# alf_board_v8.net
KiCad netlist of a schematic drawn in EAGLE
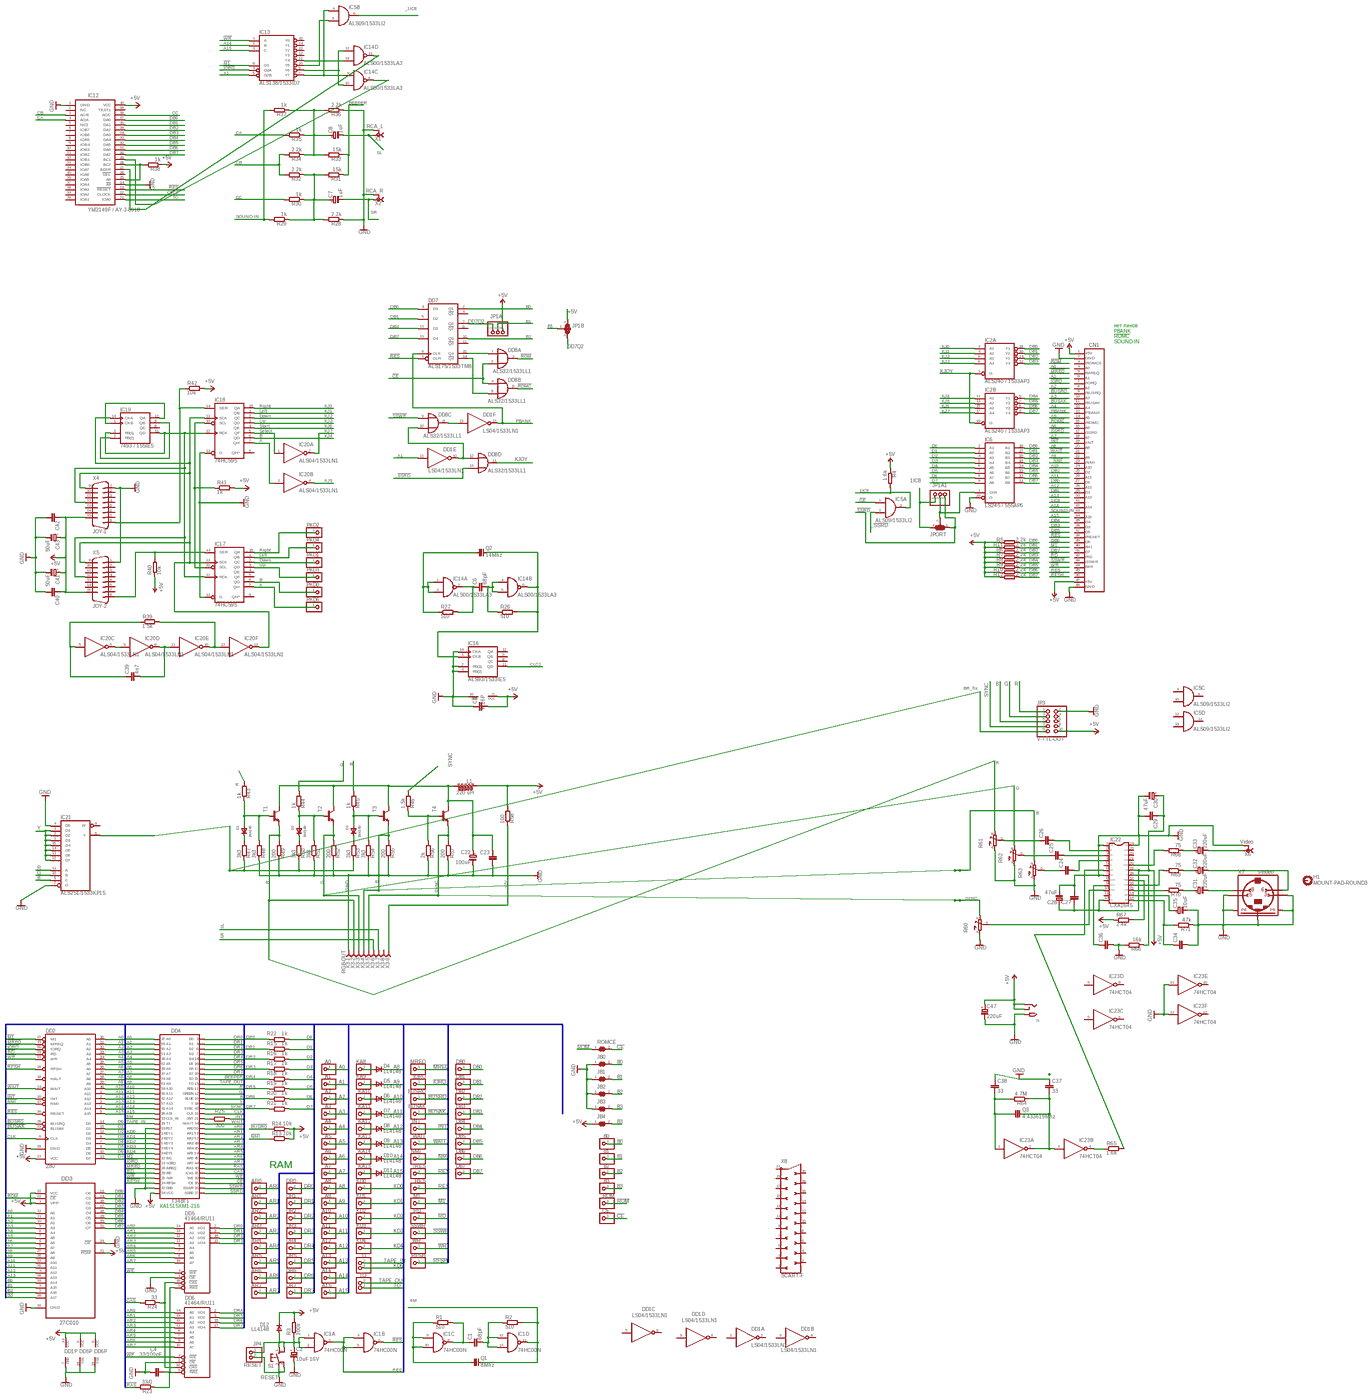
[diagram p0: schematic, sheet 1, overview]
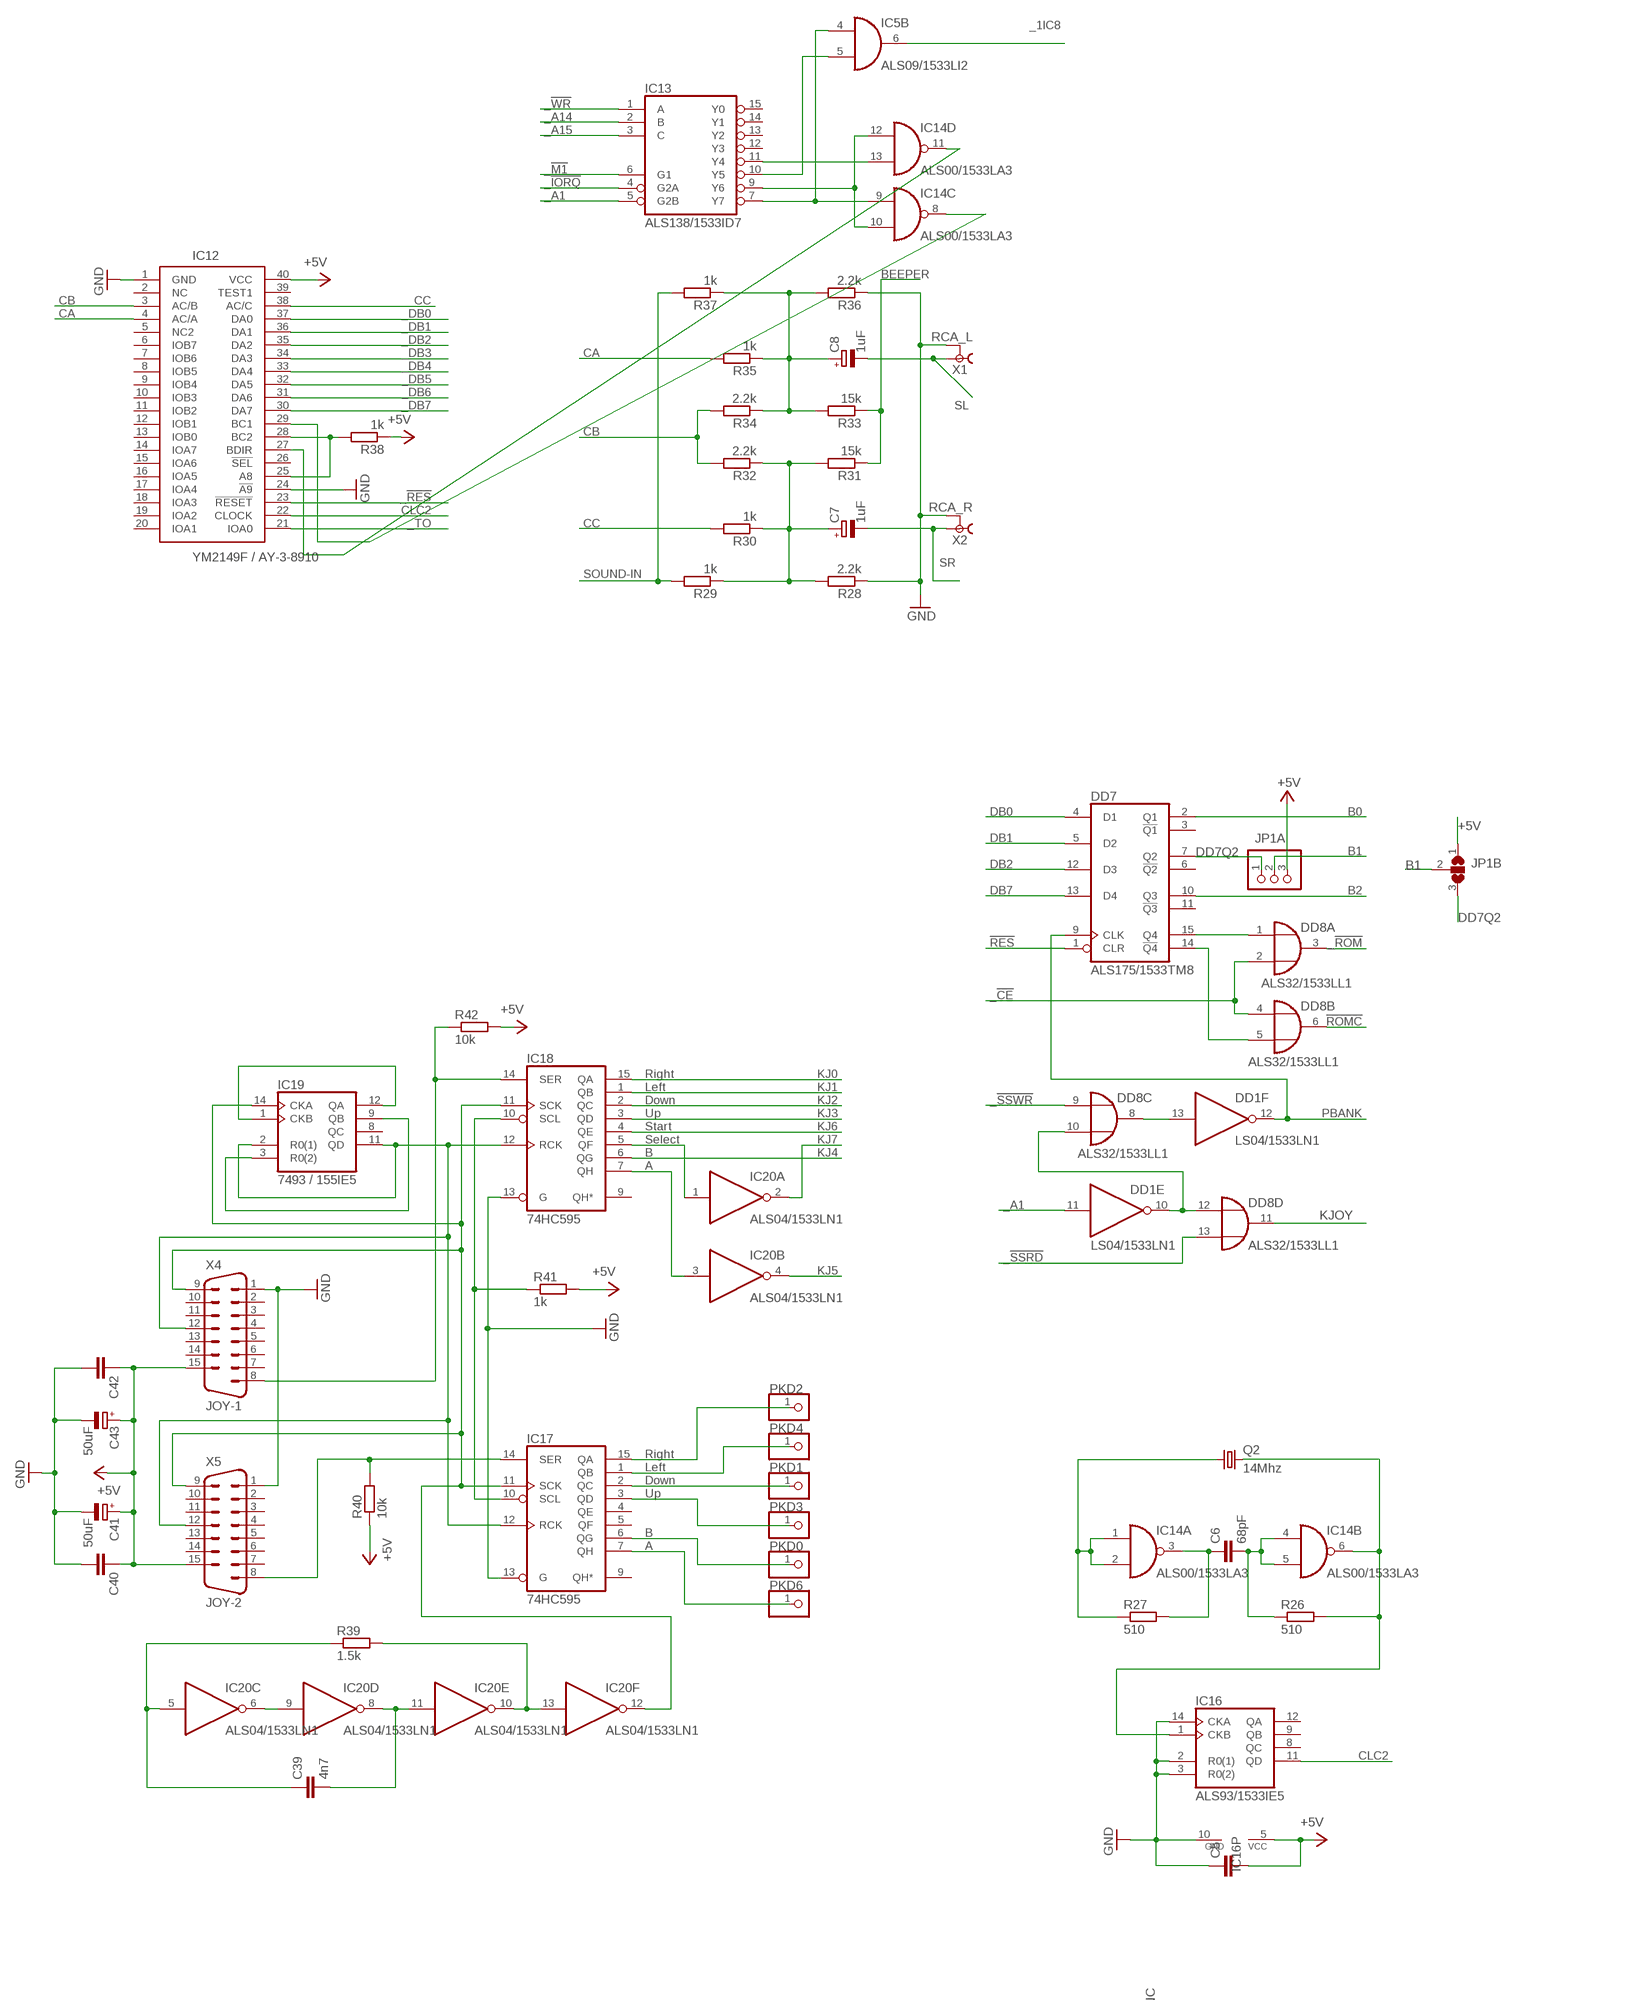
[diagram p1: schematic, sheet 1, part 1 of 4]
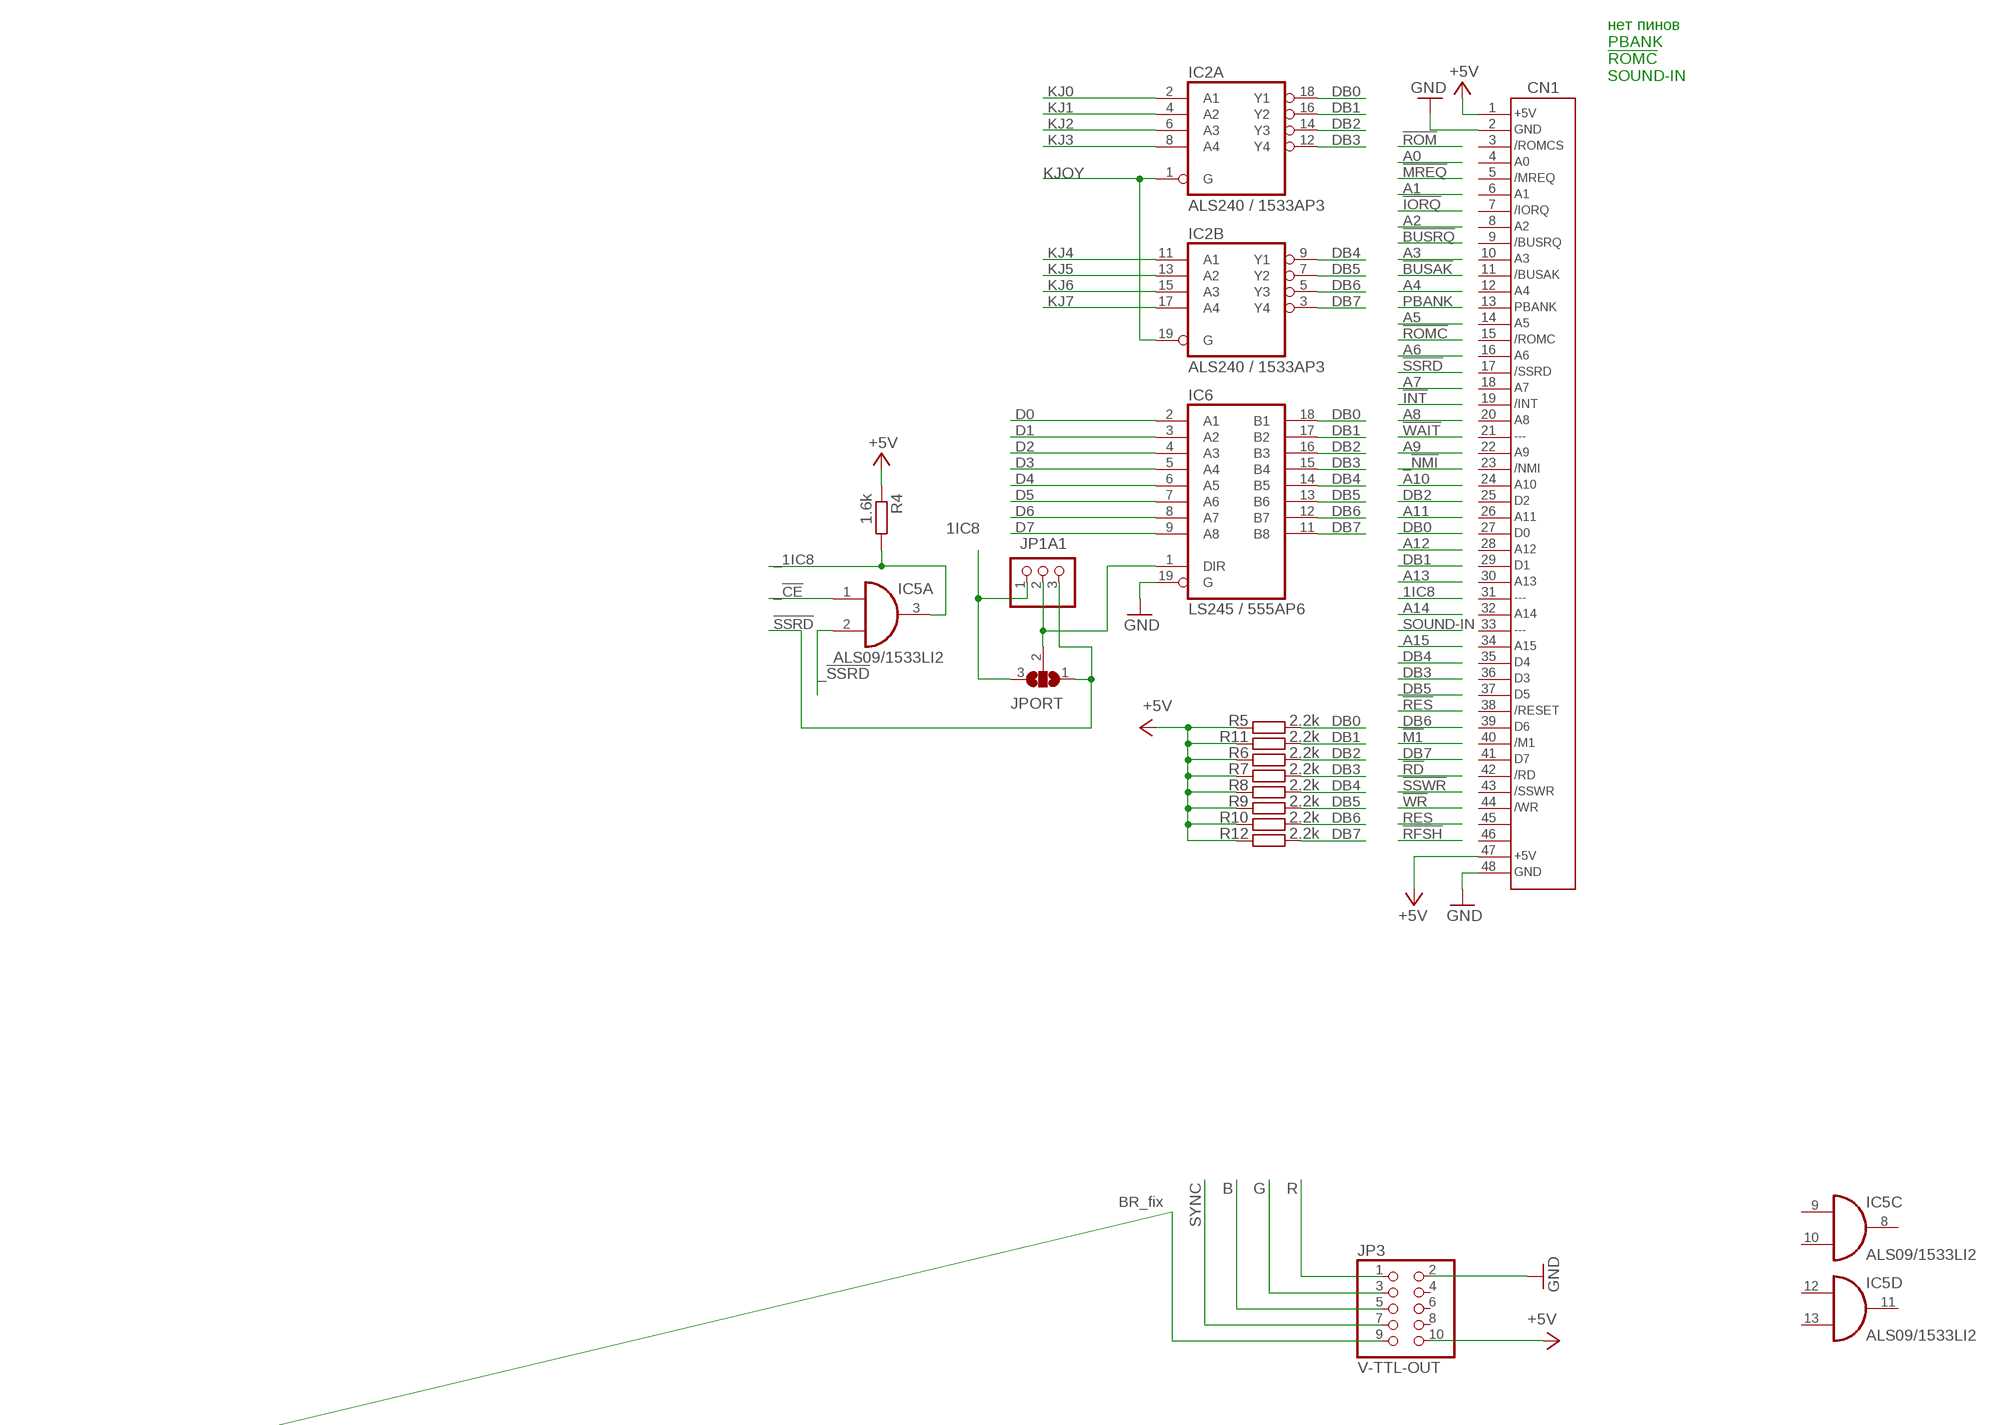
[diagram p2: schematic, sheet 1, part 2 of 4]
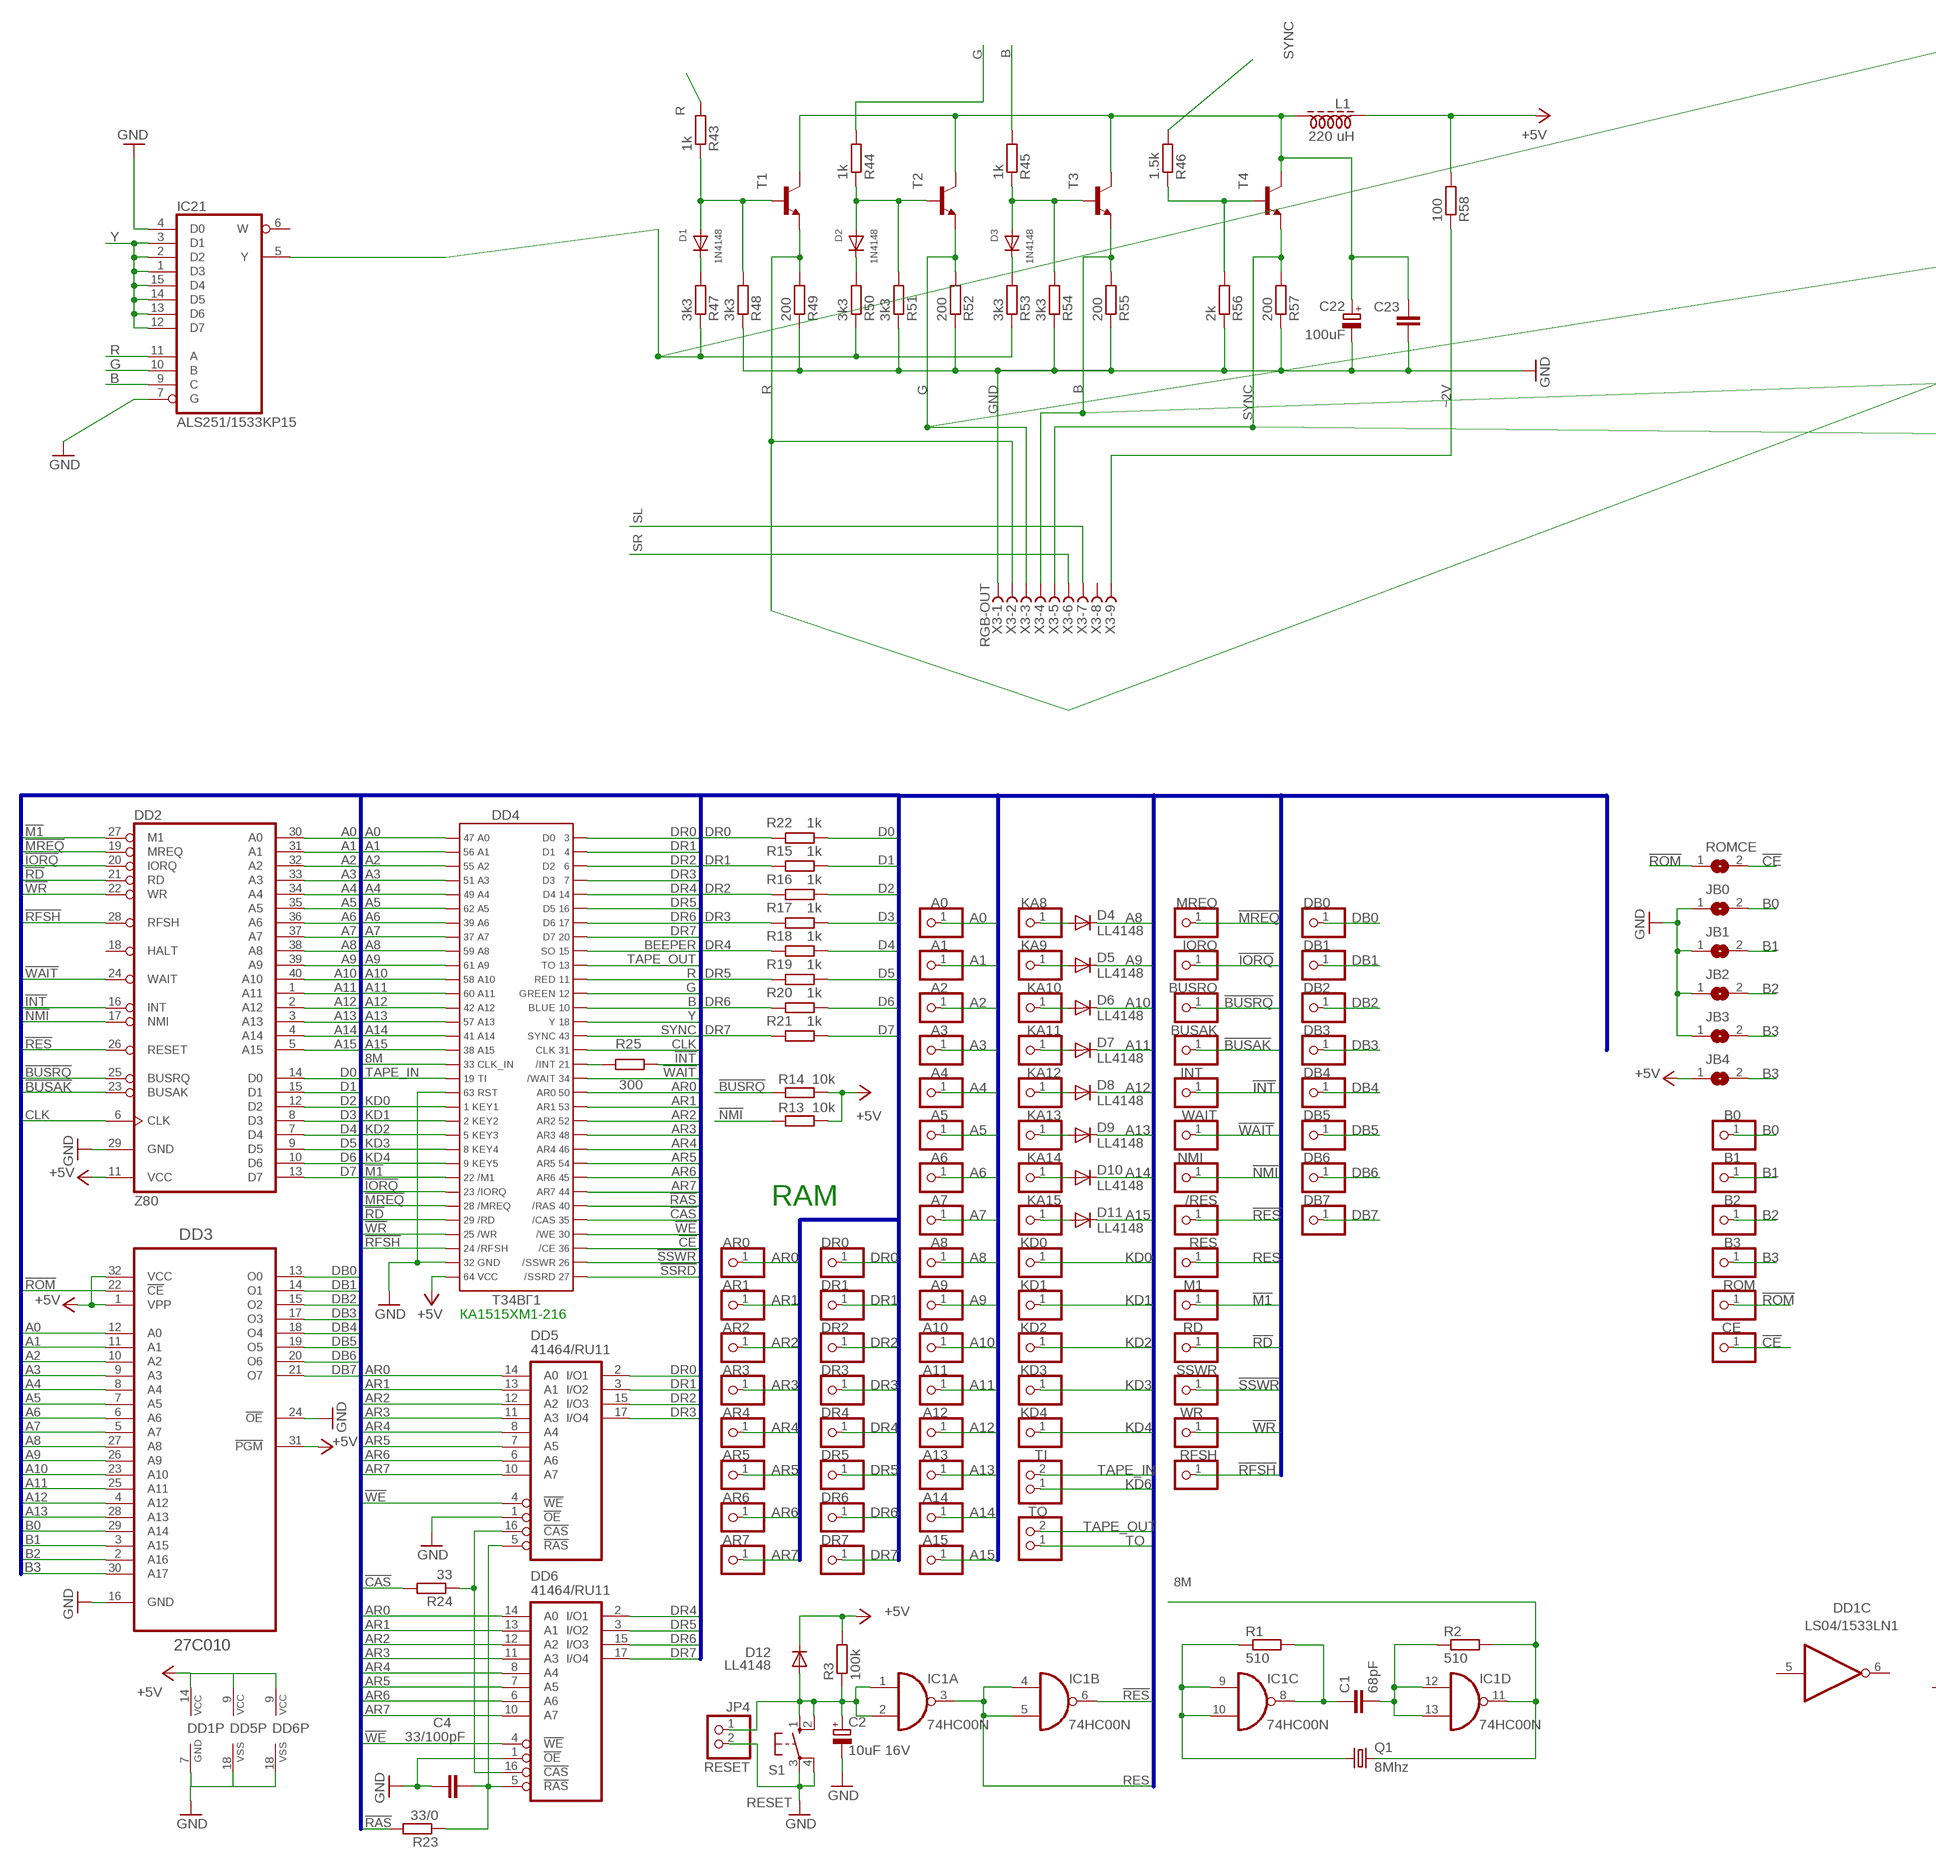
[diagram p3: schematic, sheet 1, part 3 of 4]
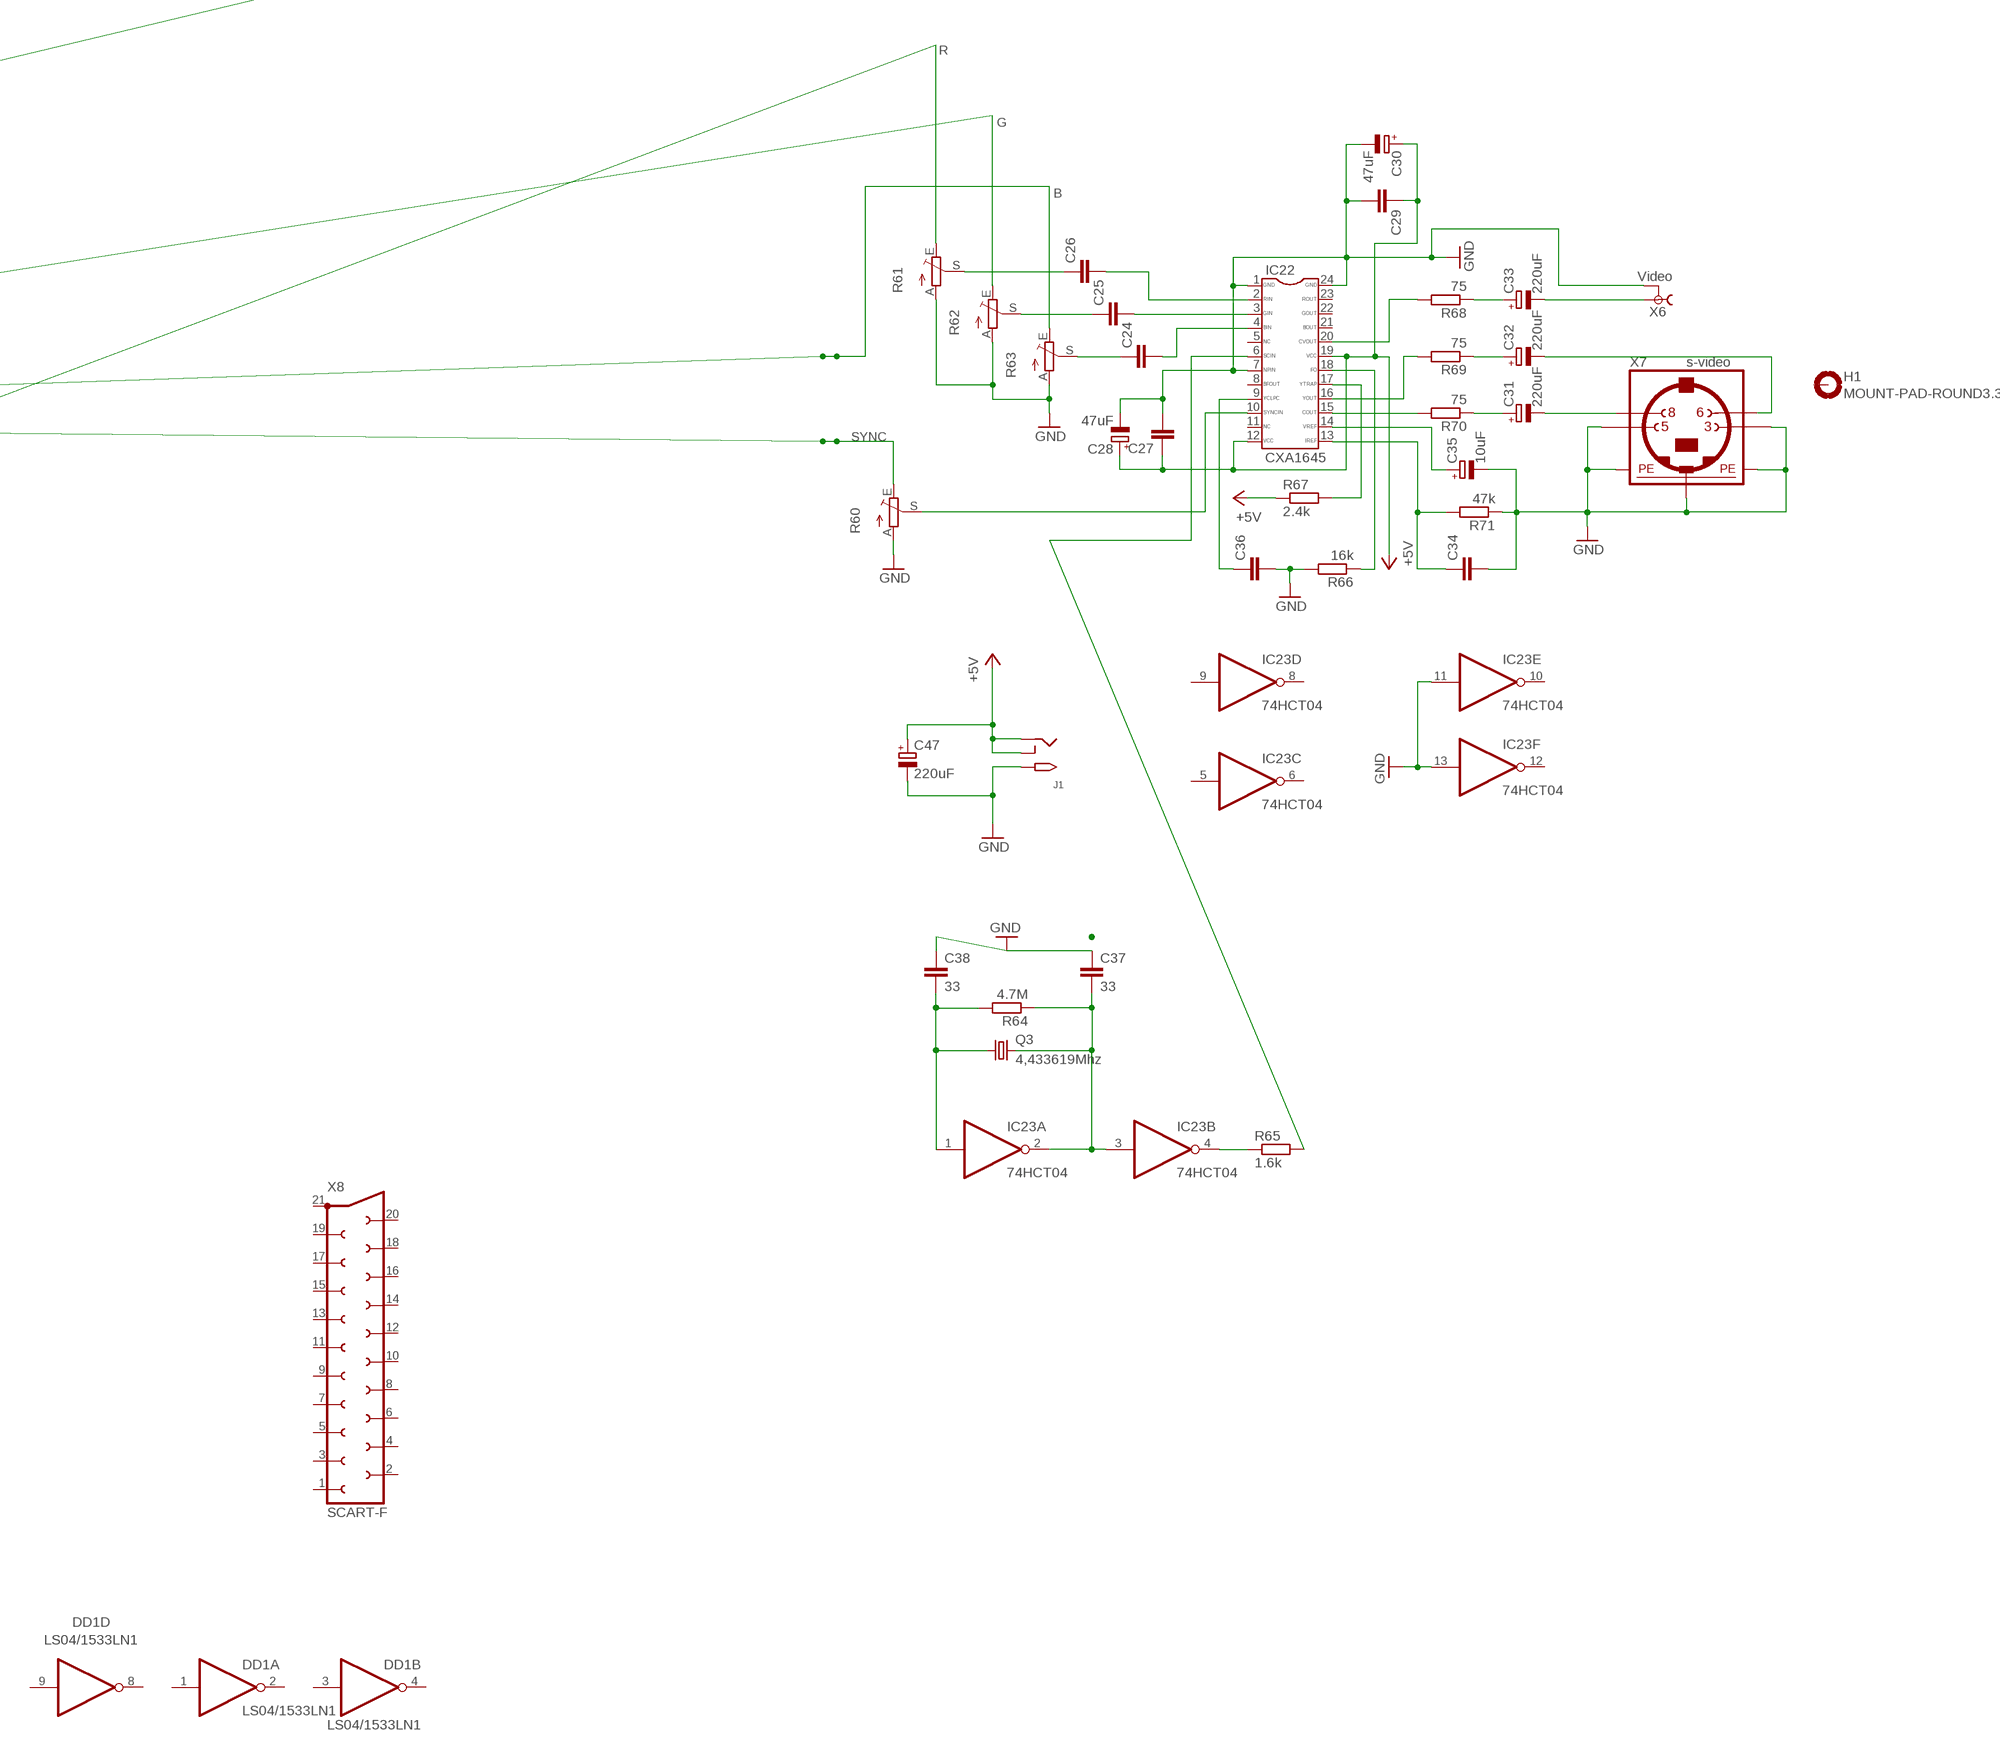
[diagram p4: schematic, sheet 1, part 4 of 4]

(export (version "E")
  (design (tool "Eeschema 10.0.6"))
  (components
    (comp (ref "/RES")
      (value "PINHD-1X1")
      (footprint "eagle-import:1X01")
      (libsource (lib "eagle-import") (part "PINHD-1X1"))
    )
    (comp (ref "A0")
      (value "PINHD-1X1")
      (footprint "eagle-import:1X01")
      (libsource (lib "eagle-import") (part "PINHD-1X1"))
    )
    (comp (ref "A1")
      (value "PINHD-1X1")
      (footprint "eagle-import:1X01")
      (libsource (lib "eagle-import") (part "PINHD-1X1"))
    )
    (comp (ref "A2")
      (value "PINHD-1X1")
      (footprint "eagle-import:1X01")
      (libsource (lib "eagle-import") (part "PINHD-1X1"))
    )
    (comp (ref "A3")
      (value "PINHD-1X1")
      (footprint "eagle-import:1X01")
      (libsource (lib "eagle-import") (part "PINHD-1X1"))
    )
    (comp (ref "A4")
      (value "PINHD-1X1")
      (footprint "eagle-import:1X01")
      (libsource (lib "eagle-import") (part "PINHD-1X1"))
    )
    (comp (ref "A5")
      (value "PINHD-1X1")
      (footprint "eagle-import:1X01")
      (libsource (lib "eagle-import") (part "PINHD-1X1"))
    )
    (comp (ref "A6")
      (value "PINHD-1X1")
      (footprint "eagle-import:1X01")
      (libsource (lib "eagle-import") (part "PINHD-1X1"))
    )
    (comp (ref "A7")
      (value "PINHD-1X1")
      (footprint "eagle-import:1X01")
      (libsource (lib "eagle-import") (part "PINHD-1X1"))
    )
    (comp (ref "A8")
      (value "PINHD-1X1")
      (footprint "eagle-import:1X01")
      (libsource (lib "eagle-import") (part "PINHD-1X1"))
    )
    (comp (ref "A9")
      (value "PINHD-1X1")
      (footprint "eagle-import:1X01")
      (libsource (lib "eagle-import") (part "PINHD-1X1"))
    )
    (comp (ref "A10")
      (value "PINHD-1X1")
      (footprint "eagle-import:1X01")
      (libsource (lib "eagle-import") (part "PINHD-1X1"))
    )
    (comp (ref "A11")
      (value "PINHD-1X1")
      (footprint "eagle-import:1X01")
      (libsource (lib "eagle-import") (part "PINHD-1X1"))
    )
    (comp (ref "A12")
      (value "PINHD-1X1")
      (footprint "eagle-import:1X01")
      (libsource (lib "eagle-import") (part "PINHD-1X1"))
    )
    (comp (ref "A13")
      (value "PINHD-1X1")
      (footprint "eagle-import:1X01")
      (libsource (lib "eagle-import") (part "PINHD-1X1"))
    )
    (comp (ref "A14")
      (value "PINHD-1X1")
      (footprint "eagle-import:1X01")
      (libsource (lib "eagle-import") (part "PINHD-1X1"))
    )
    (comp (ref "A15")
      (value "PINHD-1X1")
      (footprint "eagle-import:1X01")
      (libsource (lib "eagle-import") (part "PINHD-1X1"))
    )
    (comp (ref "AR0")
      (value "PINHD-1X1")
      (footprint "eagle-import:1X01")
      (libsource (lib "eagle-import") (part "PINHD-1X1"))
    )
    (comp (ref "AR1")
      (value "PINHD-1X1")
      (footprint "eagle-import:1X01")
      (libsource (lib "eagle-import") (part "PINHD-1X1"))
    )
    (comp (ref "AR2")
      (value "PINHD-1X1")
      (footprint "eagle-import:1X01")
      (libsource (lib "eagle-import") (part "PINHD-1X1"))
    )
    (comp (ref "AR3")
      (value "PINHD-1X1")
      (footprint "eagle-import:1X01")
      (libsource (lib "eagle-import") (part "PINHD-1X1"))
    )
    (comp (ref "AR4")
      (value "PINHD-1X1")
      (footprint "eagle-import:1X01")
      (libsource (lib "eagle-import") (part "PINHD-1X1"))
    )
    (comp (ref "AR5")
      (value "PINHD-1X1")
      (footprint "eagle-import:1X01")
      (libsource (lib "eagle-import") (part "PINHD-1X1"))
    )
    (comp (ref "AR6")
      (value "PINHD-1X1")
      (footprint "eagle-import:1X01")
      (libsource (lib "eagle-import") (part "PINHD-1X1"))
    )
    (comp (ref "AR7")
      (value "PINHD-1X1")
      (footprint "eagle-import:1X01")
      (libsource (lib "eagle-import") (part "PINHD-1X1"))
    )
    (comp (ref "B0")
      (value "PINHD-1X1")
      (footprint "eagle-import:1X01")
      (libsource (lib "eagle-import") (part "PINHD-1X1"))
    )
    (comp (ref "B1")
      (value "PINHD-1X1")
      (footprint "eagle-import:1X01")
      (libsource (lib "eagle-import") (part "PINHD-1X1"))
    )
    (comp (ref "B2")
      (value "PINHD-1X1")
      (footprint "eagle-import:1X01")
      (libsource (lib "eagle-import") (part "PINHD-1X1"))
    )
    (comp (ref "B3")
      (value "PINHD-1X1")
      (footprint "eagle-import:1X01")
      (libsource (lib "eagle-import") (part "PINHD-1X1"))
    )
    (comp (ref "BUSAK")
      (value "PINHD-1X1")
      (footprint "eagle-import:1X01")
      (libsource (lib "eagle-import") (part "PINHD-1X1"))
    )
    (comp (ref "BUSRQ")
      (value "PINHD-1X1")
      (footprint "eagle-import:1X01")
      (libsource (lib "eagle-import") (part "PINHD-1X1"))
    )
    (comp (ref "C1")
      (value "68pF")
      (footprint "eagle-import:C0805")
      (libsource (lib "eagle-import") (part "C-EUC0805"))
    )
    (comp (ref "C2")
      (value "10uF 16V")
      (footprint "eagle-import:SMC_A")
      (fields (field (name "MF") "MULTICOMP") (field (name "MPN") "MCNP35V106M5X11"))
      (libsource (lib "eagle-import") (part "CPOL-EUSMCA"))
    )
    (comp (ref "C4")
      (value "33/100pF")
      (footprint "eagle-import:C102-043X133")
      (libsource (lib "eagle-import") (part "C-EU102-043X133"))
    )
    (comp (ref "C5")
      (value "C-EUC0805")
      (footprint "eagle-import:C0805")
      (libsource (lib "eagle-import") (part "C-EUC0805"))
    )
    (comp (ref "C6")
      (value "68pF")
      (footprint "eagle-import:C0805")
      (libsource (lib "eagle-import") (part "C-EUC0805"))
    )
    (comp (ref "C7")
      (value "1uF")
      (footprint "eagle-import:SMC_A")
      (libsource (lib "eagle-import") (part "CPOL-EUSMCA"))
    )
    (comp (ref "C8")
      (value "1uF")
      (footprint "eagle-import:SMC_A")
      (libsource (lib "eagle-import") (part "CPOL-EUSMCA"))
    )
    (comp (ref "C22")
      (value "100uF")
      (footprint "eagle-import:SMC_B")
      (libsource (lib "eagle-import") (part "CPOL-EUSMCB"))
    )
    (comp (ref "C23")
      (value "C-EUC0805")
      (footprint "eagle-import:C0805")
      (libsource (lib "eagle-import") (part "C-EUC0805"))
    )
    (comp (ref "C24")
      (value "C-EUC0805")
      (footprint "eagle-import:C0805")
      (libsource (lib "eagle-import") (part "C-EUC0805"))
    )
    (comp (ref "C25")
      (value "C-EUC0805")
      (footprint "eagle-import:C0805")
      (libsource (lib "eagle-import") (part "C-EUC0805"))
    )
    (comp (ref "C26")
      (value "C-EUC0805")
      (footprint "eagle-import:C0805")
      (libsource (lib "eagle-import") (part "C-EUC0805"))
    )
    (comp (ref "C27")
      (value "C-EUC0805")
      (footprint "eagle-import:C0805")
      (libsource (lib "eagle-import") (part "C-EUC0805"))
    )
    (comp (ref "C28")
      (value "47uF")
      (footprint "eagle-import:SMC_B")
      (libsource (lib "eagle-import") (part "CPOL-EUSMCB"))
    )
    (comp (ref "C29")
      (value "C-EUC0805")
      (footprint "eagle-import:C0805")
      (libsource (lib "eagle-import") (part "C-EUC0805"))
    )
    (comp (ref "C30")
      (value "47uF")
      (footprint "eagle-import:SMC_B")
      (libsource (lib "eagle-import") (part "CPOL-EUSMCB"))
    )
    (comp (ref "C31")
      (value "220uF")
      (footprint "eagle-import:SMC_D")
      (libsource (lib "eagle-import") (part "CPOL-EUSMCD"))
    )
    (comp (ref "C32")
      (value "220uF")
      (footprint "eagle-import:SMC_D")
      (libsource (lib "eagle-import") (part "CPOL-EUSMCD"))
    )
    (comp (ref "C33")
      (value "220uF")
      (footprint "eagle-import:SMC_D")
      (libsource (lib "eagle-import") (part "CPOL-EUSMCD"))
    )
    (comp (ref "C34")
      (value "C-EUC0805")
      (footprint "eagle-import:C0805")
      (libsource (lib "eagle-import") (part "C-EUC0805"))
    )
    (comp (ref "C35")
      (value "10uF")
      (footprint "eagle-import:SMC_A")
      (libsource (lib "eagle-import") (part "CPOL-EUSMCA"))
    )
    (comp (ref "C36")
      (value "C-EUC0805")
      (footprint "eagle-import:C0805")
      (libsource (lib "eagle-import") (part "C-EUC0805"))
    )
    (comp (ref "C37")
      (value "33")
      (footprint "eagle-import:C0805")
      (libsource (lib "eagle-import") (part "C-EUC0805"))
    )
    (comp (ref "C38")
      (value "33")
      (footprint "eagle-import:C0805")
      (libsource (lib "eagle-import") (part "C-EUC0805"))
    )
    (comp (ref "C39")
      (value "4n7")
      (footprint "eagle-import:C0805")
      (libsource (lib "eagle-import") (part "C-EUC0805"))
    )
    (comp (ref "C40")
      (value "C-EUC0805")
      (footprint "eagle-import:C0805")
      (libsource (lib "eagle-import") (part "C-EUC0805"))
    )
    (comp (ref "C41")
      (value "50uF")
      (footprint "eagle-import:SMC_B")
      (libsource (lib "eagle-import") (part "CPOL-EUSMCB"))
    )
    (comp (ref "C42")
      (value "C-EUC0805")
      (footprint "eagle-import:C0805")
      (libsource (lib "eagle-import") (part "C-EUC0805"))
    )
    (comp (ref "C43")
      (value "50uF")
      (footprint "eagle-import:SMC_B")
      (libsource (lib "eagle-import") (part "CPOL-EUSMCB"))
    )
    (comp (ref "C47")
      (value "220uF")
      (footprint "eagle-import:SMC_D")
      (libsource (lib "eagle-import") (part "CPOL-EUSMCD"))
    )
    (comp (ref "CE")
      (value "PINHD-1X1")
      (footprint "eagle-import:1X01")
      (libsource (lib "eagle-import") (part "PINHD-1X1"))
    )
    (comp (ref "CN1")
      (value "СНП15-48")
      (footprint "eagle-import:СНП15-48")
      (libsource (lib "eagle-import") (part "СНП15-48"))
    )
    (comp (ref "D1")
      (value "1N4148")
      (footprint "eagle-import:DO-1N4148")
      (libsource (lib "eagle-import") (part "DIODEDO-1N4148"))
    )
    (comp (ref "D2")
      (value "1N4148")
      (footprint "eagle-import:DO-1N4148")
      (libsource (lib "eagle-import") (part "DIODEDO-1N4148"))
    )
    (comp (ref "D3")
      (value "1N4148")
      (footprint "eagle-import:DO-1N4148")
      (libsource (lib "eagle-import") (part "DIODEDO-1N4148"))
    )
    (comp (ref "D4")
      (value "LL4148")
      (footprint "eagle-import:SOD80C")
      (libsource (lib "eagle-import") (part "DIODE-SOD80C"))
    )
    (comp (ref "D5")
      (value "LL4148")
      (footprint "eagle-import:SOD80C")
      (libsource (lib "eagle-import") (part "DIODE-SOD80C"))
    )
    (comp (ref "D6")
      (value "LL4148")
      (footprint "eagle-import:SOD80C")
      (libsource (lib "eagle-import") (part "DIODE-SOD80C"))
    )
    (comp (ref "D7")
      (value "LL4148")
      (footprint "eagle-import:SOD80C")
      (libsource (lib "eagle-import") (part "DIODE-SOD80C"))
    )
    (comp (ref "D8")
      (value "LL4148")
      (footprint "eagle-import:SOD80C")
      (libsource (lib "eagle-import") (part "DIODE-SOD80C"))
    )
    (comp (ref "D9")
      (value "LL4148")
      (footprint "eagle-import:SOD80C")
      (libsource (lib "eagle-import") (part "DIODE-SOD80C"))
    )
    (comp (ref "D10")
      (value "LL4148")
      (footprint "eagle-import:SOD80C")
      (libsource (lib "eagle-import") (part "DIODE-SOD80C"))
    )
    (comp (ref "D11")
      (value "LL4148")
      (footprint "eagle-import:SOD80C")
      (libsource (lib "eagle-import") (part "DIODE-SOD80C"))
    )
    (comp (ref "D12")
      (value "LL4148")
      (footprint "eagle-import:SOD80C")
      (libsource (lib "eagle-import") (part "DIODE-SOD80C"))
    )
    (comp (ref "DB0")
      (value "PINHD-1X1")
      (footprint "eagle-import:1X01")
      (libsource (lib "eagle-import") (part "PINHD-1X1"))
    )
    (comp (ref "DB1")
      (value "PINHD-1X1")
      (footprint "eagle-import:1X01")
      (libsource (lib "eagle-import") (part "PINHD-1X1"))
    )
    (comp (ref "DB2")
      (value "PINHD-1X1")
      (footprint "eagle-import:1X01")
      (libsource (lib "eagle-import") (part "PINHD-1X1"))
    )
    (comp (ref "DB3")
      (value "PINHD-1X1")
      (footprint "eagle-import:1X01")
      (libsource (lib "eagle-import") (part "PINHD-1X1"))
    )
    (comp (ref "DB4")
      (value "PINHD-1X1")
      (footprint "eagle-import:1X01")
      (libsource (lib "eagle-import") (part "PINHD-1X1"))
    )
    (comp (ref "DB5")
      (value "PINHD-1X1")
      (footprint "eagle-import:1X01")
      (libsource (lib "eagle-import") (part "PINHD-1X1"))
    )
    (comp (ref "DB6")
      (value "PINHD-1X1")
      (footprint "eagle-import:1X01")
      (libsource (lib "eagle-import") (part "PINHD-1X1"))
    )
    (comp (ref "DB7")
      (value "PINHD-1X1")
      (footprint "eagle-import:1X01")
      (libsource (lib "eagle-import") (part "PINHD-1X1"))
    )
    (comp (ref "DD1")
      (value "LS04/1533LN1")
      (footprint "eagle-import:DIL14")
      (fields (field (name "OC_FARNELL") "unknown"))
      (libsource (lib "eagle-import") (part "7404NLS"))
    )
    (comp (ref "DD2")
      (value "Z80")
      (footprint "eagle-import:DIL40")
      (libsource (lib "eagle-import") (part "Z80CPU"))
    )
    (comp (ref "DD3")
      (value "27C010")
      (footprint "eagle-import:DIP254P1524X482-32P")
      (fields
        (field (name "MPN") "AT27C020-90PU")
        (field (name "MF") "ATMEL")
        (field (name "MPN_1") "AT27C020-90PU")
        (field (name "OC_FARNELL") "1095777")
        (field (name "OC_NEWARK") "68T4266")
        (field (name "PACKAGE") "PDIP-32")
        (field (name "SUPPLIER") "ATMEL")
      )
      (libsource (lib "eagle-import") (part "AT27C020-90PU"))
    )
    (comp (ref "DD4")
      (value "Т34ВГ1")
      (footprint "eagle-import:TQFP64-MF")
      (libsource (lib "eagle-import") (part "Т34ВГ1MF"))
    )
    (comp (ref "DD5")
      (value "41464/RU11")
      (footprint "eagle-import:DIL18")
      (libsource (lib "eagle-import") (part "41464"))
    )
    (comp (ref "DD6")
      (value "41464/RU11")
      (footprint "eagle-import:DIL18")
      (libsource (lib "eagle-import") (part "41464"))
    )
    (comp (ref "DD7")
      (value "ALS175/1533TM8")
      (footprint "eagle-import:DIL16")
      (libsource (lib "eagle-import") (part "74175NLS"))
    )
    (comp (ref "DD8")
      (value "ALS32/1533LL1")
      (footprint "eagle-import:DIL14")
      (fields (field (name "OC_FARNELL") "unknown"))
      (libsource (lib "eagle-import") (part "7432NLS"))
    )
    (comp (ref "DR0")
      (value "PINHD-1X1")
      (footprint "eagle-import:1X01")
      (libsource (lib "eagle-import") (part "PINHD-1X1"))
    )
    (comp (ref "DR1")
      (value "PINHD-1X1")
      (footprint "eagle-import:1X01")
      (libsource (lib "eagle-import") (part "PINHD-1X1"))
    )
    (comp (ref "DR2")
      (value "PINHD-1X1")
      (footprint "eagle-import:1X01")
      (libsource (lib "eagle-import") (part "PINHD-1X1"))
    )
    (comp (ref "DR3")
      (value "PINHD-1X1")
      (footprint "eagle-import:1X01")
      (libsource (lib "eagle-import") (part "PINHD-1X1"))
    )
    (comp (ref "DR4")
      (value "PINHD-1X1")
      (footprint "eagle-import:1X01")
      (libsource (lib "eagle-import") (part "PINHD-1X1"))
    )
    (comp (ref "DR5")
      (value "PINHD-1X1")
      (footprint "eagle-import:1X01")
      (libsource (lib "eagle-import") (part "PINHD-1X1"))
    )
    (comp (ref "DR6")
      (value "PINHD-1X1")
      (footprint "eagle-import:1X01")
      (libsource (lib "eagle-import") (part "PINHD-1X1"))
    )
    (comp (ref "DR7")
      (value "PINHD-1X1")
      (footprint "eagle-import:1X01")
      (libsource (lib "eagle-import") (part "PINHD-1X1"))
    )
    (comp (ref "H1")
      (value "MOUNT-PAD-ROUND3.3")
      (footprint "eagle-import:3,3-PAD")
      (libsource (lib "eagle-import") (part "MOUNT-PAD-ROUND3.3"))
    )
    (comp (ref "IC1")
      (value "74HC00N")
      (footprint "eagle-import:DIL14")
      (libsource (lib "eagle-import") (part "7400NHC"))
    )
    (comp (ref "IC2")
      (value "ALS240 / 1533AP3")
      (footprint "eagle-import:DIL20")
      (fields (field (name "OC_FARNELL") "unknown"))
      (libsource (lib "eagle-import") (part "74240NLS"))
    )
    (comp (ref "IC5")
      (value "ALS09/1533LI2")
      (footprint "eagle-import:DIL14")
      (fields (field (name "OC_FARNELL") "unknown"))
      (libsource (lib "eagle-import") (part "7409NLS"))
    )
    (comp (ref "IC6")
      (value "LS245 / 555AP6")
      (footprint "eagle-import:SO20W")
      (libsource (lib "eagle-import") (part "74245DWLS"))
    )
    (comp (ref "IC12")
      (value "YM2149F / AY-3-8910")
      (footprint "eagle-import:DIL40")
      (libsource (lib "eagle-import") (part "YM2149F"))
    )
    (comp (ref "IC13")
      (value "ALS138/1533ID7")
      (footprint "eagle-import:DIL16")
      (libsource (lib "eagle-import") (part "74138NLS"))
    )
    (comp (ref "IC14")
      (value "ALS00/1533LA3")
      (footprint "eagle-import:DIL14")
      (fields (field (name "OC_FARNELL") "unknown"))
      (libsource (lib "eagle-import") (part "7400NLS"))
    )
    (comp (ref "IC16")
      (value "ALS93/1533IE5")
      (footprint "eagle-import:DIL14")
      (fields (field (name "OC_FARNELL") "unknown"))
      (libsource (lib "eagle-import") (part "7493NLS"))
    )
    (comp (ref "IC17")
      (value "74HC595")
      (footprint "eagle-import:DIL16")
      (libsource (lib "eagle-import") (part "74595NHC"))
    )
    (comp (ref "IC18")
      (value "74HC595")
      (footprint "eagle-import:DIL16")
      (libsource (lib "eagle-import") (part "74595NHC"))
    )
    (comp (ref "IC19")
      (value "7493 / 155IE5")
      (footprint "eagle-import:DIL14")
      (libsource (lib "eagle-import") (part "7493NLS"))
    )
    (comp (ref "IC20")
      (value "ALS04/1533LN1")
      (footprint "eagle-import:DIL14")
      (fields (field (name "OC_FARNELL") "unknown"))
      (libsource (lib "eagle-import") (part "7404NLS"))
    )
    (comp (ref "IC21")
      (value "ALS251/1533KP15")
      (footprint "eagle-import:DIL16")
      (libsource (lib "eagle-import") (part "74251NLS"))
    )
    (comp (ref "IC22")
      (value "CXA1645")
      (footprint "eagle-import:SOP24")
      (libsource (lib "eagle-import") (part "CXA1645"))
    )
    (comp (ref "IC23")
      (value "74HCT04")
      (footprint "eagle-import:DIL14")
      (libsource (lib "eagle-import") (part "7404NHCT"))
    )
    (comp (ref "INT")
      (value "PINHD-1X1")
      (footprint "eagle-import:1X01")
      (libsource (lib "eagle-import") (part "PINHD-1X1"))
    )
    (comp (ref "IORQ")
      (value "PINHD-1X1")
      (footprint "eagle-import:1X01")
      (libsource (lib "eagle-import") (part "PINHD-1X1"))
    )
    (comp (ref "J1")
      (value "2.1MMJACKTHM")
      (footprint "eagle-import:PJ-102A")
      (libsource (lib "eagle-import") (part "2.1MMJACKTHM"))
    )
    (comp (ref "JB0") (value "SJ") (footprint "eagle-import:SJ") (libsource (lib "eagle-import") (part "SJ")))
    (comp (ref "JB1") (value "SJ") (footprint "eagle-import:SJ") (libsource (lib "eagle-import") (part "SJ")))
    (comp (ref "JB2") (value "SJ") (footprint "eagle-import:SJ") (libsource (lib "eagle-import") (part "SJ")))
    (comp (ref "JB3") (value "SJ") (footprint "eagle-import:SJ") (libsource (lib "eagle-import") (part "SJ")))
    (comp (ref "JB4") (value "SJ") (footprint "eagle-import:SJ") (libsource (lib "eagle-import") (part "SJ")))
    (comp (ref "JP1A")
      (value "PINHD-1X3")
      (footprint "eagle-import:1X03")
      (libsource (lib "eagle-import") (part "PINHD-1X3"))
    )
    (comp (ref "JP1A1")
      (value "PINHD-1X3")
      (footprint "eagle-import:1X03")
      (libsource (lib "eagle-import") (part "PINHD-1X3"))
    )
    (comp (ref "JP1B")
      (value "SJ2W")
      (footprint "eagle-import:SJ_2")
      (libsource (lib "eagle-import") (part "SJ2W"))
    )
    (comp (ref "JP3")
      (value "V-TTL-OUT")
      (footprint "eagle-import:2X05")
      (libsource (lib "eagle-import") (part "PINHD-2X5"))
    )
    (comp (ref "JP4")
      (value "RESET")
      (footprint "eagle-import:1X02")
      (libsource (lib "eagle-import") (part "PINHD-1X2"))
    )
    (comp (ref "JPORT")
      (value "SJ2W")
      (footprint "eagle-import:SJ_2")
      (libsource (lib "eagle-import") (part "SJ2W"))
    )
    (comp (ref "KA8")
      (value "PINHD-1X1")
      (footprint "eagle-import:1X01")
      (libsource (lib "eagle-import") (part "PINHD-1X1"))
    )
    (comp (ref "KA9")
      (value "PINHD-1X1")
      (footprint "eagle-import:1X01")
      (libsource (lib "eagle-import") (part "PINHD-1X1"))
    )
    (comp (ref "KA10")
      (value "PINHD-1X1")
      (footprint "eagle-import:1X01")
      (libsource (lib "eagle-import") (part "PINHD-1X1"))
    )
    (comp (ref "KA11")
      (value "PINHD-1X1")
      (footprint "eagle-import:1X01")
      (libsource (lib "eagle-import") (part "PINHD-1X1"))
    )
    (comp (ref "KA12")
      (value "PINHD-1X1")
      (footprint "eagle-import:1X01")
      (libsource (lib "eagle-import") (part "PINHD-1X1"))
    )
    (comp (ref "KA13")
      (value "PINHD-1X1")
      (footprint "eagle-import:1X01")
      (libsource (lib "eagle-import") (part "PINHD-1X1"))
    )
    (comp (ref "KA14")
      (value "PINHD-1X1")
      (footprint "eagle-import:1X01")
      (libsource (lib "eagle-import") (part "PINHD-1X1"))
    )
    (comp (ref "KA15")
      (value "PINHD-1X1")
      (footprint "eagle-import:1X01")
      (libsource (lib "eagle-import") (part "PINHD-1X1"))
    )
    (comp (ref "KD0")
      (value "PINHD-1X1")
      (footprint "eagle-import:1X01")
      (libsource (lib "eagle-import") (part "PINHD-1X1"))
    )
    (comp (ref "KD1")
      (value "PINHD-1X1")
      (footprint "eagle-import:1X01")
      (libsource (lib "eagle-import") (part "PINHD-1X1"))
    )
    (comp (ref "KD2")
      (value "PINHD-1X1")
      (footprint "eagle-import:1X01")
      (libsource (lib "eagle-import") (part "PINHD-1X1"))
    )
    (comp (ref "KD3")
      (value "PINHD-1X1")
      (footprint "eagle-import:1X01")
      (libsource (lib "eagle-import") (part "PINHD-1X1"))
    )
    (comp (ref "KD4")
      (value "PINHD-1X1")
      (footprint "eagle-import:1X01")
      (libsource (lib "eagle-import") (part "PINHD-1X1"))
    )
    (comp (ref "L1")
      (value "220 uH")
      (footprint "eagle-import:Z27_24")
      (libsource (lib "eagle-import") (part "Z?CW27/24"))
    )
    (comp (ref "M1")
      (value "PINHD-1X1")
      (footprint "eagle-import:1X01")
      (libsource (lib "eagle-import") (part "PINHD-1X1"))
    )
    (comp (ref "MREQ")
      (value "PINHD-1X1")
      (footprint "eagle-import:1X01")
      (libsource (lib "eagle-import") (part "PINHD-1X1"))
    )
    (comp (ref "NMI")
      (value "PINHD-1X1")
      (footprint "eagle-import:1X01")
      (libsource (lib "eagle-import") (part "PINHD-1X1"))
    )
    (comp (ref "PKD0")
      (value "PINHD-1X1")
      (footprint "eagle-import:1X01")
      (libsource (lib "eagle-import") (part "PINHD-1X1"))
    )
    (comp (ref "PKD1")
      (value "PINHD-1X1")
      (footprint "eagle-import:1X01")
      (libsource (lib "eagle-import") (part "PINHD-1X1"))
    )
    (comp (ref "PKD2")
      (value "PINHD-1X1")
      (footprint "eagle-import:1X01")
      (libsource (lib "eagle-import") (part "PINHD-1X1"))
    )
    (comp (ref "PKD3")
      (value "PINHD-1X1")
      (footprint "eagle-import:1X01")
      (libsource (lib "eagle-import") (part "PINHD-1X1"))
    )
    (comp (ref "PKD4")
      (value "PINHD-1X1")
      (footprint "eagle-import:1X01")
      (libsource (lib "eagle-import") (part "PINHD-1X1"))
    )
    (comp (ref "PKD6")
      (value "PINHD-1X1")
      (footprint "eagle-import:1X01")
      (libsource (lib "eagle-import") (part "PINHD-1X1"))
    )
    (comp (ref "Q1")
      (value "8Mhz")
      (footprint "eagle-import:HC49_S")
      (fields (field (name "MF") "MULTICOMP") (field (name "MPN") "HC49SM-3.6864-30-50-60-16-ATF"))
      (libsource (lib "eagle-import") (part "CRYSTALHC49S"))
    )
    (comp (ref "Q2")
      (value "14Mhz")
      (footprint "eagle-import:HC49_S")
      (fields (field (name "MF") "MULTICOMP") (field (name "MPN") "HC49SM-3.6864-30-50-60-16-ATF"))
      (libsource (lib "eagle-import") (part "CRYSTALHC49S"))
    )
    (comp (ref "Q3")
      (value "4,433619Mhz")
      (footprint "eagle-import:HC49_S")
      (fields (field (name "MF") "MULTICOMP") (field (name "MPN") "HC49SM-3.6864-30-50-60-16-ATF"))
      (libsource (lib "eagle-import") (part "CRYSTALHC49S"))
    )
    (comp (ref "R1")
      (value "510")
      (footprint "eagle-import:R0805")
      (libsource (lib "eagle-import") (part "R-EU_R0805"))
    )
    (comp (ref "R2")
      (value "510")
      (footprint "eagle-import:R0805")
      (libsource (lib "eagle-import") (part "R-EU_R0805"))
    )
    (comp (ref "R3")
      (value "100k")
      (footprint "eagle-import:R0805")
      (libsource (lib "eagle-import") (part "R-EU_R0805"))
    )
    (comp (ref "R4")
      (value "1.6k")
      (footprint "eagle-import:R0805")
      (libsource (lib "eagle-import") (part "R-EU_R0805"))
    )
    (comp (ref "R5")
      (value "2.2k")
      (footprint "eagle-import:R0805")
      (libsource (lib "eagle-import") (part "R-EU_R0805"))
    )
    (comp (ref "R6")
      (value "2.2k")
      (footprint "eagle-import:R0805")
      (libsource (lib "eagle-import") (part "R-EU_R0805"))
    )
    (comp (ref "R7")
      (value "2.2k")
      (footprint "eagle-import:R0805")
      (libsource (lib "eagle-import") (part "R-EU_R0805"))
    )
    (comp (ref "R8")
      (value "2.2k")
      (footprint "eagle-import:R0805")
      (libsource (lib "eagle-import") (part "R-EU_R0805"))
    )
    (comp (ref "R9")
      (value "2.2k")
      (footprint "eagle-import:R0805")
      (libsource (lib "eagle-import") (part "R-EU_R0805"))
    )
    (comp (ref "R10")
      (value "2.2k")
      (footprint "eagle-import:R0805")
      (libsource (lib "eagle-import") (part "R-EU_R0805"))
    )
    (comp (ref "R11")
      (value "2.2k")
      (footprint "eagle-import:R0805")
      (libsource (lib "eagle-import") (part "R-EU_R0805"))
    )
    (comp (ref "R12")
      (value "2.2k")
      (footprint "eagle-import:R0805")
      (libsource (lib "eagle-import") (part "R-EU_R0805"))
    )
    (comp (ref "R13")
      (value "10k")
      (footprint "eagle-import:R0805")
      (libsource (lib "eagle-import") (part "R-EU_R0805"))
    )
    (comp (ref "R14")
      (value "10k")
      (footprint "eagle-import:R0805")
      (libsource (lib "eagle-import") (part "R-EU_R0805"))
    )
    (comp (ref "R15")
      (value "1k")
      (footprint "eagle-import:R0805")
      (libsource (lib "eagle-import") (part "R-EU_R0805"))
    )
    (comp (ref "R16")
      (value "1k")
      (footprint "eagle-import:R0805")
      (libsource (lib "eagle-import") (part "R-EU_R0805"))
    )
    (comp (ref "R17")
      (value "1k")
      (footprint "eagle-import:R0805")
      (libsource (lib "eagle-import") (part "R-EU_R0805"))
    )
    (comp (ref "R18")
      (value "1k")
      (footprint "eagle-import:R0805")
      (libsource (lib "eagle-import") (part "R-EU_R0805"))
    )
    (comp (ref "R19")
      (value "1k")
      (footprint "eagle-import:R0805")
      (libsource (lib "eagle-import") (part "R-EU_R0805"))
    )
    (comp (ref "R20")
      (value "1k")
      (footprint "eagle-import:R0805")
      (libsource (lib "eagle-import") (part "R-EU_R0805"))
    )
    (comp (ref "R21")
      (value "1k")
      (footprint "eagle-import:R0805")
      (libsource (lib "eagle-import") (part "R-EU_R0805"))
    )
    (comp (ref "R22")
      (value "1k")
      (footprint "eagle-import:R0805")
      (libsource (lib "eagle-import") (part "R-EU_R0805"))
    )
    (comp (ref "R23")
      (value "33/0")
      (footprint "eagle-import:0207_12")
      (libsource (lib "eagle-import") (part "R-EU_0207/12"))
    )
    (comp (ref "R24")
      (value "33")
      (footprint "eagle-import:0207_10")
      (libsource (lib "eagle-import") (part "R-EU_0207/10"))
    )
    (comp (ref "R25")
      (value "300")
      (footprint "eagle-import:R0805")
      (libsource (lib "eagle-import") (part "R-EU_R0805"))
    )
    (comp (ref "R26")
      (value "510")
      (footprint "eagle-import:R0805")
      (libsource (lib "eagle-import") (part "R-EU_R0805"))
    )
    (comp (ref "R27")
      (value "510")
      (footprint "eagle-import:R0805")
      (libsource (lib "eagle-import") (part "R-EU_R0805"))
    )
    (comp (ref "R28")
      (value "2.2k")
      (footprint "eagle-import:R0805")
      (libsource (lib "eagle-import") (part "R-EU_R0805"))
    )
    (comp (ref "R29")
      (value "1k")
      (footprint "eagle-import:R0805")
      (libsource (lib "eagle-import") (part "R-EU_R0805"))
    )
    (comp (ref "R30")
      (value "1k")
      (footprint "eagle-import:R0805")
      (libsource (lib "eagle-import") (part "R-EU_R0805"))
    )
    (comp (ref "R31")
      (value "15k")
      (footprint "eagle-import:R0805")
      (libsource (lib "eagle-import") (part "R-EU_R0805"))
    )
    (comp (ref "R32")
      (value "2.2k")
      (footprint "eagle-import:R0805")
      (libsource (lib "eagle-import") (part "R-EU_R0805"))
    )
    (comp (ref "R33")
      (value "15k")
      (footprint "eagle-import:R0805")
      (libsource (lib "eagle-import") (part "R-EU_R0805"))
    )
    (comp (ref "R34")
      (value "2.2k")
      (footprint "eagle-import:R0805")
      (libsource (lib "eagle-import") (part "R-EU_R0805"))
    )
    (comp (ref "R35")
      (value "1k")
      (footprint "eagle-import:R0805")
      (libsource (lib "eagle-import") (part "R-EU_R0805"))
    )
    (comp (ref "R36")
      (value "2.2k")
      (footprint "eagle-import:R0805")
      (libsource (lib "eagle-import") (part "R-EU_R0805"))
    )
    (comp (ref "R37")
      (value "1k")
      (footprint "eagle-import:R0805")
      (libsource (lib "eagle-import") (part "R-EU_R0805"))
    )
    (comp (ref "R38")
      (value "1k")
      (footprint "eagle-import:R0805")
      (libsource (lib "eagle-import") (part "R-EU_R0805"))
    )
    (comp (ref "R39")
      (value "1.5k")
      (footprint "eagle-import:R0805")
      (libsource (lib "eagle-import") (part "R-EU_R0805"))
    )
    (comp (ref "R40")
      (value "10k")
      (footprint "eagle-import:R0805")
      (libsource (lib "eagle-import") (part "R-EU_R0805"))
    )
    (comp (ref "R41")
      (value "1k")
      (footprint "eagle-import:R0805")
      (libsource (lib "eagle-import") (part "R-EU_R0805"))
    )
    (comp (ref "R42")
      (value "10k")
      (footprint "eagle-import:R0805")
      (libsource (lib "eagle-import") (part "R-EU_R0805"))
    )
    (comp (ref "R43")
      (value "1k")
      (footprint "eagle-import:R0805")
      (libsource (lib "eagle-import") (part "R-EU_R0805"))
    )
    (comp (ref "R44")
      (value "1k")
      (footprint "eagle-import:R0805")
      (libsource (lib "eagle-import") (part "R-EU_R0805"))
    )
    (comp (ref "R45")
      (value "1k")
      (footprint "eagle-import:R0805")
      (libsource (lib "eagle-import") (part "R-EU_R0805"))
    )
    (comp (ref "R46")
      (value "1.5k")
      (footprint "eagle-import:R0805")
      (libsource (lib "eagle-import") (part "R-EU_R0805"))
    )
    (comp (ref "R47")
      (value "3k3")
      (footprint "eagle-import:R0805")
      (libsource (lib "eagle-import") (part "R-EU_R0805"))
    )
    (comp (ref "R48")
      (value "3k3")
      (footprint "eagle-import:R0805")
      (libsource (lib "eagle-import") (part "R-EU_R0805"))
    )
    (comp (ref "R49")
      (value "200")
      (footprint "eagle-import:R0805")
      (libsource (lib "eagle-import") (part "R-EU_R0805"))
    )
    (comp (ref "R50")
      (value "3k3")
      (footprint "eagle-import:R0805")
      (libsource (lib "eagle-import") (part "R-EU_R0805"))
    )
    (comp (ref "R51")
      (value "3k3")
      (footprint "eagle-import:R0805")
      (libsource (lib "eagle-import") (part "R-EU_R0805"))
    )
    (comp (ref "R52")
      (value "200")
      (footprint "eagle-import:R0805")
      (libsource (lib "eagle-import") (part "R-EU_R0805"))
    )
    (comp (ref "R53")
      (value "3k3")
      (footprint "eagle-import:R0805")
      (libsource (lib "eagle-import") (part "R-EU_R0805"))
    )
    (comp (ref "R54")
      (value "3k3")
      (footprint "eagle-import:R0805")
      (libsource (lib "eagle-import") (part "R-EU_R0805"))
    )
    (comp (ref "R55")
      (value "200")
      (footprint "eagle-import:R0805")
      (libsource (lib "eagle-import") (part "R-EU_R0805"))
    )
    (comp (ref "R56")
      (value "2k")
      (footprint "eagle-import:R0805")
      (libsource (lib "eagle-import") (part "R-EU_R0805"))
    )
    (comp (ref "R57")
      (value "200")
      (footprint "eagle-import:R0805")
      (libsource (lib "eagle-import") (part "R-EU_R0805"))
    )
    (comp (ref "R58")
      (value "100")
      (footprint "eagle-import:R0805")
      (libsource (lib "eagle-import") (part "R-EU_R0805"))
    )
    (comp (ref "R60")
      (value "TRIM_EU-CA6V")
      (footprint "eagle-import:CA6V")
      (libsource (lib "eagle-import") (part "TRIM_EU-CA6V"))
    )
    (comp (ref "R61")
      (value "TRIM_EU-CA6V")
      (footprint "eagle-import:CA6V")
      (libsource (lib "eagle-import") (part "TRIM_EU-CA6V"))
    )
    (comp (ref "R62")
      (value "TRIM_EU-CA6V")
      (footprint "eagle-import:CA6V")
      (libsource (lib "eagle-import") (part "TRIM_EU-CA6V"))
    )
    (comp (ref "R63")
      (value "TRIM_EU-CA6V")
      (footprint "eagle-import:CA6V")
      (libsource (lib "eagle-import") (part "TRIM_EU-CA6V"))
    )
    (comp (ref "R64")
      (value "4.7M")
      (footprint "eagle-import:R0805")
      (libsource (lib "eagle-import") (part "R-EU_R0805"))
    )
    (comp (ref "R65")
      (value "1.6k")
      (footprint "eagle-import:R0805")
      (libsource (lib "eagle-import") (part "R-EU_R0805"))
    )
    (comp (ref "R66")
      (value "16k")
      (footprint "eagle-import:R0805")
      (libsource (lib "eagle-import") (part "R-EU_R0805"))
    )
    (comp (ref "R67")
      (value "2.4k")
      (footprint "eagle-import:R0805")
      (libsource (lib "eagle-import") (part "R-EU_R0805"))
    )
    (comp (ref "R68")
      (value "75")
      (footprint "eagle-import:R0805")
      (libsource (lib "eagle-import") (part "R-EU_R0805"))
    )
    (comp (ref "R69")
      (value "75")
      (footprint "eagle-import:R0805")
      (libsource (lib "eagle-import") (part "R-EU_R0805"))
    )
    (comp (ref "R70")
      (value "75")
      (footprint "eagle-import:R0805")
      (libsource (lib "eagle-import") (part "R-EU_R0805"))
    )
    (comp (ref "R71")
      (value "47k")
      (footprint "eagle-import:R0805")
      (libsource (lib "eagle-import") (part "R-EU_R0805"))
    )
    (comp (ref "RD")
      (value "PINHD-1X1")
      (footprint "eagle-import:1X01")
      (libsource (lib "eagle-import") (part "PINHD-1X1"))
    )
    (comp (ref "RES")
      (value "PINHD-1X1")
      (footprint "eagle-import:1X01")
      (libsource (lib "eagle-import") (part "PINHD-1X1"))
    )
    (comp (ref "RFSH")
      (value "PINHD-1X1")
      (footprint "eagle-import:1X01")
      (libsource (lib "eagle-import") (part "PINHD-1X1"))
    )
    (comp (ref "ROM")
      (value "PINHD-1X1")
      (footprint "eagle-import:1X01")
      (libsource (lib "eagle-import") (part "PINHD-1X1"))
    )
    (comp (ref "ROMCE")
      (value "SJ")
      (footprint "eagle-import:SJ")
      (libsource (lib "eagle-import") (part "SJ"))
    )
    (comp (ref "S1")
      (value "RESET")
      (footprint "eagle-import:B3F-10XX")
      (fields (field (name "MPN") "B3F-1000") (field (name "MF") "OMRON ELECTRONIC COMPONENTS"))
      (libsource (lib "eagle-import") (part "10-XX"))
    )
    (comp (ref "SSWR")
      (value "PINHD-1X1")
      (footprint "eagle-import:1X01")
      (libsource (lib "eagle-import") (part "PINHD-1X1"))
    )
    (comp (ref "T1")
      (value "BC549-NPN-TO92-CBE")
      (footprint "eagle-import:TO92-CBE")
      (libsource (lib "eagle-import") (part "-NPN-TO92-CBEBC549"))
    )
    (comp (ref "T2")
      (value "BC549-NPN-TO92-CBE")
      (footprint "eagle-import:TO92-CBE")
      (libsource (lib "eagle-import") (part "-NPN-TO92-CBEBC549"))
    )
    (comp (ref "T3")
      (value "BC549-NPN-TO92-CBE")
      (footprint "eagle-import:TO92-CBE")
      (libsource (lib "eagle-import") (part "-NPN-TO92-CBEBC549"))
    )
    (comp (ref "T4")
      (value "BC549-NPN-TO92-CBE")
      (footprint "eagle-import:TO92-CBE")
      (libsource (lib "eagle-import") (part "-NPN-TO92-CBEBC549"))
    )
    (comp (ref "TI")
      (value "PINHD-1X2")
      (footprint "eagle-import:1X02")
      (libsource (lib "eagle-import") (part "PINHD-1X2"))
    )
    (comp (ref "TO")
      (value "PINHD-1X2")
      (footprint "eagle-import:1X02")
      (libsource (lib "eagle-import") (part "PINHD-1X2"))
    )
    (comp (ref "WAIT")
      (value "PINHD-1X1")
      (footprint "eagle-import:1X01")
      (libsource (lib "eagle-import") (part "PINHD-1X1"))
    )
    (comp (ref "WR")
      (value "PINHD-1X1")
      (footprint "eagle-import:1X01")
      (libsource (lib "eagle-import") (part "PINHD-1X1"))
    )
    (comp (ref "X1")
      (value "RCA_L")
      (footprint "eagle-import:TOBU3")
      (fields (field (name "MF") "FARNELL") (field (name "MPN") "TOBU 3") (field (name "MF_1") "HIRSCHMANN"))
      (libsource (lib "eagle-import") (part "TOBU3"))
    )
    (comp (ref "X2")
      (value "RCA_R")
      (footprint "eagle-import:TOBU3")
      (fields (field (name "MF") "FARNELL") (field (name "MPN") "TOBU 3") (field (name "MF_1") "HIRSCHMANN"))
      (libsource (lib "eagle-import") (part "TOBU3"))
    )
    (comp (ref "X3")
      (value "RGB-OUT")
      (footprint "eagle-import:H5M09RA")
      (libsource (lib "eagle-import") (part "D-SUB9-H5M09RA"))
    )
    (comp (ref "X4")
      (value "JOY-1")
      (footprint "eagle-import:M15HP")
      (libsource (lib "eagle-import") (part "M15HP"))
    )
    (comp (ref "X5")
      (value "JOY-2")
      (footprint "eagle-import:M15HP")
      (libsource (lib "eagle-import") (part "M15HP"))
    )
    (comp (ref "X6")
      (value "Video")
      (footprint "eagle-import:TOBU3")
      (fields (field (name "MF") "FARNELL") (field (name "MPN") "TOBU 3") (field (name "MF_1") "HIRSCHMANN"))
      (libsource (lib "eagle-import") (part "TOBU3"))
    )
    (comp (ref "X7")
      (value "s-video")
      (footprint "eagle-import:M_DIN4")
      (libsource (lib "eagle-import") (part "MINI_DIN_4"))
    )
    (comp (ref "X8")
      (value "SCART-F")
      (footprint "eagle-import:SCART-F")
      (libsource (lib "eagle-import") (part "SCART-F"))
    )
  )
  (nets
    (net (code "1") (name "+5V") (class "Default")
      (node (ref "C27") (pin "1") (pinfunction "1_1") (pintype "passive"))
      (node (ref "C28") (pin "+") (pinfunction "+_+") (pintype "passive"))
      (node (ref "C29") (pin "1") (pinfunction "1_1") (pintype "passive"))
      (node (ref "C30") (pin "+") (pinfunction "+_+") (pintype "passive"))
      (node (ref "C40") (pin "1") (pinfunction "1_1") (pintype "passive"))
      (node (ref "C41") (pin "+") (pinfunction "+_+") (pintype "passive"))
      (node (ref "C42") (pin "1") (pinfunction "1_1") (pintype "passive"))
      (node (ref "C43") (pin "+") (pinfunction "+_+") (pintype "passive"))
      (node (ref "C47") (pin "+") (pinfunction "+_+") (pintype "passive"))
      (node (ref "C5") (pin "2") (pinfunction "2_2") (pintype "passive"))
      (node (ref "CN1") (pin "1") (pinfunction "1_1") (pintype "bidirectional"))
      (node (ref "CN1") (pin "47") (pinfunction "47_47") (pintype "bidirectional"))
      (node (ref "D12") (pin "C") (pinfunction "C_C") (pintype "passive"))
      (node (ref "DD1") (pin "14") (pinfunction "VCC_14") (pintype "power_in"))
      (node (ref "DD2") (pin "11") (pinfunction "VCC_11") (pintype "power_in"))
      (node (ref "DD3") (pin "1") (pinfunction "VPP_1") (pintype "passive"))
      (node (ref "DD3") (pin "31") (pinfunction "~{PGM}_31") (pintype "passive"))
      (node (ref "DD3") (pin "32") (pinfunction "VCC_32") (pintype "power_in"))
      (node (ref "DD4") (pin "64") (pinfunction "64_64") (pintype "passive"))
      (node (ref "DD5") (pin "9") (pinfunction "VCC_9") (pintype "power_in"))
      (node (ref "DD6") (pin "9") (pinfunction "VCC_9") (pintype "power_in"))
      (node (ref "IC12") (pin "40") (pinfunction "VCC_40") (pintype "bidirectional"))
      (node (ref "IC16") (pin "5") (pinfunction "VCC_5") (pintype "power_in"))
      (node (ref "IC22") (pin "12") (pinfunction "12_12") (pintype "passive"))
      (node (ref "IC22") (pin "19") (pinfunction "19_19") (pintype "passive"))
      (node (ref "J1") (pin "RING") (pinfunction "RING_RING") (pintype "bidirectional"))
      (node (ref "J1") (pin "RING_SW") (pinfunction "RING_SW_RING_SW") (pintype "bidirectional"))
      (node (ref "JB4") (pin "1") (pinfunction "1_1") (pintype "passive"))
      (node (ref "JP1A") (pin "3") (pinfunction "3_3") (pintype "passive"))
      (node (ref "JP1B") (pin "1") (pinfunction "1_1") (pintype "passive"))
      (node (ref "JP3") (pin "10") (pinfunction "10_10") (pintype "passive"))
      (node (ref "L1") (pin "1") (pinfunction "1_1") (pintype "passive"))
      (node (ref "R10") (pin "1") (pinfunction "1_1") (pintype "passive"))
      (node (ref "R11") (pin "1") (pinfunction "1_1") (pintype "passive"))
      (node (ref "R12") (pin "1") (pinfunction "1_1") (pintype "passive"))
      (node (ref "R13") (pin "1") (pinfunction "1_1") (pintype "passive"))
      (node (ref "R14") (pin "1") (pinfunction "1_1") (pintype "passive"))
      (node (ref "R3") (pin "2") (pinfunction "2_2") (pintype "passive"))
      (node (ref "R38") (pin "1") (pinfunction "1_1") (pintype "passive"))
      (node (ref "R4") (pin "1") (pinfunction "1_1") (pintype "passive"))
      (node (ref "R40") (pin "1") (pinfunction "1_1") (pintype "passive"))
      (node (ref "R41") (pin "2") (pinfunction "2_2") (pintype "passive"))
      (node (ref "R42") (pin "2") (pinfunction "2_2") (pintype "passive"))
      (node (ref "R5") (pin "1") (pinfunction "1_1") (pintype "passive"))
      (node (ref "R58") (pin "2") (pinfunction "2_2") (pintype "passive"))
      (node (ref "R6") (pin "1") (pinfunction "1_1") (pintype "passive"))
      (node (ref "R67") (pin "1") (pinfunction "1_1") (pintype "passive"))
      (node (ref "R7") (pin "1") (pinfunction "1_1") (pintype "passive"))
      (node (ref "R8") (pin "1") (pinfunction "1_1") (pintype "passive"))
      (node (ref "R9") (pin "1") (pinfunction "1_1") (pintype "passive"))
      (node (ref "X4") (pin "15") (pinfunction "15_15") (pintype "passive"))
      (node (ref "X5") (pin "15") (pinfunction "15_15") (pintype "passive"))
    )
    (net (code "2") (name "/1IC8") (class "Default")
      (node (ref "JP1A1") (pin "1") (pinfunction "1_1") (pintype "passive"))
      (node (ref "JPORT") (pin "3") (pinfunction "3_3") (pintype "passive"))
    )
    (net (code "3") (name "/8M") (class "Default")
      (node (ref "DD4") (pin "33") (pinfunction "33_33") (pintype "passive"))
      (node (ref "IC1") (pin "11") (pinfunction "O_11") (pintype "output"))
      (node (ref "Q1") (pin "2") (pinfunction "2_2") (pintype "passive"))
      (node (ref "R2") (pin "2") (pinfunction "2_2") (pintype "passive"))
    )
    (net (code "4") (name "/A0") (class "Default")
      (node (ref "A0") (pin "1") (pinfunction "1_1") (pintype "passive"))
      (node (ref "DD2") (pin "30") (pinfunction "A0_30") (pintype "output"))
      (node (ref "DD3") (pin "12") (pinfunction "A0_12") (pintype "input"))
      (node (ref "DD4") (pin "47") (pinfunction "47_47") (pintype "passive"))
    )
    (net (code "5") (name "/A1") (class "Default")
      (node (ref "A1") (pin "1") (pinfunction "1_1") (pintype "passive"))
      (node (ref "DD2") (pin "31") (pinfunction "A1_31") (pintype "output"))
      (node (ref "DD3") (pin "11") (pinfunction "A1_11") (pintype "input"))
      (node (ref "DD4") (pin "56") (pinfunction "56_56") (pintype "passive"))
    )
    (net (code "6") (name "/A2") (class "Default")
      (node (ref "A2") (pin "1") (pinfunction "1_1") (pintype "passive"))
      (node (ref "DD2") (pin "32") (pinfunction "A2_32") (pintype "output"))
      (node (ref "DD3") (pin "10") (pinfunction "A2_10") (pintype "input"))
      (node (ref "DD4") (pin "55") (pinfunction "55_55") (pintype "passive"))
    )
    (net (code "7") (name "/A3") (class "Default")
      (node (ref "A3") (pin "1") (pinfunction "1_1") (pintype "passive"))
      (node (ref "DD2") (pin "33") (pinfunction "A3_33") (pintype "output"))
      (node (ref "DD3") (pin "9") (pinfunction "A3_9") (pintype "input"))
      (node (ref "DD4") (pin "51") (pinfunction "51_51") (pintype "passive"))
    )
    (net (code "8") (name "/A4") (class "Default")
      (node (ref "A4") (pin "1") (pinfunction "1_1") (pintype "passive"))
      (node (ref "DD2") (pin "34") (pinfunction "A4_34") (pintype "output"))
      (node (ref "DD3") (pin "8") (pinfunction "A4_8") (pintype "input"))
      (node (ref "DD4") (pin "49") (pinfunction "49_49") (pintype "passive"))
    )
    (net (code "9") (name "/A5") (class "Default")
      (node (ref "A5") (pin "1") (pinfunction "1_1") (pintype "passive"))
      (node (ref "DD2") (pin "35") (pinfunction "A5_35") (pintype "output"))
      (node (ref "DD3") (pin "7") (pinfunction "A5_7") (pintype "input"))
      (node (ref "DD4") (pin "62") (pinfunction "62_62") (pintype "passive"))
    )
    (net (code "10") (name "/A6") (class "Default")
      (node (ref "A6") (pin "1") (pinfunction "1_1") (pintype "passive"))
      (node (ref "DD2") (pin "36") (pinfunction "A6_36") (pintype "output"))
      (node (ref "DD3") (pin "6") (pinfunction "A6_6") (pintype "input"))
      (node (ref "DD4") (pin "39") (pinfunction "39_39") (pintype "passive"))
    )
    (net (code "11") (name "/A7") (class "Default")
      (node (ref "A7") (pin "1") (pinfunction "1_1") (pintype "passive"))
      (node (ref "DD2") (pin "37") (pinfunction "A7_37") (pintype "output"))
      (node (ref "DD3") (pin "5") (pinfunction "A7_5") (pintype "input"))
      (node (ref "DD4") (pin "37") (pinfunction "37_37") (pintype "passive"))
    )
    (net (code "12") (name "/A8") (class "Default")
      (node (ref "A8") (pin "1") (pinfunction "1_1") (pintype "passive"))
      (node (ref "D4") (pin "C") (pinfunction "C_C") (pintype "passive"))
      (node (ref "DD2") (pin "38") (pinfunction "A8_38") (pintype "output"))
      (node (ref "DD3") (pin "27") (pinfunction "A8_27") (pintype "input"))
      (node (ref "DD4") (pin "59") (pinfunction "59_59") (pintype "passive"))
    )
    (net (code "13") (name "/A9") (class "Default")
      (node (ref "A9") (pin "1") (pinfunction "1_1") (pintype "passive"))
      (node (ref "D5") (pin "C") (pinfunction "C_C") (pintype "passive"))
      (node (ref "DD2") (pin "39") (pinfunction "A9_39") (pintype "output"))
      (node (ref "DD3") (pin "26") (pinfunction "A9_26") (pintype "input"))
      (node (ref "DD4") (pin "61") (pinfunction "61_61") (pintype "passive"))
    )
    (net (code "14") (name "/A10") (class "Default")
      (node (ref "A10") (pin "1") (pinfunction "1_1") (pintype "passive"))
      (node (ref "D6") (pin "C") (pinfunction "C_C") (pintype "passive"))
      (node (ref "DD2") (pin "40") (pinfunction "A10_40") (pintype "output"))
      (node (ref "DD3") (pin "23") (pinfunction "A10_23") (pintype "input"))
      (node (ref "DD4") (pin "58") (pinfunction "58_58") (pintype "passive"))
    )
    (net (code "15") (name "/A11") (class "Default")
      (node (ref "A11") (pin "1") (pinfunction "1_1") (pintype "passive"))
      (node (ref "D7") (pin "C") (pinfunction "C_C") (pintype "passive"))
      (node (ref "DD2") (pin "1") (pinfunction "A11_1") (pintype "output"))
      (node (ref "DD3") (pin "25") (pinfunction "A11_25") (pintype "input"))
      (node (ref "DD4") (pin "60") (pinfunction "60_60") (pintype "passive"))
    )
    (net (code "16") (name "/A12") (class "Default")
      (node (ref "A12") (pin "1") (pinfunction "1_1") (pintype "passive"))
      (node (ref "D8") (pin "C") (pinfunction "C_C") (pintype "passive"))
      (node (ref "DD2") (pin "2") (pinfunction "A12_2") (pintype "output"))
      (node (ref "DD3") (pin "4") (pinfunction "A12_4") (pintype "input"))
      (node (ref "DD4") (pin "42") (pinfunction "42_42") (pintype "passive"))
    )
    (net (code "17") (name "/A13") (class "Default")
      (node (ref "A13") (pin "1") (pinfunction "1_1") (pintype "passive"))
      (node (ref "D9") (pin "C") (pinfunction "C_C") (pintype "passive"))
      (node (ref "DD2") (pin "3") (pinfunction "A13_3") (pintype "output"))
      (node (ref "DD3") (pin "28") (pinfunction "A13_28") (pintype "input"))
      (node (ref "DD4") (pin "57") (pinfunction "57_57") (pintype "passive"))
    )
    (net (code "18") (name "/A14") (class "Default")
      (node (ref "A14") (pin "1") (pinfunction "1_1") (pintype "passive"))
      (node (ref "D10") (pin "C") (pinfunction "C_C") (pintype "passive"))
      (node (ref "DD2") (pin "4") (pinfunction "A14_4") (pintype "output"))
      (node (ref "DD4") (pin "41") (pinfunction "41_41") (pintype "passive"))
    )
    (net (code "19") (name "/A15") (class "Default")
      (node (ref "A15") (pin "1") (pinfunction "1_1") (pintype "passive"))
      (node (ref "D11") (pin "C") (pinfunction "C_C") (pintype "passive"))
      (node (ref "DD2") (pin "5") (pinfunction "A15_5") (pintype "output"))
      (node (ref "DD4") (pin "38") (pinfunction "38_38") (pintype "passive"))
    )
    (net (code "20") (name "/AR0") (class "Default")
      (node (ref "AR0") (pin "1") (pinfunction "1_1") (pintype "passive"))
      (node (ref "DD4") (pin "50") (pinfunction "50_50") (pintype "passive"))
      (node (ref "DD5") (pin "14") (pinfunction "A0_14") (pintype "input"))
      (node (ref "DD6") (pin "14") (pinfunction "A0_14") (pintype "input"))
    )
    (net (code "21") (name "/AR1") (class "Default")
      (node (ref "AR1") (pin "1") (pinfunction "1_1") (pintype "passive"))
      (node (ref "DD4") (pin "53") (pinfunction "53_53") (pintype "passive"))
      (node (ref "DD5") (pin "13") (pinfunction "A1_13") (pintype "input"))
      (node (ref "DD6") (pin "13") (pinfunction "A1_13") (pintype "input"))
    )
    (net (code "22") (name "/AR2") (class "Default")
      (node (ref "AR2") (pin "1") (pinfunction "1_1") (pintype "passive"))
      (node (ref "DD4") (pin "52") (pinfunction "52_52") (pintype "passive"))
      (node (ref "DD5") (pin "12") (pinfunction "A2_12") (pintype "input"))
      (node (ref "DD6") (pin "12") (pinfunction "A2_12") (pintype "input"))
    )
    (net (code "23") (name "/AR3") (class "Default")
      (node (ref "AR3") (pin "1") (pinfunction "1_1") (pintype "passive"))
      (node (ref "DD4") (pin "48") (pinfunction "48_48") (pintype "passive"))
      (node (ref "DD5") (pin "11") (pinfunction "A3_11") (pintype "input"))
      (node (ref "DD6") (pin "11") (pinfunction "A3_11") (pintype "input"))
    )
    (net (code "24") (name "/AR4") (class "Default")
      (node (ref "AR4") (pin "1") (pinfunction "1_1") (pintype "passive"))
      (node (ref "DD4") (pin "46") (pinfunction "46_46") (pintype "passive"))
      (node (ref "DD5") (pin "8") (pinfunction "A4_8") (pintype "input"))
      (node (ref "DD6") (pin "8") (pinfunction "A4_8") (pintype "input"))
    )
    (net (code "25") (name "/AR5") (class "Default")
      (node (ref "AR5") (pin "1") (pinfunction "1_1") (pintype "passive"))
      (node (ref "DD4") (pin "54") (pinfunction "54_54") (pintype "passive"))
      (node (ref "DD5") (pin "7") (pinfunction "A5_7") (pintype "input"))
      (node (ref "DD6") (pin "7") (pinfunction "A5_7") (pintype "input"))
    )
    (net (code "26") (name "/AR6") (class "Default")
      (node (ref "AR6") (pin "1") (pinfunction "1_1") (pintype "passive"))
      (node (ref "DD4") (pin "45") (pinfunction "45_45") (pintype "passive"))
      (node (ref "DD5") (pin "6") (pinfunction "A6_6") (pintype "input"))
      (node (ref "DD6") (pin "6") (pinfunction "A6_6") (pintype "input"))
    )
    (net (code "27") (name "/AR7") (class "Default")
      (node (ref "AR7") (pin "1") (pinfunction "1_1") (pintype "passive"))
      (node (ref "DD4") (pin "44") (pinfunction "44_44") (pintype "passive"))
      (node (ref "DD5") (pin "10") (pinfunction "A7_10") (pintype "input"))
      (node (ref "DD6") (pin "10") (pinfunction "A7_10") (pintype "input"))
    )
    (net (code "28") (name "/B") (class "Default")
      (node (ref "DD4") (pin "10") (pinfunction "10_10") (pintype "passive"))
      (node (ref "IC21") (pin "9") (pinfunction "C_9") (pintype "input"))
      (node (ref "JP3") (pin "5") (pinfunction "5_5") (pintype "passive"))
      (node (ref "R45") (pin "2") (pinfunction "2_2") (pintype "passive"))
    )
    (net (code "29") (name "/B0") (class "Default")
      (node (ref "B0") (pin "1") (pinfunction "1_1") (pintype "passive"))
      (node (ref "DD3") (pin "29") (pinfunction "A14_29") (pintype "input"))
      (node (ref "DD7") (pin "2") (pinfunction "Q1_2") (pintype "output"))
      (node (ref "JB0") (pin "2") (pinfunction "2_2") (pintype "passive"))
    )
    (net (code "30") (name "/B1") (class "Default")
      (node (ref "B1") (pin "1") (pinfunction "1_1") (pintype "passive"))
      (node (ref "DD3") (pin "3") (pinfunction "A15_3") (pintype "input"))
      (node (ref "JB1") (pin "2") (pinfunction "2_2") (pintype "passive"))
      (node (ref "JP1A") (pin "2") (pinfunction "2_2") (pintype "passive"))
      (node (ref "JP1B") (pin "2") (pinfunction "2_2") (pintype "passive"))
    )
    (net (code "31") (name "/B2") (class "Default")
      (node (ref "B2") (pin "1") (pinfunction "1_1") (pintype "passive"))
      (node (ref "DD3") (pin "2") (pinfunction "A16_2") (pintype "input"))
      (node (ref "DD7") (pin "10") (pinfunction "Q3_10") (pintype "output"))
      (node (ref "JB2") (pin "2") (pinfunction "2_2") (pintype "passive"))
    )
    (net (code "32") (name "/B3") (class "Default")
      (node (ref "B3") (pin "1") (pinfunction "1_1") (pintype "passive"))
      (node (ref "DD3") (pin "30") (pinfunction "A17_30") (pintype "input"))
      (node (ref "JB3") (pin "2") (pinfunction "2_2") (pintype "passive"))
      (node (ref "JB4") (pin "2") (pinfunction "2_2") (pintype "passive"))
    )
    (net (code "33") (name "/BEEPER") (class "Default")
      (node (ref "DD4") (pin "15") (pinfunction "15_15") (pintype "passive"))
      (node (ref "R31") (pin "1") (pinfunction "1_1") (pintype "passive"))
      (node (ref "R33") (pin "1") (pinfunction "1_1") (pintype "passive"))
    )
    (net (code "34") (name "/CA") (class "Default")
      (node (ref "IC12") (pin "4") (pinfunction "AC/A_4") (pintype "bidirectional"))
      (node (ref "R35") (pin "2") (pinfunction "2_2") (pintype "passive"))
    )
    (net (code "35") (name "/CB") (class "Default")
      (node (ref "IC12") (pin "3") (pinfunction "AC/B_3") (pintype "bidirectional"))
      (node (ref "R32") (pin "2") (pinfunction "2_2") (pintype "passive"))
      (node (ref "R34") (pin "2") (pinfunction "2_2") (pintype "passive"))
    )
    (net (code "36") (name "/CC") (class "Default")
      (node (ref "IC12") (pin "38") (pinfunction "AC/C_38") (pintype "bidirectional"))
      (node (ref "R30") (pin "2") (pinfunction "2_2") (pintype "passive"))
    )
    (net (code "37") (name "/CLC2") (class "Default")
      (node (ref "IC12") (pin "22") (pinfunction "CLOCK_22") (pintype "bidirectional"))
      (node (ref "IC16") (pin "11") (pinfunction "QD_11") (pintype "output"))
    )
    (net (code "38") (name "/CLK") (class "Default")
      (node (ref "DD2") (pin "6") (pinfunction "CLK_6") (pintype "input"))
      (node (ref "DD4") (pin "31") (pinfunction "31_31") (pintype "passive"))
    )
    (net (code "39") (name "/D0") (class "Default")
      (node (ref "DD2") (pin "14") (pinfunction "D0_14") (pintype "bidirectional"))
      (node (ref "IC6") (pin "2") (pinfunction "A1_2") (pintype "bidirectional"))
      (node (ref "R22") (pin "1") (pinfunction "1_1") (pintype "passive"))
    )
    (net (code "40") (name "/D1") (class "Default")
      (node (ref "DD2") (pin "15") (pinfunction "D1_15") (pintype "bidirectional"))
      (node (ref "IC6") (pin "3") (pinfunction "A2_3") (pintype "bidirectional"))
      (node (ref "R15") (pin "1") (pinfunction "1_1") (pintype "passive"))
    )
    (net (code "41") (name "/D2") (class "Default")
      (node (ref "DD2") (pin "12") (pinfunction "D2_12") (pintype "bidirectional"))
      (node (ref "IC6") (pin "4") (pinfunction "A3_4") (pintype "bidirectional"))
      (node (ref "R16") (pin "1") (pinfunction "1_1") (pintype "passive"))
    )
    (net (code "42") (name "/D3") (class "Default")
      (node (ref "DD2") (pin "8") (pinfunction "D3_8") (pintype "bidirectional"))
      (node (ref "IC6") (pin "5") (pinfunction "A4_5") (pintype "bidirectional"))
      (node (ref "R17") (pin "1") (pinfunction "1_1") (pintype "passive"))
    )
    (net (code "43") (name "/D4") (class "Default")
      (node (ref "DD2") (pin "7") (pinfunction "D4_7") (pintype "bidirectional"))
      (node (ref "IC6") (pin "6") (pinfunction "A5_6") (pintype "bidirectional"))
      (node (ref "R18") (pin "1") (pinfunction "1_1") (pintype "passive"))
    )
    (net (code "44") (name "/D5") (class "Default")
      (node (ref "DD2") (pin "9") (pinfunction "D5_9") (pintype "bidirectional"))
      (node (ref "IC6") (pin "7") (pinfunction "A6_7") (pintype "bidirectional"))
      (node (ref "R19") (pin "1") (pinfunction "1_1") (pintype "passive"))
    )
    (net (code "45") (name "/D6") (class "Default")
      (node (ref "DD2") (pin "10") (pinfunction "D6_10") (pintype "bidirectional"))
      (node (ref "IC6") (pin "8") (pinfunction "A7_8") (pintype "bidirectional"))
      (node (ref "R20") (pin "1") (pinfunction "1_1") (pintype "passive"))
    )
    (net (code "46") (name "/D7") (class "Default")
      (node (ref "DD2") (pin "13") (pinfunction "D7_13") (pintype "bidirectional"))
      (node (ref "IC6") (pin "9") (pinfunction "A8_9") (pintype "bidirectional"))
      (node (ref "R21") (pin "1") (pinfunction "1_1") (pintype "passive"))
    )
    (net (code "47") (name "/DB0") (class "Default")
      (node (ref "DB0") (pin "1") (pinfunction "1_1") (pintype "passive"))
      (node (ref "DD3") (pin "13") (pinfunction "O0_13") (pintype "output"))
      (node (ref "DD7") (pin "4") (pinfunction "D1_4") (pintype "input"))
      (node (ref "IC2") (pin "18") (pinfunction "Y1_18") (pintype "tri_state"))
      (node (ref "IC6") (pin "18") (pinfunction "B1_18") (pintype "bidirectional"))
      (node (ref "R5") (pin "2") (pinfunction "2_2") (pintype "passive"))
    )
    (net (code "48") (name "/DB1") (class "Default")
      (node (ref "DB1") (pin "1") (pinfunction "1_1") (pintype "passive"))
      (node (ref "DD3") (pin "14") (pinfunction "O1_14") (pintype "output"))
      (node (ref "DD7") (pin "5") (pinfunction "D2_5") (pintype "input"))
      (node (ref "IC2") (pin "16") (pinfunction "Y2_16") (pintype "tri_state"))
      (node (ref "IC6") (pin "17") (pinfunction "B2_17") (pintype "bidirectional"))
      (node (ref "R11") (pin "2") (pinfunction "2_2") (pintype "passive"))
    )
    (net (code "49") (name "/DB2") (class "Default")
      (node (ref "DB2") (pin "1") (pinfunction "1_1") (pintype "passive"))
      (node (ref "DD3") (pin "15") (pinfunction "O2_15") (pintype "output"))
      (node (ref "DD7") (pin "12") (pinfunction "D3_12") (pintype "input"))
      (node (ref "IC2") (pin "14") (pinfunction "Y3_14") (pintype "tri_state"))
      (node (ref "IC6") (pin "16") (pinfunction "B3_16") (pintype "bidirectional"))
      (node (ref "R6") (pin "2") (pinfunction "2_2") (pintype "passive"))
    )
    (net (code "50") (name "/DB3") (class "Default")
      (node (ref "DB3") (pin "1") (pinfunction "1_1") (pintype "passive"))
      (node (ref "DD3") (pin "17") (pinfunction "O3_17") (pintype "output"))
      (node (ref "IC2") (pin "12") (pinfunction "Y4_12") (pintype "tri_state"))
      (node (ref "IC6") (pin "15") (pinfunction "B4_15") (pintype "bidirectional"))
      (node (ref "R7") (pin "2") (pinfunction "2_2") (pintype "passive"))
    )
    (net (code "51") (name "/DB4") (class "Default")
      (node (ref "DB4") (pin "1") (pinfunction "1_1") (pintype "passive"))
      (node (ref "DD3") (pin "18") (pinfunction "O4_18") (pintype "output"))
      (node (ref "IC2") (pin "9") (pinfunction "Y1_9") (pintype "tri_state"))
      (node (ref "IC6") (pin "14") (pinfunction "B5_14") (pintype "bidirectional"))
      (node (ref "R8") (pin "2") (pinfunction "2_2") (pintype "passive"))
    )
    (net (code "52") (name "/DB5") (class "Default")
      (node (ref "DB5") (pin "1") (pinfunction "1_1") (pintype "passive"))
      (node (ref "DD3") (pin "19") (pinfunction "O5_19") (pintype "output"))
      (node (ref "IC2") (pin "7") (pinfunction "Y2_7") (pintype "tri_state"))
      (node (ref "IC6") (pin "13") (pinfunction "B6_13") (pintype "bidirectional"))
      (node (ref "R9") (pin "2") (pinfunction "2_2") (pintype "passive"))
    )
    (net (code "53") (name "/DB6") (class "Default")
      (node (ref "DB6") (pin "1") (pinfunction "1_1") (pintype "passive"))
      (node (ref "DD3") (pin "20") (pinfunction "O6_20") (pintype "output"))
      (node (ref "IC2") (pin "5") (pinfunction "Y3_5") (pintype "tri_state"))
      (node (ref "IC6") (pin "12") (pinfunction "B7_12") (pintype "bidirectional"))
      (node (ref "R10") (pin "2") (pinfunction "2_2") (pintype "passive"))
    )
    (net (code "54") (name "/DB7") (class "Default")
      (node (ref "DB7") (pin "1") (pinfunction "1_1") (pintype "passive"))
      (node (ref "DD3") (pin "21") (pinfunction "O7_21") (pintype "output"))
      (node (ref "DD7") (pin "13") (pinfunction "D4_13") (pintype "input"))
      (node (ref "IC2") (pin "3") (pinfunction "Y4_3") (pintype "tri_state"))
      (node (ref "IC6") (pin "11") (pinfunction "B8_11") (pintype "bidirectional"))
      (node (ref "R12") (pin "2") (pinfunction "2_2") (pintype "passive"))
    )
    (net (code "55") (name "/DD7Q2") (class "Default")
      (node (ref "DD7") (pin "7") (pinfunction "Q2_7") (pintype "output"))
      (node (ref "JP1A") (pin "1") (pinfunction "1_1") (pintype "passive"))
      (node (ref "JP1B") (pin "3") (pinfunction "3_3") (pintype "passive"))
    )
    (net (code "56") (name "/DR0") (class "Default")
      (node (ref "DD4") (pin "3") (pinfunction "3_3") (pintype "passive"))
      (node (ref "DD5") (pin "2") (pinfunction "I/O1_2") (pintype "bidirectional"))
      (node (ref "DR0") (pin "1") (pinfunction "1_1") (pintype "passive"))
      (node (ref "R22") (pin "2") (pinfunction "2_2") (pintype "passive"))
    )
    (net (code "57") (name "/DR1") (class "Default")
      (node (ref "DD4") (pin "4") (pinfunction "4_4") (pintype "passive"))
      (node (ref "DD5") (pin "3") (pinfunction "I/O2_3") (pintype "bidirectional"))
      (node (ref "DR1") (pin "1") (pinfunction "1_1") (pintype "passive"))
      (node (ref "R15") (pin "2") (pinfunction "2_2") (pintype "passive"))
    )
    (net (code "58") (name "/DR2") (class "Default")
      (node (ref "DD4") (pin "6") (pinfunction "6_6") (pintype "passive"))
      (node (ref "DD5") (pin "15") (pinfunction "I/O3_15") (pintype "bidirectional"))
      (node (ref "DR2") (pin "1") (pinfunction "1_1") (pintype "passive"))
      (node (ref "R16") (pin "2") (pinfunction "2_2") (pintype "passive"))
    )
    (net (code "59") (name "/DR3") (class "Default")
      (node (ref "DD4") (pin "7") (pinfunction "7_7") (pintype "passive"))
      (node (ref "DD5") (pin "17") (pinfunction "I/O4_17") (pintype "bidirectional"))
      (node (ref "DR3") (pin "1") (pinfunction "1_1") (pintype "passive"))
      (node (ref "R17") (pin "2") (pinfunction "2_2") (pintype "passive"))
    )
    (net (code "60") (name "/DR4") (class "Default")
      (node (ref "DD4") (pin "14") (pinfunction "14_14") (pintype "passive"))
      (node (ref "DD6") (pin "2") (pinfunction "I/O1_2") (pintype "bidirectional"))
      (node (ref "DR4") (pin "1") (pinfunction "1_1") (pintype "passive"))
      (node (ref "R18") (pin "2") (pinfunction "2_2") (pintype "passive"))
    )
    (net (code "61") (name "/DR5") (class "Default")
      (node (ref "DD4") (pin "16") (pinfunction "16_16") (pintype "passive"))
      (node (ref "DD6") (pin "3") (pinfunction "I/O2_3") (pintype "bidirectional"))
      (node (ref "DR5") (pin "1") (pinfunction "1_1") (pintype "passive"))
      (node (ref "R19") (pin "2") (pinfunction "2_2") (pintype "passive"))
    )
    (net (code "62") (name "/DR6") (class "Default")
      (node (ref "DD4") (pin "17") (pinfunction "17_17") (pintype "passive"))
      (node (ref "DD6") (pin "15") (pinfunction "I/O3_15") (pintype "bidirectional"))
      (node (ref "DR6") (pin "1") (pinfunction "1_1") (pintype "passive"))
      (node (ref "R20") (pin "2") (pinfunction "2_2") (pintype "passive"))
    )
    (net (code "63") (name "/DR7") (class "Default")
      (node (ref "DD4") (pin "20") (pinfunction "20_20") (pintype "passive"))
      (node (ref "DD6") (pin "17") (pinfunction "I/O4_17") (pintype "bidirectional"))
      (node (ref "DR7") (pin "1") (pinfunction "1_1") (pintype "passive"))
      (node (ref "R21") (pin "2") (pinfunction "2_2") (pintype "passive"))
    )
    (net (code "64") (name "/G") (class "Default")
      (node (ref "DD4") (pin "12") (pinfunction "12_12") (pintype "passive"))
      (node (ref "IC21") (pin "10") (pinfunction "B_10") (pintype "input"))
      (node (ref "JP3") (pin "3") (pinfunction "3_3") (pintype "passive"))
      (node (ref "R44") (pin "2") (pinfunction "2_2") (pintype "passive"))
    )
    (net (code "65") (name "/KD0") (class "Default")
      (node (ref "DD4") (pin "1") (pinfunction "1_1") (pintype "passive"))
      (node (ref "KD0") (pin "1") (pinfunction "1_1") (pintype "passive"))
    )
    (net (code "66") (name "/KD1") (class "Default")
      (node (ref "DD4") (pin "2") (pinfunction "2_2") (pintype "passive"))
      (node (ref "KD1") (pin "1") (pinfunction "1_1") (pintype "passive"))
    )
    (net (code "67") (name "/KD2") (class "Default")
      (node (ref "DD4") (pin "5") (pinfunction "5_5") (pintype "passive"))
      (node (ref "KD2") (pin "1") (pinfunction "1_1") (pintype "passive"))
    )
    (net (code "68") (name "/KD3") (class "Default")
      (node (ref "DD4") (pin "8") (pinfunction "8_8") (pintype "passive"))
      (node (ref "KD3") (pin "1") (pinfunction "1_1") (pintype "passive"))
    )
    (net (code "69") (name "/KD4") (class "Default")
      (node (ref "DD4") (pin "9") (pinfunction "9_9") (pintype "passive"))
      (node (ref "KD4") (pin "1") (pinfunction "1_1") (pintype "passive"))
    )
    (net (code "70") (name "/KD6") (class "Default")
      (node (ref "TI") (pin "1") (pinfunction "1_1") (pintype "passive"))
    )
    (net (code "71") (name "/KJ0") (class "Default")
      (node (ref "IC18") (pin "15") (pinfunction "QA_15") (pintype "tri_state"))
      (node (ref "IC2") (pin "2") (pinfunction "A1_2") (pintype "input"))
    )
    (net (code "72") (name "/KJ1") (class "Default")
      (node (ref "IC18") (pin "1") (pinfunction "QB_1") (pintype "tri_state"))
      (node (ref "IC2") (pin "4") (pinfunction "A2_4") (pintype "input"))
    )
    (net (code "73") (name "/KJ2") (class "Default")
      (node (ref "IC18") (pin "2") (pinfunction "QC_2") (pintype "tri_state"))
      (node (ref "IC2") (pin "6") (pinfunction "A3_6") (pintype "input"))
    )
    (net (code "74") (name "/KJ3") (class "Default")
      (node (ref "IC18") (pin "3") (pinfunction "QD_3") (pintype "tri_state"))
      (node (ref "IC2") (pin "8") (pinfunction "A4_8") (pintype "input"))
    )
    (net (code "75") (name "/KJ4") (class "Default")
      (node (ref "IC18") (pin "6") (pinfunction "QG_6") (pintype "tri_state"))
      (node (ref "IC2") (pin "11") (pinfunction "A1_11") (pintype "input"))
    )
    (net (code "76") (name "/KJ5") (class "Default")
      (node (ref "IC2") (pin "13") (pinfunction "A2_13") (pintype "input"))
      (node (ref "IC20") (pin "4") (pinfunction "O_4") (pintype "output"))
    )
    (net (code "77") (name "/KJ6") (class "Default")
      (node (ref "IC18") (pin "4") (pinfunction "QE_4") (pintype "tri_state"))
      (node (ref "IC2") (pin "15") (pinfunction "A3_15") (pintype "input"))
    )
    (net (code "78") (name "/KJ7") (class "Default")
      (node (ref "IC2") (pin "17") (pinfunction "A4_17") (pintype "input"))
      (node (ref "IC20") (pin "2") (pinfunction "O_2") (pintype "output"))
    )
    (net (code "79") (name "/KJOY") (class "Default")
      (node (ref "DD8") (pin "11") (pinfunction "O_11") (pintype "output"))
      (node (ref "IC2") (pin "1") (pinfunction "G_1") (pintype "input"))
      (node (ref "IC2") (pin "19") (pinfunction "G_19") (pintype "input"))
    )
    (net (code "80") (name "/PBANK") (class "Default")
      (node (ref "DD1") (pin "12") (pinfunction "O_12") (pintype "output"))
      (node (ref "DD7") (pin "9") (pinfunction "CLK_9") (pintype "input"))
    )
    (net (code "81") (name "/R") (class "Default")
      (node (ref "DD4") (pin "11") (pinfunction "11_11") (pintype "passive"))
      (node (ref "IC21") (pin "11") (pinfunction "A_11") (pintype "input"))
      (node (ref "JP3") (pin "1") (pinfunction "1_1") (pintype "passive"))
      (node (ref "R43") (pin "2") (pinfunction "2_2") (pintype "passive"))
    )
    (net (code "82") (name "/RES") (class "Default")
      (node (ref "IC1") (pin "3") (pinfunction "O_3") (pintype "output"))
      (node (ref "IC1") (pin "4") (pinfunction "I0_4") (pintype "input"))
      (node (ref "IC1") (pin "5") (pinfunction "I1_5") (pintype "input"))
      (node (ref "RES") (pin "1") (pinfunction "1_1") (pintype "passive"))
    )
    (net (code "83") (name "/SL") (class "Default")
      (node (ref "C8") (pin "-") (pinfunction "-_-") (pintype "passive"))
      (node (ref "X1") (pin "1") (pinfunction "1_1") (pintype "passive"))
      (node (ref "X3") (pin "7") (pinfunction "F_7") (pintype "passive"))
    )
    (net (code "84") (name "/SOUND-IN") (class "Default")
      (node (ref "R29") (pin "2") (pinfunction "2_2") (pintype "passive"))
      (node (ref "R37") (pin "2") (pinfunction "2_2") (pintype "passive"))
    )
    (net (code "85") (name "/SR") (class "Default")
      (node (ref "C7") (pin "-") (pinfunction "-_-") (pintype "passive"))
      (node (ref "X2") (pin "1") (pinfunction "1_1") (pintype "passive"))
      (node (ref "X3") (pin "6") (pinfunction "F_6") (pintype "passive"))
    )
    (net (code "86") (name "/SYNC") (class "Default")
      (node (ref "DD4") (pin "43") (pinfunction "43_43") (pintype "passive"))
      (node (ref "JP3") (pin "7") (pinfunction "7_7") (pintype "passive"))
      (node (ref "R46") (pin "2") (pinfunction "2_2") (pintype "passive"))
    )
    (net (code "87") (name "/TAPE_IN") (class "Default")
      (node (ref "DD4") (pin "19") (pinfunction "19_19") (pintype "passive"))
      (node (ref "TI") (pin "2") (pinfunction "2_2") (pintype "passive"))
    )
    (net (code "88") (name "/TAPE_OUT") (class "Default")
      (node (ref "DD4") (pin "13") (pinfunction "13_13") (pintype "passive"))
      (node (ref "TO") (pin "2") (pinfunction "2_2") (pintype "passive"))
    )
    (net (code "89") (name "/TO") (class "Default")
      (node (ref "TO") (pin "1") (pinfunction "1_1") (pintype "passive"))
    )
    (net (code "90") (name "/Y") (class "Default")
      (node (ref "DD4") (pin "18") (pinfunction "18_18") (pintype "passive"))
      (node (ref "IC21") (pin "1") (pinfunction "D3_1") (pintype "input"))
      (node (ref "IC21") (pin "12") (pinfunction "D7_12") (pintype "input"))
      (node (ref "IC21") (pin "13") (pinfunction "D6_13") (pintype "input"))
      (node (ref "IC21") (pin "14") (pinfunction "D5_14") (pintype "input"))
      (node (ref "IC21") (pin "15") (pinfunction "D4_15") (pintype "input"))
      (node (ref "IC21") (pin "2") (pinfunction "D2_2") (pintype "input"))
      (node (ref "IC21") (pin "3") (pinfunction "D1_3") (pintype "input"))
    )
    (net (code "91") (name "/_1IC8") (class "Default")
      (node (ref "IC5") (pin "3") (pinfunction "O_3") (pintype "open_collector"))
      (node (ref "IC5") (pin "6") (pinfunction "O_6") (pintype "open_collector"))
      (node (ref "R4") (pin "2") (pinfunction "2_2") (pintype "passive"))
    )
    (net (code "92") (name "/_A1") (class "Default")
      (node (ref "DD1") (pin "11") (pinfunction "I_11") (pintype "input"))
      (node (ref "IC13") (pin "5") (pinfunction "G2B_5") (pintype "input"))
    )
    (net (code "93") (name "/_A14") (class "Default")
      (node (ref "IC13") (pin "2") (pinfunction "B_2") (pintype "input"))
    )
    (net (code "94") (name "/_A15") (class "Default")
      (node (ref "IC13") (pin "3") (pinfunction "C_3") (pintype "input"))
    )
    (net (code "95") (name "/_DB0") (class "Default")
      (node (ref "IC12") (pin "37") (pinfunction "DA0_37") (pintype "bidirectional"))
    )
    (net (code "96") (name "/_DB1") (class "Default")
      (node (ref "IC12") (pin "36") (pinfunction "DA1_36") (pintype "bidirectional"))
    )
    (net (code "97") (name "/_DB2") (class "Default")
      (node (ref "IC12") (pin "35") (pinfunction "DA2_35") (pintype "bidirectional"))
    )
    (net (code "98") (name "/_DB3") (class "Default")
      (node (ref "IC12") (pin "34") (pinfunction "DA3_34") (pintype "bidirectional"))
    )
    (net (code "99") (name "/_DB4") (class "Default")
      (node (ref "IC12") (pin "33") (pinfunction "DA4_33") (pintype "bidirectional"))
    )
    (net (code "100") (name "/_DB5") (class "Default")
      (node (ref "IC12") (pin "32") (pinfunction "DA5_32") (pintype "bidirectional"))
    )
    (net (code "101") (name "/_DB6") (class "Default")
      (node (ref "IC12") (pin "31") (pinfunction "DA6_31") (pintype "bidirectional"))
    )
    (net (code "102") (name "/_DB7") (class "Default")
      (node (ref "IC12") (pin "30") (pinfunction "DA7_30") (pintype "bidirectional"))
    )
    (net (code "103") (name "/_TO") (class "Default")
      (node (ref "IC12") (pin "21") (pinfunction "IOA0_21") (pintype "bidirectional"))
    )
    (net (code "104") (name "/_~{CE}") (class "Default")
      (node (ref "DD8") (pin "2") (pinfunction "I1_2") (pintype "input"))
      (node (ref "DD8") (pin "4") (pinfunction "I0_4") (pintype "input"))
      (node (ref "IC5") (pin "1") (pinfunction "I0_1") (pintype "input"))
    )
    (net (code "105") (name "/_~{IORQ}") (class "Default")
      (node (ref "IC13") (pin "4") (pinfunction "G2A_4") (pintype "input"))
    )
    (net (code "106") (name "/_~{M1}") (class "Default")
      (node (ref "IC13") (pin "6") (pinfunction "G1_6") (pintype "input"))
    )
    (net (code "108") (name "/_~{RES}") (class "Default")
      (node (ref "IC12") (pin "23") (pinfunction "~{RESET}_23") (pintype "bidirectional"))
    )
    (net (code "109") (name "/_~{ROM}") (class "Default")
      (node (ref "DD8") (pin "3") (pinfunction "O_3") (pintype "output"))
    )
    (net (code "110") (name "/_~{SSRD}") (class "Default")
      (node (ref "DD8") (pin "13") (pinfunction "I1_13") (pintype "input"))
      (node (ref "IC5") (pin "2") (pinfunction "I1_2") (pintype "input"))
    )
    (net (code "111") (name "/_~{SSWR}") (class "Default")
      (node (ref "DD8") (pin "9") (pinfunction "I0_9") (pintype "input"))
    )
    (net (code "112") (name "/_~{WR}") (class "Default")
      (node (ref "IC13") (pin "1") (pinfunction "A_1") (pintype "input"))
    )
    (net (code "113") (name "/~{BUSAK}") (class "Default")
      (node (ref "BUSAK") (pin "1") (pinfunction "1_1") (pintype "passive"))
      (node (ref "DD2") (pin "23") (pinfunction "BUSAK_23") (pintype "output"))
    )
    (net (code "114") (name "/~{BUSRQ}") (class "Default")
      (node (ref "BUSRQ") (pin "1") (pinfunction "1_1") (pintype "passive"))
      (node (ref "DD2") (pin "25") (pinfunction "BUSRQ_25") (pintype "input"))
      (node (ref "R14") (pin "2") (pinfunction "2_2") (pintype "passive"))
    )
    (net (code "115") (name "/~{CAS}") (class "Default")
      (node (ref "DD4") (pin "35") (pinfunction "35_35") (pintype "passive"))
      (node (ref "R24") (pin "2") (pinfunction "2_2") (pintype "passive"))
    )
    (net (code "116") (name "/~{CE}") (class "Default")
      (node (ref "CE") (pin "1") (pinfunction "1_1") (pintype "passive"))
      (node (ref "DD4") (pin "36") (pinfunction "36_36") (pintype "passive"))
      (node (ref "ROMCE") (pin "2") (pinfunction "2_2") (pintype "passive"))
    )
    (net (code "117") (name "/~{INT}") (class "Default")
      (node (ref "DD2") (pin "16") (pinfunction "INT_16") (pintype "input"))
      (node (ref "INT") (pin "1") (pinfunction "1_1") (pintype "passive"))
      (node (ref "R25") (pin "2") (pinfunction "2_2") (pintype "passive"))
    )
    (net (code "118") (name "/~{IORQ}") (class "Default")
      (node (ref "DD2") (pin "20") (pinfunction "IORQ_20") (pintype "output"))
      (node (ref "DD4") (pin "23") (pinfunction "23_23") (pintype "passive"))
      (node (ref "IORQ") (pin "1") (pinfunction "1_1") (pintype "passive"))
    )
    (net (code "119") (name "/~{M1}") (class "Default")
      (node (ref "DD2") (pin "27") (pinfunction "M1_27") (pintype "output"))
      (node (ref "DD4") (pin "22") (pinfunction "22_22") (pintype "passive"))
      (node (ref "M1") (pin "1") (pinfunction "1_1") (pintype "passive"))
    )
    (net (code "120") (name "/~{MREQ}") (class "Default")
      (node (ref "DD2") (pin "19") (pinfunction "MREQ_19") (pintype "output"))
      (node (ref "DD4") (pin "28") (pinfunction "28_28") (pintype "passive"))
      (node (ref "MREQ") (pin "1") (pinfunction "1_1") (pintype "passive"))
    )
    (net (code "121") (name "/~{NMI}") (class "Default")
      (node (ref "DD2") (pin "17") (pinfunction "NMI_17") (pintype "input"))
      (node (ref "NMI") (pin "1") (pinfunction "1_1") (pintype "passive"))
      (node (ref "R13") (pin "2") (pinfunction "2_2") (pintype "passive"))
    )
    (net (code "122") (name "/~{RAS}") (class "Default")
      (node (ref "DD4") (pin "40") (pinfunction "40_40") (pintype "passive"))
      (node (ref "R23") (pin "2") (pinfunction "2_2") (pintype "passive"))
    )
    (net (code "123") (name "/~{RD}") (class "Default")
      (node (ref "DD2") (pin "21") (pinfunction "RD_21") (pintype "output"))
      (node (ref "DD4") (pin "29") (pinfunction "29_29") (pintype "passive"))
      (node (ref "RD") (pin "1") (pinfunction "1_1") (pintype "passive"))
    )
    (net (code "124") (name "/~{RES}") (class "Default")
      (node (ref "/RES") (pin "1") (pinfunction "1_1") (pintype "passive"))
      (node (ref "DD2") (pin "26") (pinfunction "RESET_26") (pintype "input"))
      (node (ref "DD7") (pin "1") (pinfunction "CLR_1") (pintype "input"))
      (node (ref "IC1") (pin "6") (pinfunction "O_6") (pintype "output"))
    )
    (net (code "125") (name "/~{RFSH}") (class "Default")
      (node (ref "DD2") (pin "28") (pinfunction "RFSH_28") (pintype "output"))
      (node (ref "DD4") (pin "24") (pinfunction "24_24") (pintype "passive"))
      (node (ref "RFSH") (pin "1") (pinfunction "1_1") (pintype "passive"))
    )
    (net (code "126") (name "/~{ROMC}") (class "Default")
      (node (ref "DD8") (pin "6") (pinfunction "O_6") (pintype "output"))
    )
    (net (code "127") (name "/~{ROM}") (class "Default")
      (node (ref "DD3") (pin "22") (pinfunction "~{CE}_22") (pintype "passive"))
      (node (ref "ROM") (pin "1") (pinfunction "1_1") (pintype "passive"))
      (node (ref "ROMCE") (pin "1") (pinfunction "1_1") (pintype "passive"))
    )
    (net (code "128") (name "/~{SSRD}") (class "Default")
      (node (ref "DD4") (pin "27") (pinfunction "27_27") (pintype "passive"))
      (node (ref "JP1A1") (pin "3") (pinfunction "3_3") (pintype "passive"))
      (node (ref "JPORT") (pin "1") (pinfunction "1_1") (pintype "passive"))
    )
    (net (code "129") (name "/~{SSWR}") (class "Default")
      (node (ref "DD4") (pin "26") (pinfunction "26_26") (pintype "passive"))
      (node (ref "SSWR") (pin "1") (pinfunction "1_1") (pintype "passive"))
    )
    (net (code "130") (name "/~{WAIT}") (class "Default")
      (node (ref "DD2") (pin "24") (pinfunction "WAIT_24") (pintype "input"))
      (node (ref "DD4") (pin "34") (pinfunction "34_34") (pintype "passive"))
      (node (ref "WAIT") (pin "1") (pinfunction "1_1") (pintype "passive"))
    )
    (net (code "131") (name "/~{WE}") (class "Default")
      (node (ref "DD4") (pin "30") (pinfunction "30_30") (pintype "passive"))
      (node (ref "DD5") (pin "4") (pinfunction "~{WE}_4") (pintype "input"))
      (node (ref "DD6") (pin "4") (pinfunction "~{WE}_4") (pintype "input"))
    )
    (net (code "132") (name "/~{WR}") (class "Default")
      (node (ref "DD2") (pin "22") (pinfunction "WR_22") (pintype "output"))
      (node (ref "DD4") (pin "25") (pinfunction "25_25") (pintype "passive"))
      (node (ref "WR") (pin "1") (pinfunction "1_1") (pintype "passive"))
    )
    (net (code "133") (name "GND") (class "Default")
      (node (ref "C2") (pin "-") (pinfunction "-_-") (pintype "passive"))
      (node (ref "C22") (pin "-") (pinfunction "-_-") (pintype "passive"))
      (node (ref "C23") (pin "2") (pinfunction "2_2") (pintype "passive"))
      (node (ref "C27") (pin "2") (pinfunction "2_2") (pintype "passive"))
      (node (ref "C28") (pin "-") (pinfunction "-_-") (pintype "passive"))
      (node (ref "C29") (pin "2") (pinfunction "2_2") (pintype "passive"))
      (node (ref "C30") (pin "-") (pinfunction "-_-") (pintype "passive"))
      (node (ref "C34") (pin "2") (pinfunction "2_2") (pintype "passive"))
      (node (ref "C35") (pin "-") (pinfunction "-_-") (pintype "passive"))
      (node (ref "C36") (pin "2") (pinfunction "2_2") (pintype "passive"))
      (node (ref "C37") (pin "1") (pinfunction "1_1") (pintype "passive"))
      (node (ref "C38") (pin "1") (pinfunction "1_1") (pintype "passive"))
      (node (ref "C4") (pin "1") (pinfunction "1_1") (pintype "passive"))
      (node (ref "C40") (pin "2") (pinfunction "2_2") (pintype "passive"))
      (node (ref "C41") (pin "-") (pinfunction "-_-") (pintype "passive"))
      (node (ref "C42") (pin "2") (pinfunction "2_2") (pintype "passive"))
      (node (ref "C43") (pin "-") (pinfunction "-_-") (pintype "passive"))
      (node (ref "C47") (pin "-") (pinfunction "-_-") (pintype "passive"))
      (node (ref "C5") (pin "1") (pinfunction "1_1") (pintype "passive"))
      (node (ref "CN1") (pin "2") (pinfunction "2_2") (pintype "bidirectional"))
      (node (ref "CN1") (pin "48") (pinfunction "48_48") (pintype "bidirectional"))
      (node (ref "DD1") (pin "7") (pinfunction "GND_7") (pintype "power_in"))
      (node (ref "DD2") (pin "29") (pinfunction "GND_29") (pintype "power_in"))
      (node (ref "DD3") (pin "16") (pinfunction "GND_16") (pintype "power_in"))
      (node (ref "DD3") (pin "24") (pinfunction "~{OE}_24") (pintype "output"))
      (node (ref "DD4") (pin "32") (pinfunction "32_32") (pintype "passive"))
      (node (ref "DD4") (pin "63") (pinfunction "63_63") (pintype "passive"))
      (node (ref "DD5") (pin "1") (pinfunction "~{OE}_1") (pintype "input"))
      (node (ref "DD5") (pin "18") (pinfunction "VSS_18") (pintype "power_in"))
      (node (ref "DD6") (pin "1") (pinfunction "~{OE}_1") (pintype "input"))
      (node (ref "DD6") (pin "18") (pinfunction "VSS_18") (pintype "power_in"))
      (node (ref "IC12") (pin "1") (pinfunction "GND_1") (pintype "bidirectional"))
      (node (ref "IC12") (pin "24") (pinfunction "~{A9}_24") (pintype "bidirectional"))
      (node (ref "IC16") (pin "10") (pinfunction "GND_10") (pintype "power_in"))
      (node (ref "IC16") (pin "14") (pinfunction "CKA_14") (pintype "input"))
      (node (ref "IC16") (pin "2") (pinfunction "R0(1)_2") (pintype "input"))
      (node (ref "IC16") (pin "3") (pinfunction "R0(2)_3") (pintype "input"))
      (node (ref "IC17") (pin "13") (pinfunction "G_13") (pintype "input"))
      (node (ref "IC18") (pin "13") (pinfunction "G_13") (pintype "input"))
      (node (ref "IC21") (pin "4") (pinfunction "D0_4") (pintype "input"))
      (node (ref "IC21") (pin "7") (pinfunction "G_7") (pintype "input"))
      (node (ref "IC22") (pin "1") (pinfunction "1_1") (pintype "passive"))
      (node (ref "IC22") (pin "24") (pinfunction "24_24") (pintype "passive"))
      (node (ref "IC22") (pin "7") (pinfunction "7_7") (pintype "passive"))
      (node (ref "IC23") (pin "11") (pinfunction "I_11") (pintype "input"))
      (node (ref "IC23") (pin "13") (pinfunction "I_13") (pintype "input"))
      (node (ref "IC6") (pin "19") (pinfunction "G_19") (pintype "input"))
      (node (ref "J1") (pin "TIP") (pinfunction "TIP_TIP") (pintype "bidirectional"))
      (node (ref "JB0") (pin "1") (pinfunction "1_1") (pintype "passive"))
      (node (ref "JB1") (pin "1") (pinfunction "1_1") (pintype "passive"))
      (node (ref "JB2") (pin "1") (pinfunction "1_1") (pintype "passive"))
      (node (ref "JB3") (pin "1") (pinfunction "1_1") (pintype "passive"))
      (node (ref "JP3") (pin "2") (pinfunction "2_2") (pintype "passive"))
      (node (ref "JP4") (pin "2") (pinfunction "2_2") (pintype "passive"))
      (node (ref "R28") (pin "1") (pinfunction "1_1") (pintype "passive"))
      (node (ref "R36") (pin "1") (pinfunction "1_1") (pintype "passive"))
      (node (ref "R48") (pin "1") (pinfunction "1_1") (pintype "passive"))
      (node (ref "R49") (pin "1") (pinfunction "1_1") (pintype "passive"))
      (node (ref "R51") (pin "1") (pinfunction "1_1") (pintype "passive"))
      (node (ref "R52") (pin "1") (pinfunction "1_1") (pintype "passive"))
      (node (ref "R54") (pin "1") (pinfunction "1_1") (pintype "passive"))
      (node (ref "R55") (pin "1") (pinfunction "1_1") (pintype "passive"))
      (node (ref "R56") (pin "1") (pinfunction "1_1") (pintype "passive"))
      (node (ref "R57") (pin "1") (pinfunction "1_1") (pintype "passive"))
      (node (ref "R60") (pin "A") (pinfunction "A_A") (pintype "passive"))
      (node (ref "R61") (pin "A") (pinfunction "A_A") (pintype "passive"))
      (node (ref "R62") (pin "A") (pinfunction "A_A") (pintype "passive"))
      (node (ref "R63") (pin "A") (pinfunction "A_A") (pintype "passive"))
      (node (ref "R66") (pin "2") (pinfunction "2_2") (pintype "passive"))
      (node (ref "R71") (pin "1") (pinfunction "1_1") (pintype "passive"))
      (node (ref "S1") (pin "3") (pinfunction "P_3") (pintype "passive"))
      (node (ref "S1") (pin "4") (pinfunction "P1_4") (pintype "passive"))
      (node (ref "X1") (pin "2") (pinfunction "2_2") (pintype "passive"))
      (node (ref "X1") (pin "2@1") (pinfunction "2_2@1") (pintype "passive"))
      (node (ref "X1") (pin "2@2") (pinfunction "2_2@2") (pintype "passive"))
      (node (ref "X2") (pin "2") (pinfunction "2_2") (pintype "passive"))
      (node (ref "X2") (pin "2@1") (pinfunction "2_2@1") (pintype "passive"))
      (node (ref "X2") (pin "2@2") (pinfunction "2_2@2") (pintype "passive"))
      (node (ref "X3") (pin "1") (pinfunction "F_1") (pintype "passive"))
      (node (ref "X4") (pin "1") (pinfunction "1_1") (pintype "passive"))
      (node (ref "X5") (pin "1") (pinfunction "1_1") (pintype "passive"))
      (node (ref "X6") (pin "2") (pinfunction "2_2") (pintype "passive"))
      (node (ref "X6") (pin "2@1") (pinfunction "2_2@1") (pintype "passive"))
      (node (ref "X6") (pin "2@2") (pinfunction "2_2@2") (pintype "passive"))
      (node (ref "X7") (pin "3") (pinfunction "3_3") (pintype "passive"))
      (node (ref "X7") (pin "5") (pinfunction "5_5") (pintype "passive"))
      (node (ref "X7") (pin "SH1") (pinfunction "PE1_SH1") (pintype "power_in"))
      (node (ref "X7") (pin "SH2") (pinfunction "PE2_SH2") (pintype "power_in"))
      (node (ref "X7") (pin "SH3") (pinfunction "PE3_SH3") (pintype "power_in"))
    )
    (net (code "134") (name "Net-(C7-Pad+)") (class "Default")
      (node (ref "C7") (pin "+") (pinfunction "+_+") (pintype "passive"))
      (node (ref "R28") (pin "2") (pinfunction "2_2") (pintype "passive"))
      (node (ref "R29") (pin "1") (pinfunction "1_1") (pintype "passive"))
      (node (ref "R30") (pin "1") (pinfunction "1_1") (pintype "passive"))
      (node (ref "R31") (pin "2") (pinfunction "2_2") (pintype "passive"))
      (node (ref "R32") (pin "1") (pinfunction "1_1") (pintype "passive"))
    )
    (net (code "135") (name "Net-(C8-Pad+)") (class "Default")
      (node (ref "C8") (pin "+") (pinfunction "+_+") (pintype "passive"))
      (node (ref "R33") (pin "2") (pinfunction "2_2") (pintype "passive"))
      (node (ref "R34") (pin "1") (pinfunction "1_1") (pintype "passive"))
      (node (ref "R35") (pin "1") (pinfunction "1_1") (pintype "passive"))
      (node (ref "R36") (pin "2") (pinfunction "2_2") (pintype "passive"))
      (node (ref "R37") (pin "1") (pinfunction "1_1") (pintype "passive"))
    )
    (net (code "136") (name "Net-(C22-Pad+)") (class "Default")
      (node (ref "C22") (pin "+") (pinfunction "+_+") (pintype "passive"))
      (node (ref "C23") (pin "1") (pinfunction "1_1") (pintype "passive"))
      (node (ref "L1") (pin "2") (pinfunction "2_2") (pintype "passive"))
      (node (ref "T1") (pin "C") (pinfunction "C_C") (pintype "passive"))
      (node (ref "T2") (pin "C") (pinfunction "C_C") (pintype "passive"))
      (node (ref "T3") (pin "C") (pinfunction "C_C") (pintype "passive"))
      (node (ref "T4") (pin "C") (pinfunction "C_C") (pintype "passive"))
    )
    (net (code "137") (name "Net-(C24-Pad1)") (class "Default")
      (node (ref "C24") (pin "1") (pinfunction "1_1") (pintype "passive"))
      (node (ref "R63") (pin "S") (pinfunction "S_S") (pintype "passive"))
    )
    (net (code "138") (name "Net-(C24-Pad2)") (class "Default")
      (node (ref "C24") (pin "2") (pinfunction "2_2") (pintype "passive"))
      (node (ref "IC22") (pin "4") (pinfunction "4_4") (pintype "passive"))
    )
    (net (code "139") (name "Net-(C25-Pad1)") (class "Default")
      (node (ref "C25") (pin "1") (pinfunction "1_1") (pintype "passive"))
      (node (ref "R62") (pin "S") (pinfunction "S_S") (pintype "passive"))
    )
    (net (code "140") (name "Net-(C25-Pad2)") (class "Default")
      (node (ref "C25") (pin "2") (pinfunction "2_2") (pintype "passive"))
      (node (ref "IC22") (pin "3") (pinfunction "3_3") (pintype "passive"))
    )
    (net (code "141") (name "Net-(C26-Pad1)") (class "Default")
      (node (ref "C26") (pin "1") (pinfunction "1_1") (pintype "passive"))
      (node (ref "R61") (pin "S") (pinfunction "S_S") (pintype "passive"))
    )
    (net (code "142") (name "Net-(C26-Pad2)") (class "Default")
      (node (ref "C26") (pin "2") (pinfunction "2_2") (pintype "passive"))
      (node (ref "IC22") (pin "2") (pinfunction "2_2") (pintype "passive"))
    )
    (net (code "143") (name "Net-(C31-Pad+)") (class "Default")
      (node (ref "C31") (pin "+") (pinfunction "+_+") (pintype "passive"))
      (node (ref "R70") (pin "1") (pinfunction "1_1") (pintype "passive"))
    )
    (net (code "144") (name "Net-(C31-Pad-)") (class "Default")
      (node (ref "C31") (pin "-") (pinfunction "-_-") (pintype "passive"))
      (node (ref "X7") (pin "8") (pinfunction "8_8") (pintype "passive"))
    )
    (net (code "145") (name "Net-(C32-Pad+)") (class "Default")
      (node (ref "C32") (pin "+") (pinfunction "+_+") (pintype "passive"))
      (node (ref "R69") (pin "1") (pinfunction "1_1") (pintype "passive"))
    )
    (net (code "146") (name "Net-(C32-Pad-)") (class "Default")
      (node (ref "C32") (pin "-") (pinfunction "-_-") (pintype "passive"))
      (node (ref "X7") (pin "6") (pinfunction "6_6") (pintype "passive"))
    )
    (net (code "147") (name "Net-(C33-Pad+)") (class "Default")
      (node (ref "C33") (pin "+") (pinfunction "+_+") (pintype "passive"))
      (node (ref "R68") (pin "1") (pinfunction "1_1") (pintype "passive"))
    )
    (net (code "148") (name "Net-(C33-Pad-)") (class "Default")
      (node (ref "C33") (pin "-") (pinfunction "-_-") (pintype "passive"))
      (node (ref "X6") (pin "1") (pinfunction "1_1") (pintype "passive"))
    )
    (net (code "149") (name "Net-(C34-Pad1)") (class "Default")
      (node (ref "C34") (pin "1") (pinfunction "1_1") (pintype "passive"))
      (node (ref "IC22") (pin "13") (pinfunction "13_13") (pintype "passive"))
      (node (ref "R71") (pin "2") (pinfunction "2_2") (pintype "passive"))
    )
    (net (code "150") (name "Net-(C35-Pad+)") (class "Default")
      (node (ref "C35") (pin "+") (pinfunction "+_+") (pintype "passive"))
      (node (ref "IC22") (pin "14") (pinfunction "14_14") (pintype "passive"))
    )
    (net (code "151") (name "Net-(C36-Pad1)") (class "Default")
      (node (ref "C36") (pin "1") (pinfunction "1_1") (pintype "passive"))
      (node (ref "IC22") (pin "9") (pinfunction "9_9") (pintype "passive"))
    )
    (net (code "152") (name "Net-(D1-PadA)") (class "Default")
      (node (ref "D1") (pin "A") (pinfunction "A_A") (pintype "passive"))
      (node (ref "R43") (pin "1") (pinfunction "1_1") (pintype "passive"))
      (node (ref "R48") (pin "2") (pinfunction "2_2") (pintype "passive"))
      (node (ref "T1") (pin "B") (pinfunction "B_B") (pintype "passive"))
    )
    (net (code "153") (name "Net-(D1-PadC)") (class "Default")
      (node (ref "D1") (pin "C") (pinfunction "C_C") (pintype "passive"))
      (node (ref "R47") (pin "2") (pinfunction "2_2") (pintype "passive"))
    )
    (net (code "154") (name "Net-(D2-PadA)") (class "Default")
      (node (ref "D2") (pin "A") (pinfunction "A_A") (pintype "passive"))
      (node (ref "R44") (pin "1") (pinfunction "1_1") (pintype "passive"))
      (node (ref "R51") (pin "2") (pinfunction "2_2") (pintype "passive"))
      (node (ref "T2") (pin "B") (pinfunction "B_B") (pintype "passive"))
    )
    (net (code "155") (name "Net-(D2-PadC)") (class "Default")
      (node (ref "D2") (pin "C") (pinfunction "C_C") (pintype "passive"))
      (node (ref "R50") (pin "2") (pinfunction "2_2") (pintype "passive"))
    )
    (net (code "156") (name "Net-(D3-PadA)") (class "Default")
      (node (ref "D3") (pin "A") (pinfunction "A_A") (pintype "passive"))
      (node (ref "R45") (pin "1") (pinfunction "1_1") (pintype "passive"))
      (node (ref "R54") (pin "2") (pinfunction "2_2") (pintype "passive"))
      (node (ref "T3") (pin "B") (pinfunction "B_B") (pintype "passive"))
    )
    (net (code "157") (name "Net-(D3-PadC)") (class "Default")
      (node (ref "D3") (pin "C") (pinfunction "C_C") (pintype "passive"))
      (node (ref "R53") (pin "2") (pinfunction "2_2") (pintype "passive"))
    )
    (net (code "158") (name "Net-(D4-PadA)") (class "Default")
      (node (ref "D4") (pin "A") (pinfunction "A_A") (pintype "passive"))
      (node (ref "KA8") (pin "1") (pinfunction "1_1") (pintype "passive"))
    )
    (net (code "159") (name "Net-(D5-PadA)") (class "Default")
      (node (ref "D5") (pin "A") (pinfunction "A_A") (pintype "passive"))
      (node (ref "KA9") (pin "1") (pinfunction "1_1") (pintype "passive"))
    )
    (net (code "160") (name "Net-(D6-PadA)") (class "Default")
      (node (ref "D6") (pin "A") (pinfunction "A_A") (pintype "passive"))
      (node (ref "KA10") (pin "1") (pinfunction "1_1") (pintype "passive"))
    )
    (net (code "161") (name "Net-(D7-PadA)") (class "Default")
      (node (ref "D7") (pin "A") (pinfunction "A_A") (pintype "passive"))
      (node (ref "KA11") (pin "1") (pinfunction "1_1") (pintype "passive"))
    )
    (net (code "162") (name "Net-(D8-PadA)") (class "Default")
      (node (ref "D8") (pin "A") (pinfunction "A_A") (pintype "passive"))
      (node (ref "KA12") (pin "1") (pinfunction "1_1") (pintype "passive"))
    )
    (net (code "163") (name "Net-(D9-PadA)") (class "Default")
      (node (ref "D9") (pin "A") (pinfunction "A_A") (pintype "passive"))
      (node (ref "KA13") (pin "1") (pinfunction "1_1") (pintype "passive"))
    )
    (net (code "164") (name "Net-(D10-PadA)") (class "Default")
      (node (ref "D10") (pin "A") (pinfunction "A_A") (pintype "passive"))
      (node (ref "KA14") (pin "1") (pinfunction "1_1") (pintype "passive"))
    )
    (net (code "165") (name "Net-(D11-PadA)") (class "Default")
      (node (ref "D11") (pin "A") (pinfunction "A_A") (pintype "passive"))
      (node (ref "KA15") (pin "1") (pinfunction "1_1") (pintype "passive"))
    )
    (net (code "166") (name "Net-(DD1E-O)") (class "Default")
      (node (ref "DD1") (pin "10") (pinfunction "O_10") (pintype "output"))
      (node (ref "DD8") (pin "10") (pinfunction "I1_10") (pintype "input"))
      (node (ref "DD8") (pin "12") (pinfunction "I0_12") (pintype "input"))
    )
    (net (code "167") (name "Net-(DD1F-I)") (class "Default")
      (node (ref "DD1") (pin "13") (pinfunction "I_13") (pintype "input"))
      (node (ref "DD8") (pin "8") (pinfunction "O_8") (pintype "output"))
    )
    (net (code "168") (name "Net-(DD4-Pad21)") (class "Default")
      (node (ref "DD4") (pin "21") (pinfunction "21_21") (pintype "passive"))
      (node (ref "R25") (pin "1") (pinfunction "1_1") (pintype "passive"))
    )
    (net (code "169") (name "Net-(DD5A-~{CAS})") (class "Default")
      (node (ref "DD5") (pin "16") (pinfunction "~{CAS}_16") (pintype "input"))
      (node (ref "DD6") (pin "16") (pinfunction "~{CAS}_16") (pintype "input"))
      (node (ref "R24") (pin "1") (pinfunction "1_1") (pintype "passive"))
    )
    (net (code "170") (name "Net-(DD5A-~{RAS})") (class "Default")
      (node (ref "C4") (pin "2") (pinfunction "2_2") (pintype "passive"))
      (node (ref "DD5") (pin "5") (pinfunction "~{RAS}_5") (pintype "input"))
      (node (ref "DD6") (pin "5") (pinfunction "~{RAS}_5") (pintype "input"))
      (node (ref "R23") (pin "1") (pinfunction "1_1") (pintype "passive"))
    )
    (net (code "171") (name "Net-(DD7A-Q4)") (class "Default")
      (node (ref "DD7") (pin "15") (pinfunction "Q4_15") (pintype "output"))
      (node (ref "DD8") (pin "1") (pinfunction "I0_1") (pintype "input"))
    )
    (net (code "172") (name "Net-(DD7A-~{Q4})") (class "Default")
      (node (ref "DD7") (pin "14") (pinfunction "~{Q4}_14") (pintype "output"))
      (node (ref "DD8") (pin "5") (pinfunction "I1_5") (pintype "input"))
    )
    (net (code "173") (name "Net-(IC1A-I0)") (class "Default")
      (node (ref "C2") (pin "+") (pinfunction "+_+") (pintype "passive"))
      (node (ref "D12") (pin "A") (pinfunction "A_A") (pintype "passive"))
      (node (ref "IC1") (pin "1") (pinfunction "I0_1") (pintype "input"))
      (node (ref "IC1") (pin "2") (pinfunction "I1_2") (pintype "input"))
      (node (ref "JP4") (pin "1") (pinfunction "1_1") (pintype "passive"))
      (node (ref "R3") (pin "1") (pinfunction "1_1") (pintype "passive"))
      (node (ref "S1") (pin "1") (pinfunction "S_1") (pintype "passive"))
      (node (ref "S1") (pin "2") (pinfunction "S1_2") (pintype "passive"))
    )
    (net (code "174") (name "Net-(IC1C-I0)") (class "Default")
      (node (ref "IC1") (pin "10") (pinfunction "I1_10") (pintype "input"))
      (node (ref "IC1") (pin "9") (pinfunction "I0_9") (pintype "input"))
      (node (ref "Q1") (pin "1") (pinfunction "1_1") (pintype "passive"))
      (node (ref "R1") (pin "1") (pinfunction "1_1") (pintype "passive"))
    )
    (net (code "175") (name "Net-(IC1C-O)") (class "Default")
      (node (ref "C1") (pin "1") (pinfunction "1_1") (pintype "passive"))
      (node (ref "IC1") (pin "8") (pinfunction "O_8") (pintype "output"))
      (node (ref "R1") (pin "2") (pinfunction "2_2") (pintype "passive"))
    )
    (net (code "176") (name "Net-(IC1D-I0)") (class "Default")
      (node (ref "C1") (pin "2") (pinfunction "2_2") (pintype "passive"))
      (node (ref "IC1") (pin "12") (pinfunction "I0_12") (pintype "input"))
      (node (ref "IC1") (pin "13") (pinfunction "I1_13") (pintype "input"))
      (node (ref "R2") (pin "1") (pinfunction "1_1") (pintype "passive"))
    )
    (net (code "177") (name "Net-(IC6A-DIR)") (class "Default")
      (node (ref "IC6") (pin "1") (pinfunction "DIR_1") (pintype "input"))
      (node (ref "JP1A1") (pin "2") (pinfunction "2_2") (pintype "passive"))
      (node (ref "JPORT") (pin "2") (pinfunction "2_2") (pintype "passive"))
    )
    (net (code "178") (name "Net-(IC12-A8)") (class "Default")
      (node (ref "IC12") (pin "25") (pinfunction "A8_25") (pintype "bidirectional"))
      (node (ref "IC12") (pin "28") (pinfunction "BC2_28") (pintype "bidirectional"))
      (node (ref "R38") (pin "2") (pinfunction "2_2") (pintype "passive"))
    )
    (net (code "179") (name "Net-(IC12-BC1)") (class "Default")
      (node (ref "IC12") (pin "29") (pinfunction "BC1_29") (pintype "bidirectional"))
      (node (ref "IC14") (pin "8") (pinfunction "O_8") (pintype "output"))
    )
    (net (code "180") (name "Net-(IC12-BDIR)") (class "Default")
      (node (ref "IC12") (pin "27") (pinfunction "BDIR_27") (pintype "bidirectional"))
      (node (ref "IC14") (pin "11") (pinfunction "O_11") (pintype "output"))
    )
    (net (code "181") (name "Net-(IC13A-Y4)") (class "Default")
      (node (ref "IC13") (pin "11") (pinfunction "Y4_11") (pintype "output"))
      (node (ref "IC14") (pin "13") (pinfunction "I1_13") (pintype "input"))
    )
    (net (code "182") (name "Net-(IC13A-Y5)") (class "Default")
      (node (ref "IC13") (pin "10") (pinfunction "Y5_10") (pintype "output"))
      (node (ref "IC5") (pin "5") (pinfunction "I1_5") (pintype "input"))
    )
    (net (code "183") (name "Net-(IC13A-Y6)") (class "Default")
      (node (ref "IC13") (pin "9") (pinfunction "Y6_9") (pintype "output"))
      (node (ref "IC14") (pin "10") (pinfunction "I1_10") (pintype "input"))
      (node (ref "IC14") (pin "12") (pinfunction "I0_12") (pintype "input"))
    )
    (net (code "184") (name "Net-(IC13A-Y7)") (class "Default")
      (node (ref "IC13") (pin "7") (pinfunction "Y7_7") (pintype "output"))
      (node (ref "IC14") (pin "9") (pinfunction "I0_9") (pintype "input"))
      (node (ref "IC5") (pin "4") (pinfunction "I0_4") (pintype "input"))
    )
    (net (code "185") (name "Net-(IC14A-I0)") (class "Default")
      (node (ref "IC14") (pin "1") (pinfunction "I0_1") (pintype "input"))
      (node (ref "IC14") (pin "2") (pinfunction "I1_2") (pintype "input"))
      (node (ref "Q2") (pin "1") (pinfunction "1_1") (pintype "passive"))
      (node (ref "R27") (pin "1") (pinfunction "1_1") (pintype "passive"))
    )
    (net (code "186") (name "Net-(IC14A-O)") (class "Default")
      (node (ref "C6") (pin "1") (pinfunction "1_1") (pintype "passive"))
      (node (ref "IC14") (pin "3") (pinfunction "O_3") (pintype "output"))
      (node (ref "R27") (pin "2") (pinfunction "2_2") (pintype "passive"))
    )
    (net (code "187") (name "Net-(IC14B-I0)") (class "Default")
      (node (ref "C6") (pin "2") (pinfunction "2_2") (pintype "passive"))
      (node (ref "IC14") (pin "4") (pinfunction "I0_4") (pintype "input"))
      (node (ref "IC14") (pin "5") (pinfunction "I1_5") (pintype "input"))
      (node (ref "R26") (pin "1") (pinfunction "1_1") (pintype "passive"))
    )
    (net (code "188") (name "Net-(IC14B-O)") (class "Default")
      (node (ref "IC14") (pin "6") (pinfunction "O_6") (pintype "output"))
      (node (ref "IC16") (pin "1") (pinfunction "CKB_1") (pintype "input"))
      (node (ref "Q2") (pin "2") (pinfunction "2_2") (pintype "passive"))
      (node (ref "R26") (pin "2") (pinfunction "2_2") (pintype "passive"))
    )
    (net (code "189") (name "Net-(IC17A-QA)") (class "Default")
      (node (ref "IC17") (pin "15") (pinfunction "QA_15") (pintype "tri_state"))
      (node (ref "PKD2") (pin "1") (pinfunction "1_1") (pintype "passive"))
    )
    (net (code "190") (name "Net-(IC17A-QB)") (class "Default")
      (node (ref "IC17") (pin "1") (pinfunction "QB_1") (pintype "tri_state"))
      (node (ref "PKD4") (pin "1") (pinfunction "1_1") (pintype "passive"))
    )
    (net (code "191") (name "Net-(IC17A-QC)") (class "Default")
      (node (ref "IC17") (pin "2") (pinfunction "QC_2") (pintype "tri_state"))
      (node (ref "PKD1") (pin "1") (pinfunction "1_1") (pintype "passive"))
    )
    (net (code "192") (name "Net-(IC17A-QD)") (class "Default")
      (node (ref "IC17") (pin "3") (pinfunction "QD_3") (pintype "tri_state"))
      (node (ref "PKD3") (pin "1") (pinfunction "1_1") (pintype "passive"))
    )
    (net (code "193") (name "Net-(IC17A-QG)") (class "Default")
      (node (ref "IC17") (pin "6") (pinfunction "QG_6") (pintype "tri_state"))
      (node (ref "PKD0") (pin "1") (pinfunction "1_1") (pintype "passive"))
    )
    (net (code "194") (name "Net-(IC17A-QH)") (class "Default")
      (node (ref "IC17") (pin "7") (pinfunction "QH_7") (pintype "tri_state"))
      (node (ref "PKD6") (pin "1") (pinfunction "1_1") (pintype "passive"))
    )
    (net (code "195") (name "Net-(IC17A-RCK)") (class "Default")
      (node (ref "IC17") (pin "12") (pinfunction "RCK_12") (pintype "input"))
      (node (ref "IC18") (pin "12") (pinfunction "RCK_12") (pintype "input"))
      (node (ref "IC19") (pin "11") (pinfunction "QD_11") (pintype "output"))
      (node (ref "IC19") (pin "2") (pinfunction "R0(1)_2") (pintype "input"))
      (node (ref "X4") (pin "12") (pinfunction "12_12") (pintype "passive"))
      (node (ref "X5") (pin "12") (pinfunction "12_12") (pintype "passive"))
    )
    (net (code "196") (name "Net-(IC17A-SCK)") (class "Default")
      (node (ref "IC17") (pin "11") (pinfunction "SCK_11") (pintype "input"))
      (node (ref "IC18") (pin "11") (pinfunction "SCK_11") (pintype "input"))
      (node (ref "IC19") (pin "14") (pinfunction "CKA_14") (pintype "input"))
      (node (ref "IC20") (pin "12") (pinfunction "O_12") (pintype "output"))
      (node (ref "X4") (pin "9") (pinfunction "9_9") (pintype "passive"))
      (node (ref "X5") (pin "9") (pinfunction "9_9") (pintype "passive"))
    )
    (net (code "197") (name "Net-(IC17A-SCL)") (class "Default")
      (node (ref "IC17") (pin "10") (pinfunction "SCL_10") (pintype "input"))
      (node (ref "IC18") (pin "10") (pinfunction "SCL_10") (pintype "input"))
      (node (ref "R41") (pin "1") (pinfunction "1_1") (pintype "passive"))
    )
    (net (code "198") (name "Net-(IC17A-SER)") (class "Default")
      (node (ref "IC17") (pin "14") (pinfunction "SER_14") (pintype "input"))
      (node (ref "R40") (pin "2") (pinfunction "2_2") (pintype "passive"))
      (node (ref "X5") (pin "8") (pinfunction "8_8") (pintype "passive"))
    )
    (net (code "199") (name "Net-(IC18A-QF)") (class "Default")
      (node (ref "IC18") (pin "5") (pinfunction "QF_5") (pintype "tri_state"))
      (node (ref "IC20") (pin "1") (pinfunction "I_1") (pintype "input"))
    )
    (net (code "200") (name "Net-(IC18A-QH)") (class "Default")
      (node (ref "IC18") (pin "7") (pinfunction "QH_7") (pintype "tri_state"))
      (node (ref "IC20") (pin "3") (pinfunction "I_3") (pintype "input"))
    )
    (net (code "201") (name "Net-(IC18A-SER)") (class "Default")
      (node (ref "IC18") (pin "14") (pinfunction "SER_14") (pintype "input"))
      (node (ref "R42") (pin "1") (pinfunction "1_1") (pintype "passive"))
      (node (ref "X4") (pin "8") (pinfunction "8_8") (pintype "passive"))
    )
    (net (code "202") (name "Net-(IC19A-CKB)") (class "Default")
      (node (ref "IC19") (pin "1") (pinfunction "CKB_1") (pintype "input"))
      (node (ref "IC19") (pin "12") (pinfunction "QA_12") (pintype "output"))
    )
    (net (code "203") (name "Net-(IC19A-QB)") (class "Default")
      (node (ref "IC19") (pin "3") (pinfunction "R0(2)_3") (pintype "input"))
      (node (ref "IC19") (pin "9") (pinfunction "QB_9") (pintype "output"))
    )
    (net (code "204") (name "Net-(IC20C-I)") (class "Default")
      (node (ref "C39") (pin "1") (pinfunction "1_1") (pintype "passive"))
      (node (ref "IC20") (pin "5") (pinfunction "I_5") (pintype "input"))
      (node (ref "R39") (pin "1") (pinfunction "1_1") (pintype "passive"))
    )
    (net (code "205") (name "Net-(IC20C-O)") (class "Default")
      (node (ref "IC20") (pin "6") (pinfunction "O_6") (pintype "output"))
      (node (ref "IC20") (pin "9") (pinfunction "I_9") (pintype "input"))
    )
    (net (code "206") (name "Net-(IC20D-O)") (class "Default")
      (node (ref "C39") (pin "2") (pinfunction "2_2") (pintype "passive"))
      (node (ref "IC20") (pin "11") (pinfunction "I_11") (pintype "input"))
      (node (ref "IC20") (pin "8") (pinfunction "O_8") (pintype "output"))
    )
    (net (code "207") (name "Net-(IC20E-O)") (class "Default")
      (node (ref "IC20") (pin "10") (pinfunction "O_10") (pintype "output"))
      (node (ref "IC20") (pin "13") (pinfunction "I_13") (pintype "input"))
      (node (ref "R39") (pin "2") (pinfunction "2_2") (pintype "passive"))
    )
    (net (code "208") (name "Net-(IC21A-Y)") (class "Default")
      (node (ref "IC21") (pin "5") (pinfunction "Y_5") (pintype "tri_state"))
      (node (ref "JP3") (pin "9") (pinfunction "9_9") (pintype "passive"))
      (node (ref "R47") (pin "1") (pinfunction "1_1") (pintype "passive"))
      (node (ref "R50") (pin "1") (pinfunction "1_1") (pintype "passive"))
      (node (ref "R53") (pin "1") (pinfunction "1_1") (pintype "passive"))
    )
    (net (code "209") (name "Net-(IC22-Pad6)") (class "Default")
      (node (ref "IC22") (pin "6") (pinfunction "6_6") (pintype "passive"))
      (node (ref "R65") (pin "2") (pinfunction "2_2") (pintype "passive"))
    )
    (net (code "210") (name "Net-(IC22-Pad10)") (class "Default")
      (node (ref "IC22") (pin "10") (pinfunction "10_10") (pintype "passive"))
      (node (ref "R60") (pin "S") (pinfunction "S_S") (pintype "passive"))
    )
    (net (code "211") (name "Net-(IC22-Pad15)") (class "Default")
      (node (ref "IC22") (pin "15") (pinfunction "15_15") (pintype "passive"))
      (node (ref "R70") (pin "2") (pinfunction "2_2") (pintype "passive"))
    )
    (net (code "212") (name "Net-(IC22-Pad16)") (class "Default")
      (node (ref "IC22") (pin "16") (pinfunction "16_16") (pintype "passive"))
      (node (ref "R69") (pin "2") (pinfunction "2_2") (pintype "passive"))
    )
    (net (code "213") (name "Net-(IC22-Pad17)") (class "Default")
      (node (ref "IC22") (pin "17") (pinfunction "17_17") (pintype "passive"))
      (node (ref "R67") (pin "2") (pinfunction "2_2") (pintype "passive"))
    )
    (net (code "214") (name "Net-(IC22-Pad18)") (class "Default")
      (node (ref "IC22") (pin "18") (pinfunction "18_18") (pintype "passive"))
      (node (ref "R66") (pin "1") (pinfunction "1_1") (pintype "passive"))
    )
    (net (code "215") (name "Net-(IC22-Pad20)") (class "Default")
      (node (ref "IC22") (pin "20") (pinfunction "20_20") (pintype "passive"))
      (node (ref "R68") (pin "2") (pinfunction "2_2") (pintype "passive"))
    )
    (net (code "216") (name "Net-(IC23A-I)") (class "Default")
      (node (ref "C38") (pin "2") (pinfunction "2_2") (pintype "passive"))
      (node (ref "IC23") (pin "1") (pinfunction "I_1") (pintype "input"))
      (node (ref "Q3") (pin "1") (pinfunction "1_1") (pintype "passive"))
      (node (ref "R64") (pin "2") (pinfunction "2_2") (pintype "passive"))
    )
    (net (code "217") (name "Net-(IC23A-O)") (class "Default")
      (node (ref "C37") (pin "2") (pinfunction "2_2") (pintype "passive"))
      (node (ref "IC23") (pin "2") (pinfunction "O_2") (pintype "output"))
      (node (ref "IC23") (pin "3") (pinfunction "I_3") (pintype "input"))
      (node (ref "Q3") (pin "2") (pinfunction "2_2") (pintype "passive"))
      (node (ref "R64") (pin "1") (pinfunction "1_1") (pintype "passive"))
    )
    (net (code "218") (name "Net-(IC23B-O)") (class "Default")
      (node (ref "IC23") (pin "4") (pinfunction "O_4") (pintype "output"))
      (node (ref "R65") (pin "1") (pinfunction "1_1") (pintype "passive"))
    )
    (net (code "219") (name "Net-(R46-Pad1)") (class "Default")
      (node (ref "R46") (pin "1") (pinfunction "1_1") (pintype "passive"))
      (node (ref "R56") (pin "2") (pinfunction "2_2") (pintype "passive"))
      (node (ref "T4") (pin "B") (pinfunction "B_B") (pintype "passive"))
    )
    (net (code "220") (name "Net-(X3B-F)") (class "Default")
      (node (ref "R49") (pin "2") (pinfunction "2_2") (pintype "passive"))
      (node (ref "R61") (pin "E") (pinfunction "E_E") (pintype "passive"))
      (node (ref "T1") (pin "E") (pinfunction "E_E") (pintype "passive"))
      (node (ref "X3") (pin "2") (pinfunction "F_2") (pintype "passive"))
    )
    (net (code "221") (name "Net-(X3C-F)") (class "Default")
      (node (ref "R52") (pin "2") (pinfunction "2_2") (pintype "passive"))
      (node (ref "R62") (pin "E") (pinfunction "E_E") (pintype "passive"))
      (node (ref "T2") (pin "E") (pinfunction "E_E") (pintype "passive"))
      (node (ref "X3") (pin "3") (pinfunction "F_3") (pintype "passive"))
    )
    (net (code "222") (name "Net-(X3D-F)") (class "Default")
      (node (ref "R55") (pin "2") (pinfunction "2_2") (pintype "passive"))
      (node (ref "R63") (pin "E") (pinfunction "E_E") (pintype "passive"))
      (node (ref "T3") (pin "E") (pinfunction "E_E") (pintype "passive"))
      (node (ref "X3") (pin "4") (pinfunction "F_4") (pintype "passive"))
    )
    (net (code "223") (name "Net-(X3E-F)") (class "Default")
      (node (ref "R57") (pin "2") (pinfunction "2_2") (pintype "passive"))
      (node (ref "R60") (pin "E") (pinfunction "E_E") (pintype "passive"))
      (node (ref "T4") (pin "E") (pinfunction "E_E") (pintype "passive"))
      (node (ref "X3") (pin "5") (pinfunction "F_5") (pintype "passive"))
    )
    (net (code "224") (name "Net-(X3I-F)") (class "Default")
      (node (ref "R58") (pin "1") (pinfunction "1_1") (pintype "passive"))
      (node (ref "X3") (pin "9") (pinfunction "F_9") (pintype "passive"))
    )
    (net (code "225") (name "unconnected-(CN1-Pad3)") (class "Default")
      (node (ref "CN1") (pin "3") (pinfunction "3_3") (pintype "bidirectional"))
    )
    (net (code "226") (name "unconnected-(CN1-Pad4)") (class "Default")
      (node (ref "CN1") (pin "4") (pinfunction "4_4") (pintype "bidirectional"))
    )
    (net (code "227") (name "unconnected-(CN1-Pad5)") (class "Default")
      (node (ref "CN1") (pin "5") (pinfunction "5_5") (pintype "bidirectional"))
    )
    (net (code "228") (name "unconnected-(CN1-Pad6)") (class "Default")
      (node (ref "CN1") (pin "6") (pinfunction "6_6") (pintype "bidirectional"))
    )
    (net (code "229") (name "unconnected-(CN1-Pad7)") (class "Default")
      (node (ref "CN1") (pin "7") (pinfunction "7_7") (pintype "bidirectional"))
    )
    (net (code "230") (name "unconnected-(CN1-Pad8)") (class "Default")
      (node (ref "CN1") (pin "8") (pinfunction "8_8") (pintype "bidirectional"))
    )
    (net (code "231") (name "unconnected-(CN1-Pad9)") (class "Default")
      (node (ref "CN1") (pin "9") (pinfunction "9_9") (pintype "bidirectional"))
    )
    (net (code "232") (name "unconnected-(CN1-Pad10)") (class "Default")
      (node (ref "CN1") (pin "10") (pinfunction "10_10") (pintype "bidirectional"))
    )
    (net (code "233") (name "unconnected-(CN1-Pad11)") (class "Default")
      (node (ref "CN1") (pin "11") (pinfunction "11_11") (pintype "bidirectional"))
    )
    (net (code "234") (name "unconnected-(CN1-Pad12)") (class "Default")
      (node (ref "CN1") (pin "12") (pinfunction "12_12") (pintype "bidirectional"))
    )
    (net (code "235") (name "unconnected-(CN1-Pad13)") (class "Default")
      (node (ref "CN1") (pin "13") (pinfunction "13_13") (pintype "bidirectional"))
    )
    (net (code "236") (name "unconnected-(CN1-Pad14)") (class "Default")
      (node (ref "CN1") (pin "14") (pinfunction "14_14") (pintype "bidirectional"))
    )
    (net (code "237") (name "unconnected-(CN1-Pad15)") (class "Default")
      (node (ref "CN1") (pin "15") (pinfunction "15_15") (pintype "bidirectional"))
    )
    (net (code "238") (name "unconnected-(CN1-Pad16)") (class "Default")
      (node (ref "CN1") (pin "16") (pinfunction "16_16") (pintype "bidirectional"))
    )
    (net (code "239") (name "unconnected-(CN1-Pad17)") (class "Default")
      (node (ref "CN1") (pin "17") (pinfunction "17_17") (pintype "bidirectional"))
    )
    (net (code "240") (name "unconnected-(CN1-Pad18)") (class "Default")
      (node (ref "CN1") (pin "18") (pinfunction "18_18") (pintype "bidirectional"))
    )
    (net (code "241") (name "unconnected-(CN1-Pad19)") (class "Default")
      (node (ref "CN1") (pin "19") (pinfunction "19_19") (pintype "bidirectional"))
    )
    (net (code "242") (name "unconnected-(CN1-Pad20)") (class "Default")
      (node (ref "CN1") (pin "20") (pinfunction "20_20") (pintype "bidirectional"))
    )
    (net (code "243") (name "unconnected-(CN1-Pad21)") (class "Default")
      (node (ref "CN1") (pin "21") (pinfunction "21_21") (pintype "bidirectional"))
    )
    (net (code "244") (name "unconnected-(CN1-Pad22)") (class "Default")
      (node (ref "CN1") (pin "22") (pinfunction "22_22") (pintype "bidirectional"))
    )
    (net (code "245") (name "unconnected-(CN1-Pad23)") (class "Default")
      (node (ref "CN1") (pin "23") (pinfunction "23_23") (pintype "bidirectional"))
    )
    (net (code "246") (name "unconnected-(CN1-Pad24)") (class "Default")
      (node (ref "CN1") (pin "24") (pinfunction "24_24") (pintype "bidirectional"))
    )
    (net (code "247") (name "unconnected-(CN1-Pad25)") (class "Default")
      (node (ref "CN1") (pin "25") (pinfunction "25_25") (pintype "bidirectional"))
    )
    (net (code "248") (name "unconnected-(CN1-Pad26)") (class "Default")
      (node (ref "CN1") (pin "26") (pinfunction "26_26") (pintype "bidirectional"))
    )
    (net (code "249") (name "unconnected-(CN1-Pad27)") (class "Default")
      (node (ref "CN1") (pin "27") (pinfunction "27_27") (pintype "bidirectional"))
    )
    (net (code "250") (name "unconnected-(CN1-Pad28)") (class "Default")
      (node (ref "CN1") (pin "28") (pinfunction "28_28") (pintype "bidirectional"))
    )
    (net (code "251") (name "unconnected-(CN1-Pad29)") (class "Default")
      (node (ref "CN1") (pin "29") (pinfunction "29_29") (pintype "bidirectional"))
    )
    (net (code "252") (name "unconnected-(CN1-Pad30)") (class "Default")
      (node (ref "CN1") (pin "30") (pinfunction "30_30") (pintype "bidirectional"))
    )
    (net (code "253") (name "unconnected-(CN1-Pad31)") (class "Default")
      (node (ref "CN1") (pin "31") (pinfunction "31_31") (pintype "bidirectional"))
    )
    (net (code "254") (name "unconnected-(CN1-Pad32)") (class "Default")
      (node (ref "CN1") (pin "32") (pinfunction "32_32") (pintype "bidirectional"))
    )
    (net (code "255") (name "unconnected-(CN1-Pad33)") (class "Default")
      (node (ref "CN1") (pin "33") (pinfunction "33_33") (pintype "bidirectional"))
    )
    (net (code "256") (name "unconnected-(CN1-Pad34)") (class "Default")
      (node (ref "CN1") (pin "34") (pinfunction "34_34") (pintype "bidirectional"))
    )
    (net (code "257") (name "unconnected-(CN1-Pad35)") (class "Default")
      (node (ref "CN1") (pin "35") (pinfunction "35_35") (pintype "bidirectional"))
    )
    (net (code "258") (name "unconnected-(CN1-Pad36)") (class "Default")
      (node (ref "CN1") (pin "36") (pinfunction "36_36") (pintype "bidirectional"))
    )
    (net (code "259") (name "unconnected-(CN1-Pad37)") (class "Default")
      (node (ref "CN1") (pin "37") (pinfunction "37_37") (pintype "bidirectional"))
    )
    (net (code "260") (name "unconnected-(CN1-Pad38)") (class "Default")
      (node (ref "CN1") (pin "38") (pinfunction "38_38") (pintype "bidirectional"))
    )
    (net (code "261") (name "unconnected-(CN1-Pad39)") (class "Default")
      (node (ref "CN1") (pin "39") (pinfunction "39_39") (pintype "bidirectional"))
    )
    (net (code "262") (name "unconnected-(CN1-Pad40)") (class "Default")
      (node (ref "CN1") (pin "40") (pinfunction "40_40") (pintype "bidirectional"))
    )
    (net (code "263") (name "unconnected-(CN1-Pad41)") (class "Default")
      (node (ref "CN1") (pin "41") (pinfunction "41_41") (pintype "bidirectional"))
    )
    (net (code "264") (name "unconnected-(CN1-Pad42)") (class "Default")
      (node (ref "CN1") (pin "42") (pinfunction "42_42") (pintype "bidirectional"))
    )
    (net (code "265") (name "unconnected-(CN1-Pad43)") (class "Default")
      (node (ref "CN1") (pin "43") (pinfunction "43_43") (pintype "bidirectional"))
    )
    (net (code "266") (name "unconnected-(CN1-Pad44)") (class "Default")
      (node (ref "CN1") (pin "44") (pinfunction "44_44") (pintype "bidirectional"))
    )
    (net (code "267") (name "unconnected-(CN1-Pad45)") (class "Default")
      (node (ref "CN1") (pin "45") (pinfunction "45_45") (pintype "bidirectional"))
    )
    (net (code "268") (name "unconnected-(CN1-Pad46)") (class "Default")
      (node (ref "CN1") (pin "46") (pinfunction "46_46") (pintype "bidirectional"))
    )
    (net (code "269") (name "unconnected-(DD1A-I-Pad1)") (class "Default")
      (node (ref "DD1") (pin "1") (pinfunction "I_1") (pintype "input"))
    )
    (net (code "270") (name "unconnected-(DD1A-O-Pad2)") (class "Default")
      (node (ref "DD1") (pin "2") (pinfunction "O_2") (pintype "output"))
    )
    (net (code "271") (name "unconnected-(DD1B-I-Pad3)") (class "Default")
      (node (ref "DD1") (pin "3") (pinfunction "I_3") (pintype "input"))
    )
    (net (code "272") (name "unconnected-(DD1B-O-Pad4)") (class "Default")
      (node (ref "DD1") (pin "4") (pinfunction "O_4") (pintype "output"))
    )
    (net (code "273") (name "unconnected-(DD1C-I-Pad5)") (class "Default")
      (node (ref "DD1") (pin "5") (pinfunction "I_5") (pintype "input"))
    )
    (net (code "274") (name "unconnected-(DD1C-O-Pad6)") (class "Default")
      (node (ref "DD1") (pin "6") (pinfunction "O_6") (pintype "output"))
    )
    (net (code "275") (name "unconnected-(DD1D-I-Pad9)") (class "Default")
      (node (ref "DD1") (pin "9") (pinfunction "I_9") (pintype "input"))
    )
    (net (code "276") (name "unconnected-(DD1D-O-Pad8)") (class "Default")
      (node (ref "DD1") (pin "8") (pinfunction "O_8") (pintype "output"))
    )
    (net (code "277") (name "unconnected-(DD2-HALT-Pad18)") (class "Default")
      (node (ref "DD2") (pin "18") (pinfunction "HALT_18") (pintype "output"))
    )
    (net (code "278") (name "unconnected-(DD7A-~{Q1}-Pad3)") (class "Default")
      (node (ref "DD7") (pin "3") (pinfunction "~{Q1}_3") (pintype "output"))
    )
    (net (code "279") (name "unconnected-(DD7A-~{Q2}-Pad6)") (class "Default")
      (node (ref "DD7") (pin "6") (pinfunction "~{Q2}_6") (pintype "output"))
    )
    (net (code "280") (name "unconnected-(DD7A-~{Q3}-Pad11)") (class "Default")
      (node (ref "DD7") (pin "11") (pinfunction "~{Q3}_11") (pintype "output"))
    )
    (net (code "281") (name "unconnected-(H1-MOUNT-PadB3,3)") (class "Default")
      (node (ref "H1") (pin "B3,3") (pinfunction "MOUNT_B3,3") (pintype "passive"))
    )
    (net (code "282") (name "unconnected-(IC5C-I0-Pad9)") (class "Default")
      (node (ref "IC5") (pin "9") (pinfunction "I0_9") (pintype "input"))
    )
    (net (code "283") (name "unconnected-(IC5C-I1-Pad10)") (class "Default")
      (node (ref "IC5") (pin "10") (pinfunction "I1_10") (pintype "input"))
    )
    (net (code "284") (name "unconnected-(IC5C-O-Pad8)") (class "Default")
      (node (ref "IC5") (pin "8") (pinfunction "O_8") (pintype "open_collector"))
    )
    (net (code "285") (name "unconnected-(IC5D-I0-Pad12)") (class "Default")
      (node (ref "IC5") (pin "12") (pinfunction "I0_12") (pintype "input"))
    )
    (net (code "286") (name "unconnected-(IC5D-I1-Pad13)") (class "Default")
      (node (ref "IC5") (pin "13") (pinfunction "I1_13") (pintype "input"))
    )
    (net (code "287") (name "unconnected-(IC5D-O-Pad11)") (class "Default")
      (node (ref "IC5") (pin "11") (pinfunction "O_11") (pintype "open_collector"))
    )
    (net (code "288") (name "unconnected-(IC12-IOA1-Pad20)") (class "Default")
      (node (ref "IC12") (pin "20") (pinfunction "IOA1_20") (pintype "bidirectional"))
    )
    (net (code "289") (name "unconnected-(IC12-IOA2-Pad19)") (class "Default")
      (node (ref "IC12") (pin "19") (pinfunction "IOA2_19") (pintype "bidirectional"))
    )
    (net (code "290") (name "unconnected-(IC12-IOA3-Pad18)") (class "Default")
      (node (ref "IC12") (pin "18") (pinfunction "IOA3_18") (pintype "bidirectional"))
    )
    (net (code "291") (name "unconnected-(IC12-IOA4-Pad17)") (class "Default")
      (node (ref "IC12") (pin "17") (pinfunction "IOA4_17") (pintype "bidirectional"))
    )
    (net (code "292") (name "unconnected-(IC12-IOA5-Pad16)") (class "Default")
      (node (ref "IC12") (pin "16") (pinfunction "IOA5_16") (pintype "bidirectional"))
    )
    (net (code "293") (name "unconnected-(IC12-IOA6-Pad15)") (class "Default")
      (node (ref "IC12") (pin "15") (pinfunction "IOA6_15") (pintype "bidirectional"))
    )
    (net (code "294") (name "unconnected-(IC12-IOA7-Pad14)") (class "Default")
      (node (ref "IC12") (pin "14") (pinfunction "IOA7_14") (pintype "bidirectional"))
    )
    (net (code "295") (name "unconnected-(IC12-IOB0-Pad13)") (class "Default")
      (node (ref "IC12") (pin "13") (pinfunction "IOB0_13") (pintype "bidirectional"))
    )
    (net (code "296") (name "unconnected-(IC12-IOB1-Pad12)") (class "Default")
      (node (ref "IC12") (pin "12") (pinfunction "IOB1_12") (pintype "bidirectional"))
    )
    (net (code "297") (name "unconnected-(IC12-IOB2-Pad11)") (class "Default")
      (node (ref "IC12") (pin "11") (pinfunction "IOB2_11") (pintype "bidirectional"))
    )
    (net (code "298") (name "unconnected-(IC12-IOB3-Pad10)") (class "Default")
      (node (ref "IC12") (pin "10") (pinfunction "IOB3_10") (pintype "bidirectional"))
    )
    (net (code "299") (name "unconnected-(IC12-IOB4-Pad9)") (class "Default")
      (node (ref "IC12") (pin "9") (pinfunction "IOB4_9") (pintype "bidirectional"))
    )
    (net (code "300") (name "unconnected-(IC12-IOB5-Pad8)") (class "Default")
      (node (ref "IC12") (pin "8") (pinfunction "IOB5_8") (pintype "bidirectional"))
    )
    (net (code "301") (name "unconnected-(IC12-IOB6-Pad7)") (class "Default")
      (node (ref "IC12") (pin "7") (pinfunction "IOB6_7") (pintype "bidirectional"))
    )
    (net (code "302") (name "unconnected-(IC12-IOB7-Pad6)") (class "Default")
      (node (ref "IC12") (pin "6") (pinfunction "IOB7_6") (pintype "bidirectional"))
    )
    (net (code "303") (name "unconnected-(IC12-NC-Pad2)") (class "Default")
      (node (ref "IC12") (pin "2") (pinfunction "NC_2") (pintype "bidirectional"))
    )
    (net (code "304") (name "unconnected-(IC12-NC2-Pad5)") (class "Default")
      (node (ref "IC12") (pin "5") (pinfunction "NC2_5") (pintype "bidirectional"))
    )
    (net (code "305") (name "unconnected-(IC12-TEST1-Pad39)") (class "Default")
      (node (ref "IC12") (pin "39") (pinfunction "TEST1_39") (pintype "bidirectional"))
    )
    (net (code "306") (name "unconnected-(IC12-~{SEL}-Pad26)") (class "Default")
      (node (ref "IC12") (pin "26") (pinfunction "~{SEL}_26") (pintype "bidirectional"))
    )
    (net (code "307") (name "unconnected-(IC13A-Y0-Pad15)") (class "Default")
      (node (ref "IC13") (pin "15") (pinfunction "Y0_15") (pintype "output"))
    )
    (net (code "308") (name "unconnected-(IC13A-Y1-Pad14)") (class "Default")
      (node (ref "IC13") (pin "14") (pinfunction "Y1_14") (pintype "output"))
    )
    (net (code "309") (name "unconnected-(IC13A-Y2-Pad13)") (class "Default")
      (node (ref "IC13") (pin "13") (pinfunction "Y2_13") (pintype "output"))
    )
    (net (code "310") (name "unconnected-(IC13A-Y3-Pad12)") (class "Default")
      (node (ref "IC13") (pin "12") (pinfunction "Y3_12") (pintype "output"))
    )
    (net (code "311") (name "unconnected-(IC16A-QA-Pad12)") (class "Default")
      (node (ref "IC16") (pin "12") (pinfunction "QA_12") (pintype "output"))
    )
    (net (code "312") (name "unconnected-(IC16A-QB-Pad9)") (class "Default")
      (node (ref "IC16") (pin "9") (pinfunction "QB_9") (pintype "output"))
    )
    (net (code "313") (name "unconnected-(IC16A-QC-Pad8)") (class "Default")
      (node (ref "IC16") (pin "8") (pinfunction "QC_8") (pintype "output"))
    )
    (net (code "314") (name "unconnected-(IC17A-QE-Pad4)") (class "Default")
      (node (ref "IC17") (pin "4") (pinfunction "QE_4") (pintype "tri_state"))
    )
    (net (code "315") (name "unconnected-(IC17A-QF-Pad5)") (class "Default")
      (node (ref "IC17") (pin "5") (pinfunction "QF_5") (pintype "tri_state"))
    )
    (net (code "316") (name "unconnected-(IC17A-QH*-Pad9)") (class "Default")
      (node (ref "IC17") (pin "9") (pinfunction "QH*_9") (pintype "tri_state"))
    )
    (net (code "317") (name "unconnected-(IC18A-QH*-Pad9)") (class "Default")
      (node (ref "IC18") (pin "9") (pinfunction "QH*_9") (pintype "tri_state"))
    )
    (net (code "318") (name "unconnected-(IC19A-QC-Pad8)") (class "Default")
      (node (ref "IC19") (pin "8") (pinfunction "QC_8") (pintype "output"))
    )
    (net (code "319") (name "unconnected-(IC21A-W-Pad6)") (class "Default")
      (node (ref "IC21") (pin "6") (pinfunction "W_6") (pintype "tri_state"))
    )
    (net (code "320") (name "unconnected-(IC22-Pad5)") (class "Default")
      (node (ref "IC22") (pin "5") (pinfunction "5_5") (pintype "passive"))
    )
    (net (code "321") (name "unconnected-(IC22-Pad8)") (class "Default")
      (node (ref "IC22") (pin "8") (pinfunction "8_8") (pintype "passive"))
    )
    (net (code "322") (name "unconnected-(IC22-Pad11)") (class "Default")
      (node (ref "IC22") (pin "11") (pinfunction "11_11") (pintype "passive"))
    )
    (net (code "323") (name "unconnected-(IC22-Pad21)") (class "Default")
      (node (ref "IC22") (pin "21") (pinfunction "21_21") (pintype "passive"))
    )
    (net (code "324") (name "unconnected-(IC22-Pad22)") (class "Default")
      (node (ref "IC22") (pin "22") (pinfunction "22_22") (pintype "passive"))
    )
    (net (code "325") (name "unconnected-(IC22-Pad23)") (class "Default")
      (node (ref "IC22") (pin "23") (pinfunction "23_23") (pintype "passive"))
    )
    (net (code "326") (name "unconnected-(IC23C-I-Pad5)") (class "Default")
      (node (ref "IC23") (pin "5") (pinfunction "I_5") (pintype "input"))
    )
    (net (code "327") (name "unconnected-(IC23C-O-Pad6)") (class "Default")
      (node (ref "IC23") (pin "6") (pinfunction "O_6") (pintype "output"))
    )
    (net (code "328") (name "unconnected-(IC23D-I-Pad9)") (class "Default")
      (node (ref "IC23") (pin "9") (pinfunction "I_9") (pintype "input"))
    )
    (net (code "329") (name "unconnected-(IC23D-O-Pad8)") (class "Default")
      (node (ref "IC23") (pin "8") (pinfunction "O_8") (pintype "output"))
    )
    (net (code "330") (name "unconnected-(IC23E-O-Pad10)") (class "Default")
      (node (ref "IC23") (pin "10") (pinfunction "O_10") (pintype "output"))
    )
    (net (code "331") (name "unconnected-(IC23F-O-Pad12)") (class "Default")
      (node (ref "IC23") (pin "12") (pinfunction "O_12") (pintype "output"))
    )
    (net (code "332") (name "unconnected-(JP3-Pad4)") (class "Default")
      (node (ref "JP3") (pin "4") (pinfunction "4_4") (pintype "passive"))
    )
    (net (code "333") (name "unconnected-(JP3-Pad6)") (class "Default")
      (node (ref "JP3") (pin "6") (pinfunction "6_6") (pintype "passive"))
    )
    (net (code "334") (name "unconnected-(JP3-Pad8)") (class "Default")
      (node (ref "JP3") (pin "8") (pinfunction "8_8") (pintype "passive"))
    )
    (net (code "335") (name "unconnected-(X3H-F-Pad8)") (class "Default")
      (node (ref "X3") (pin "8") (pinfunction "F_8") (pintype "passive"))
    )
    (net (code "336") (name "unconnected-(X4-Pad2)") (class "Default")
      (node (ref "X4") (pin "2") (pinfunction "2_2") (pintype "passive"))
    )
    (net (code "337") (name "unconnected-(X4-Pad3)") (class "Default")
      (node (ref "X4") (pin "3") (pinfunction "3_3") (pintype "passive"))
    )
    (net (code "338") (name "unconnected-(X4-Pad4)") (class "Default")
      (node (ref "X4") (pin "4") (pinfunction "4_4") (pintype "passive"))
    )
    (net (code "339") (name "unconnected-(X4-Pad5)") (class "Default")
      (node (ref "X4") (pin "5") (pinfunction "5_5") (pintype "passive"))
    )
    (net (code "340") (name "unconnected-(X4-Pad6)") (class "Default")
      (node (ref "X4") (pin "6") (pinfunction "6_6") (pintype "passive"))
    )
    (net (code "341") (name "unconnected-(X4-Pad7)") (class "Default")
      (node (ref "X4") (pin "7") (pinfunction "7_7") (pintype "passive"))
    )
    (net (code "342") (name "unconnected-(X4-Pad10)") (class "Default")
      (node (ref "X4") (pin "10") (pinfunction "10_10") (pintype "passive"))
    )
    (net (code "343") (name "unconnected-(X4-Pad11)") (class "Default")
      (node (ref "X4") (pin "11") (pinfunction "11_11") (pintype "passive"))
    )
    (net (code "344") (name "unconnected-(X4-Pad13)") (class "Default")
      (node (ref "X4") (pin "13") (pinfunction "13_13") (pintype "passive"))
    )
    (net (code "345") (name "unconnected-(X4-Pad14)") (class "Default")
      (node (ref "X4") (pin "14") (pinfunction "14_14") (pintype "passive"))
    )
    (net (code "346") (name "unconnected-(X5-Pad2)") (class "Default")
      (node (ref "X5") (pin "2") (pinfunction "2_2") (pintype "passive"))
    )
    (net (code "347") (name "unconnected-(X5-Pad3)") (class "Default")
      (node (ref "X5") (pin "3") (pinfunction "3_3") (pintype "passive"))
    )
    (net (code "348") (name "unconnected-(X5-Pad4)") (class "Default")
      (node (ref "X5") (pin "4") (pinfunction "4_4") (pintype "passive"))
    )
    (net (code "349") (name "unconnected-(X5-Pad5)") (class "Default")
      (node (ref "X5") (pin "5") (pinfunction "5_5") (pintype "passive"))
    )
    (net (code "350") (name "unconnected-(X5-Pad6)") (class "Default")
      (node (ref "X5") (pin "6") (pinfunction "6_6") (pintype "passive"))
    )
    (net (code "351") (name "unconnected-(X5-Pad7)") (class "Default")
      (node (ref "X5") (pin "7") (pinfunction "7_7") (pintype "passive"))
    )
    (net (code "352") (name "unconnected-(X5-Pad10)") (class "Default")
      (node (ref "X5") (pin "10") (pinfunction "10_10") (pintype "passive"))
    )
    (net (code "353") (name "unconnected-(X5-Pad11)") (class "Default")
      (node (ref "X5") (pin "11") (pinfunction "11_11") (pintype "passive"))
    )
    (net (code "354") (name "unconnected-(X5-Pad13)") (class "Default")
      (node (ref "X5") (pin "13") (pinfunction "13_13") (pintype "passive"))
    )
    (net (code "355") (name "unconnected-(X5-Pad14)") (class "Default")
      (node (ref "X5") (pin "14") (pinfunction "14_14") (pintype "passive"))
    )
    (net (code "356") (name "unconnected-(X8-Pad1)") (class "Default")
      (node (ref "X8") (pin "1") (pinfunction "1_1") (pintype "passive"))
    )
    (net (code "357") (name "unconnected-(X8-Pad2)") (class "Default")
      (node (ref "X8") (pin "2") (pinfunction "2_2") (pintype "passive"))
    )
    (net (code "358") (name "unconnected-(X8-Pad3)") (class "Default")
      (node (ref "X8") (pin "3") (pinfunction "3_3") (pintype "passive"))
    )
    (net (code "359") (name "unconnected-(X8-Pad4)") (class "Default")
      (node (ref "X8") (pin "4") (pinfunction "4_4") (pintype "passive"))
    )
    (net (code "360") (name "unconnected-(X8-Pad5)") (class "Default")
      (node (ref "X8") (pin "5") (pinfunction "5_5") (pintype "passive"))
    )
    (net (code "361") (name "unconnected-(X8-Pad6)") (class "Default")
      (node (ref "X8") (pin "6") (pinfunction "6_6") (pintype "passive"))
    )
    (net (code "362") (name "unconnected-(X8-Pad7)") (class "Default")
      (node (ref "X8") (pin "7") (pinfunction "7_7") (pintype "passive"))
    )
    (net (code "363") (name "unconnected-(X8-Pad8)") (class "Default")
      (node (ref "X8") (pin "8") (pinfunction "8_8") (pintype "passive"))
    )
    (net (code "364") (name "unconnected-(X8-Pad9)") (class "Default")
      (node (ref "X8") (pin "9") (pinfunction "9_9") (pintype "passive"))
    )
    (net (code "365") (name "unconnected-(X8-Pad10)") (class "Default")
      (node (ref "X8") (pin "10") (pinfunction "10_10") (pintype "passive"))
    )
    (net (code "366") (name "unconnected-(X8-Pad11)") (class "Default")
      (node (ref "X8") (pin "11") (pinfunction "11_11") (pintype "passive"))
    )
    (net (code "367") (name "unconnected-(X8-Pad12)") (class "Default")
      (node (ref "X8") (pin "12") (pinfunction "12_12") (pintype "passive"))
    )
    (net (code "368") (name "unconnected-(X8-Pad13)") (class "Default")
      (node (ref "X8") (pin "13") (pinfunction "13_13") (pintype "passive"))
    )
    (net (code "369") (name "unconnected-(X8-Pad14)") (class "Default")
      (node (ref "X8") (pin "14") (pinfunction "14_14") (pintype "passive"))
    )
    (net (code "370") (name "unconnected-(X8-Pad15)") (class "Default")
      (node (ref "X8") (pin "15") (pinfunction "15_15") (pintype "passive"))
    )
    (net (code "371") (name "unconnected-(X8-Pad16)") (class "Default")
      (node (ref "X8") (pin "16") (pinfunction "16_16") (pintype "passive"))
    )
    (net (code "372") (name "unconnected-(X8-Pad17)") (class "Default")
      (node (ref "X8") (pin "17") (pinfunction "17_17") (pintype "passive"))
    )
    (net (code "373") (name "unconnected-(X8-Pad18)") (class "Default")
      (node (ref "X8") (pin "18") (pinfunction "18_18") (pintype "passive"))
    )
    (net (code "374") (name "unconnected-(X8-Pad19)") (class "Default")
      (node (ref "X8") (pin "19") (pinfunction "19_19") (pintype "passive"))
    )
    (net (code "375") (name "unconnected-(X8-Pad20)") (class "Default")
      (node (ref "X8") (pin "20") (pinfunction "20_20") (pintype "passive"))
    )
    (net (code "376") (name "unconnected-(X8-Pad21)") (class "Default")
      (node (ref "X8") (pin "21") (pinfunction "21_21") (pintype "passive"))
    )
  )
)
